# serv_open8_tsmc.net
KiCad netlist of a schematic drawn in EAGLE
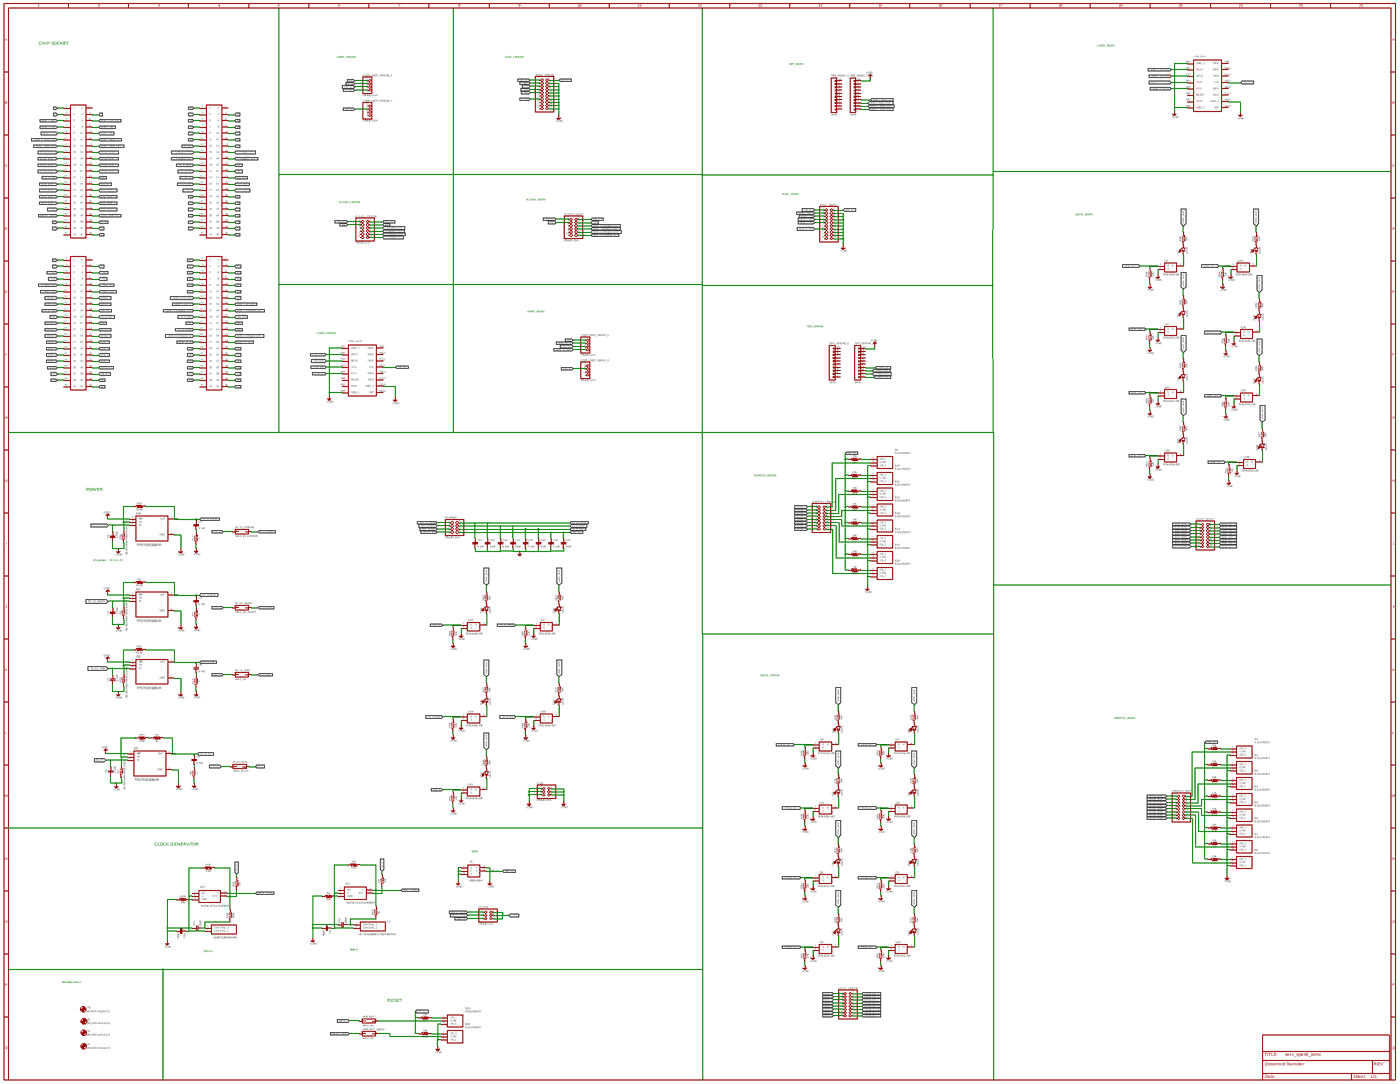
[diagram p0: schematic, sheet 1, overview]
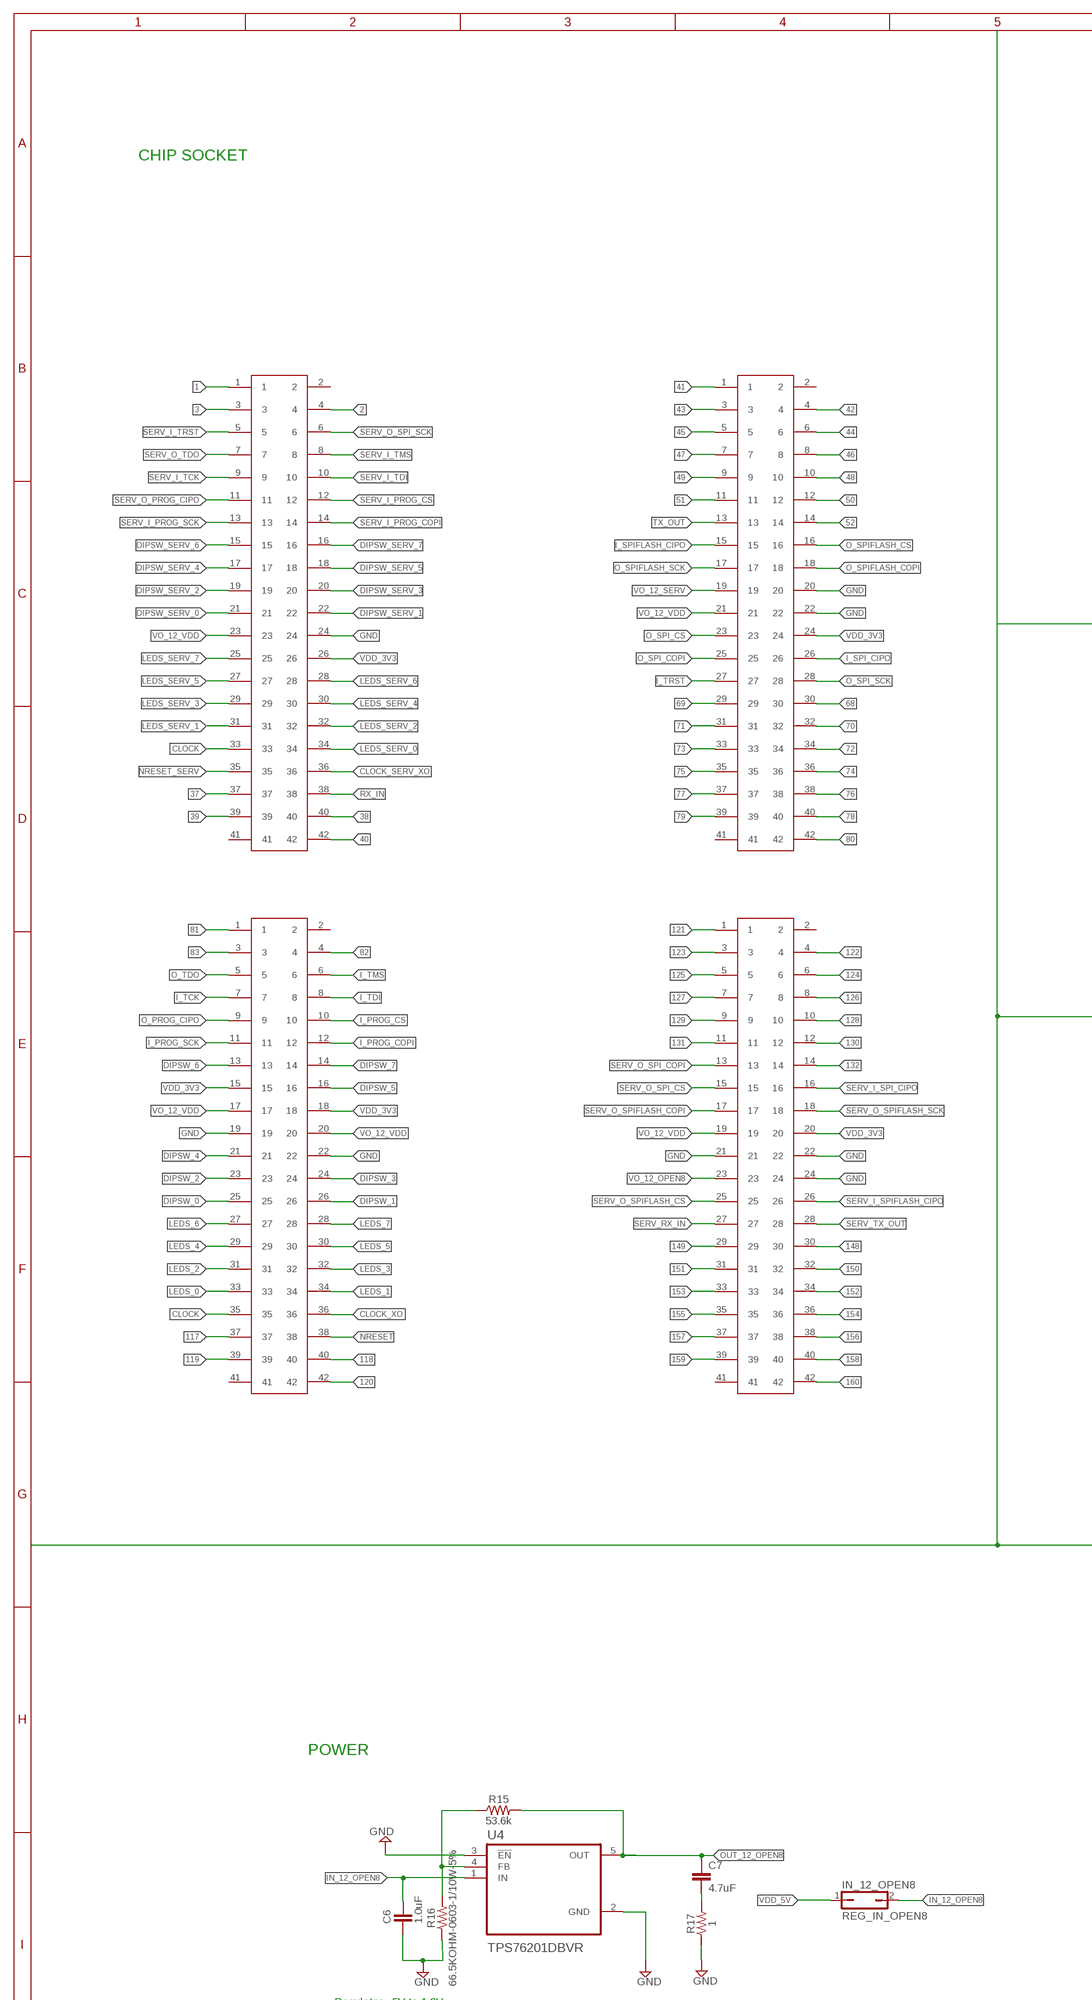
[diagram p1: schematic, sheet 1, part 1 of 8]
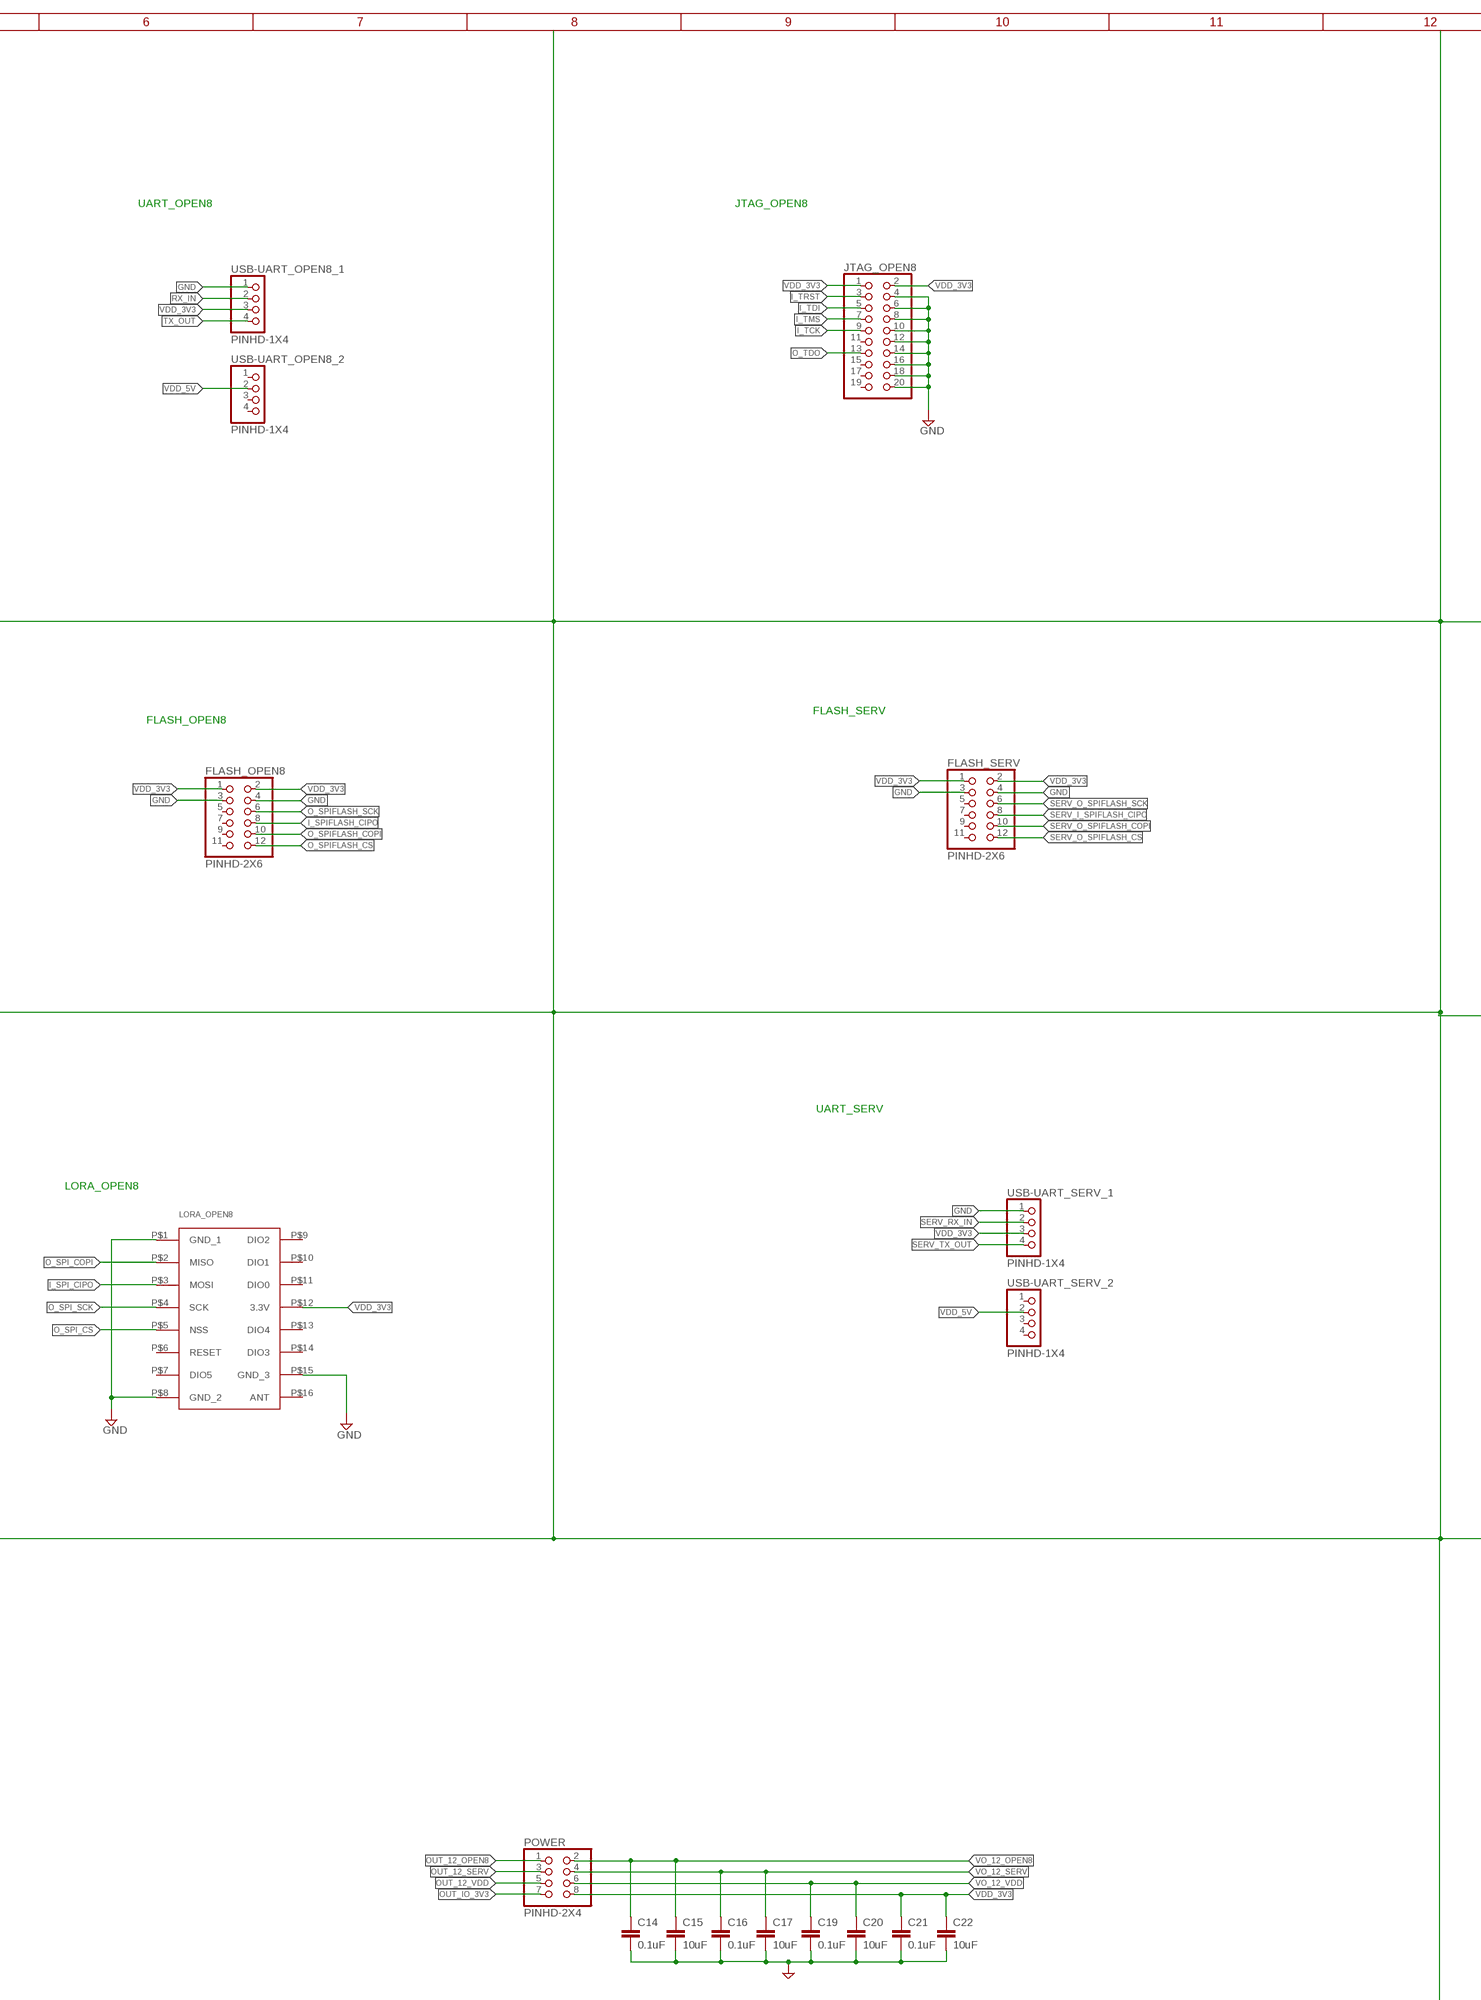
[diagram p2: schematic, sheet 1, part 2 of 8]
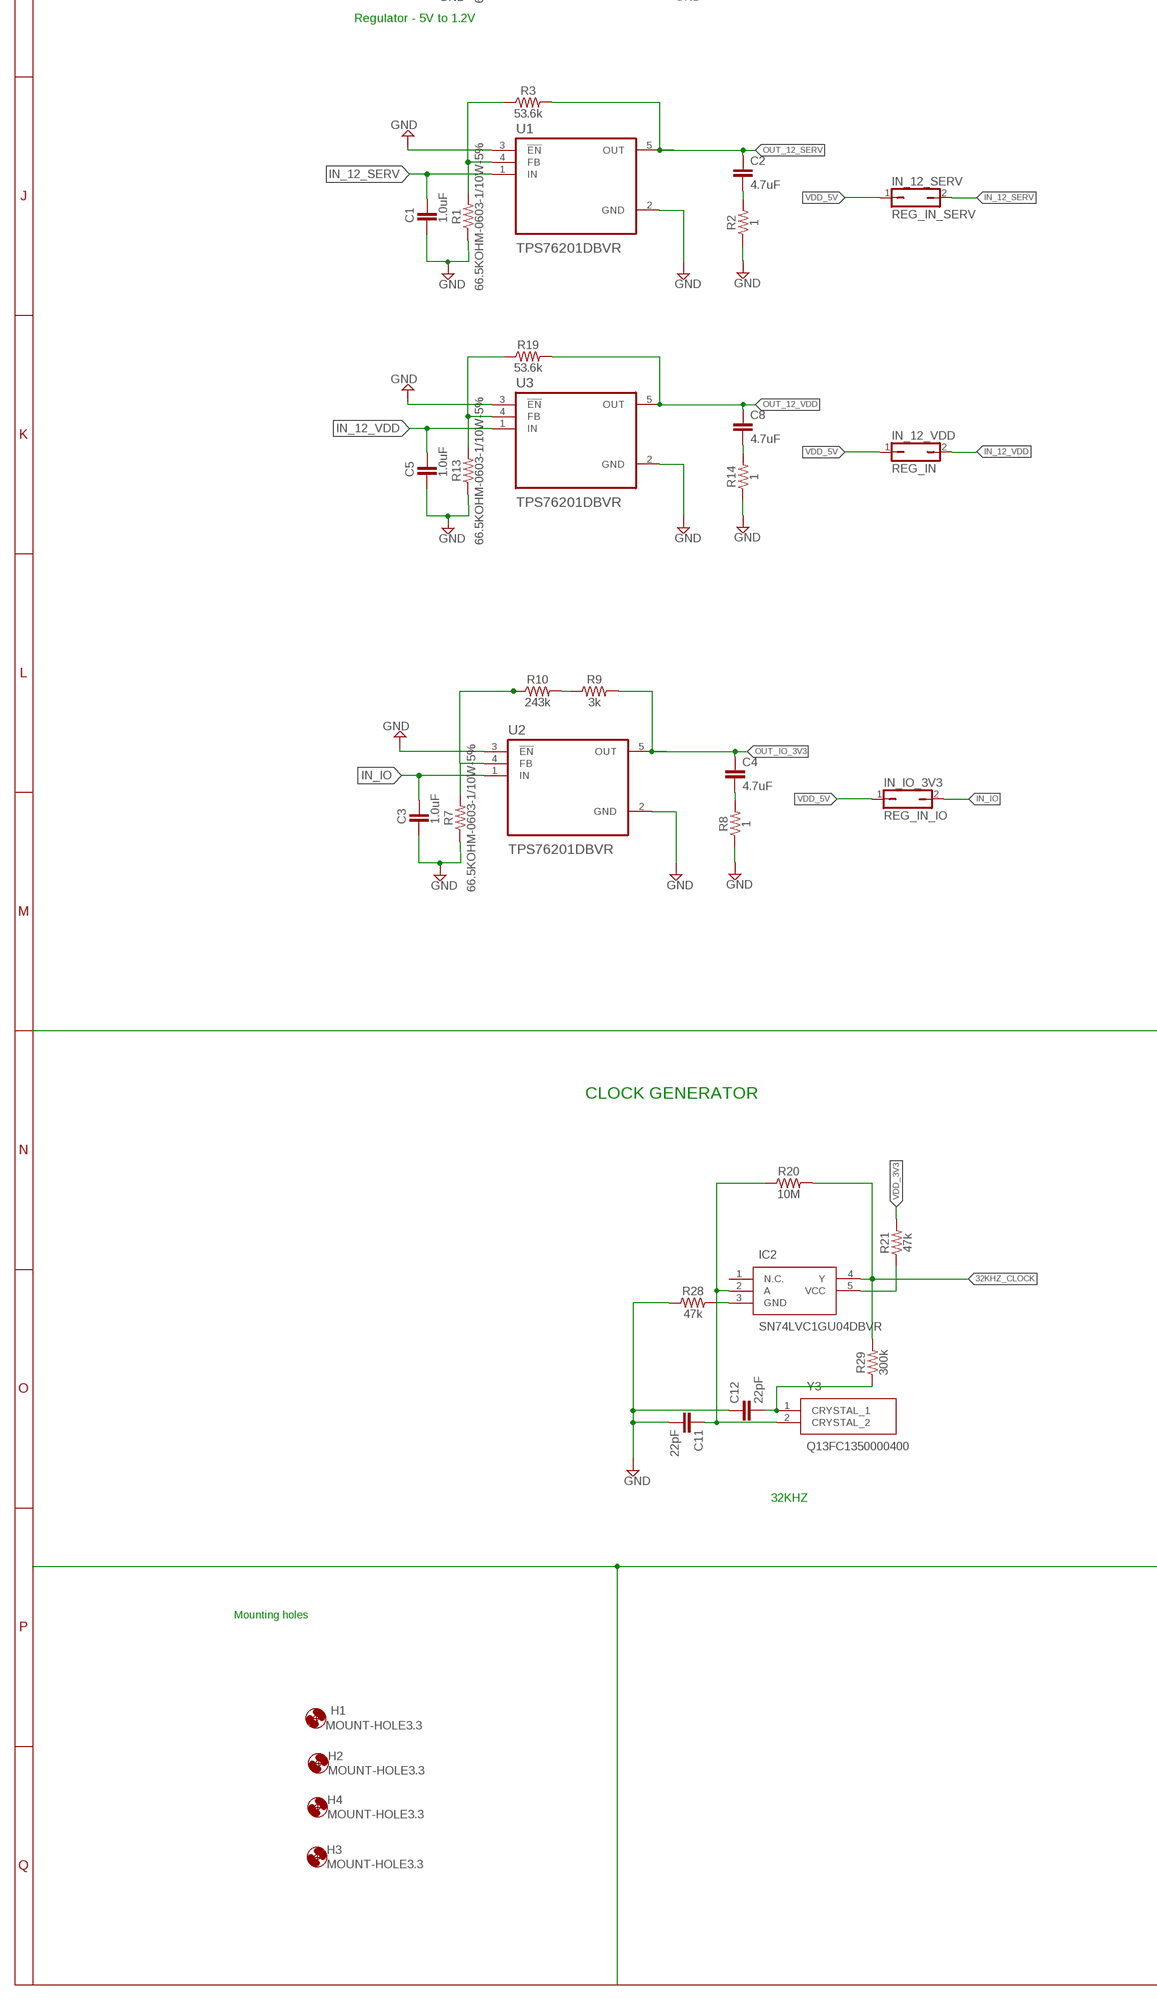
[diagram p3: schematic, sheet 1, part 3 of 8]
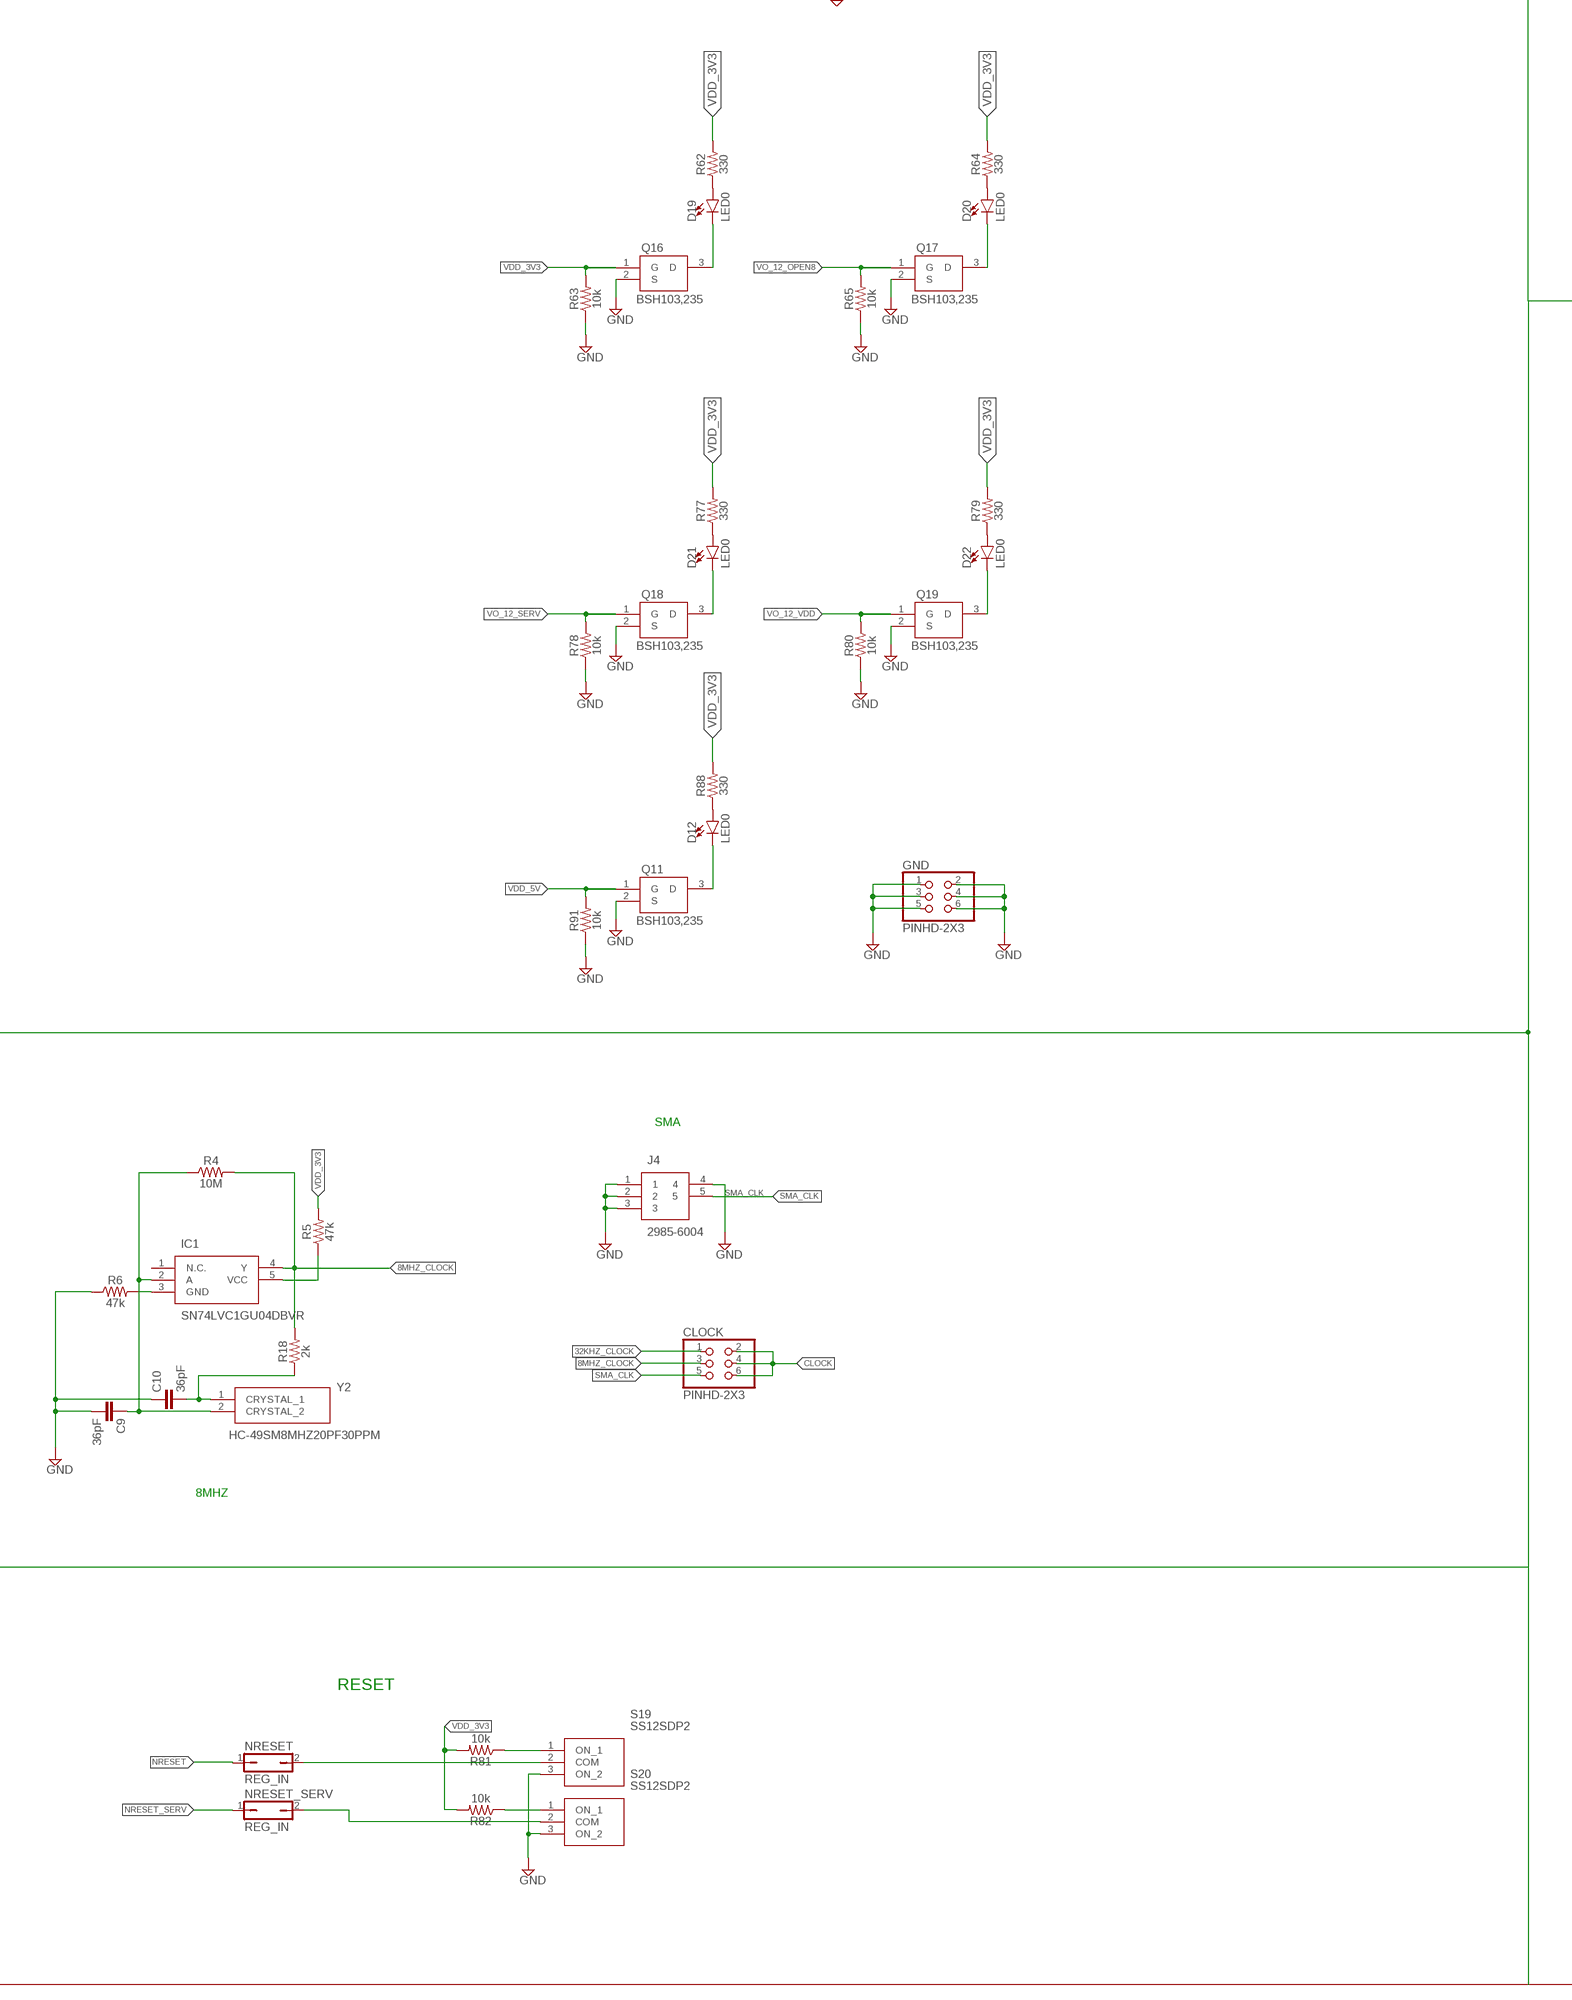
[diagram p4: schematic, sheet 1, part 4 of 8]
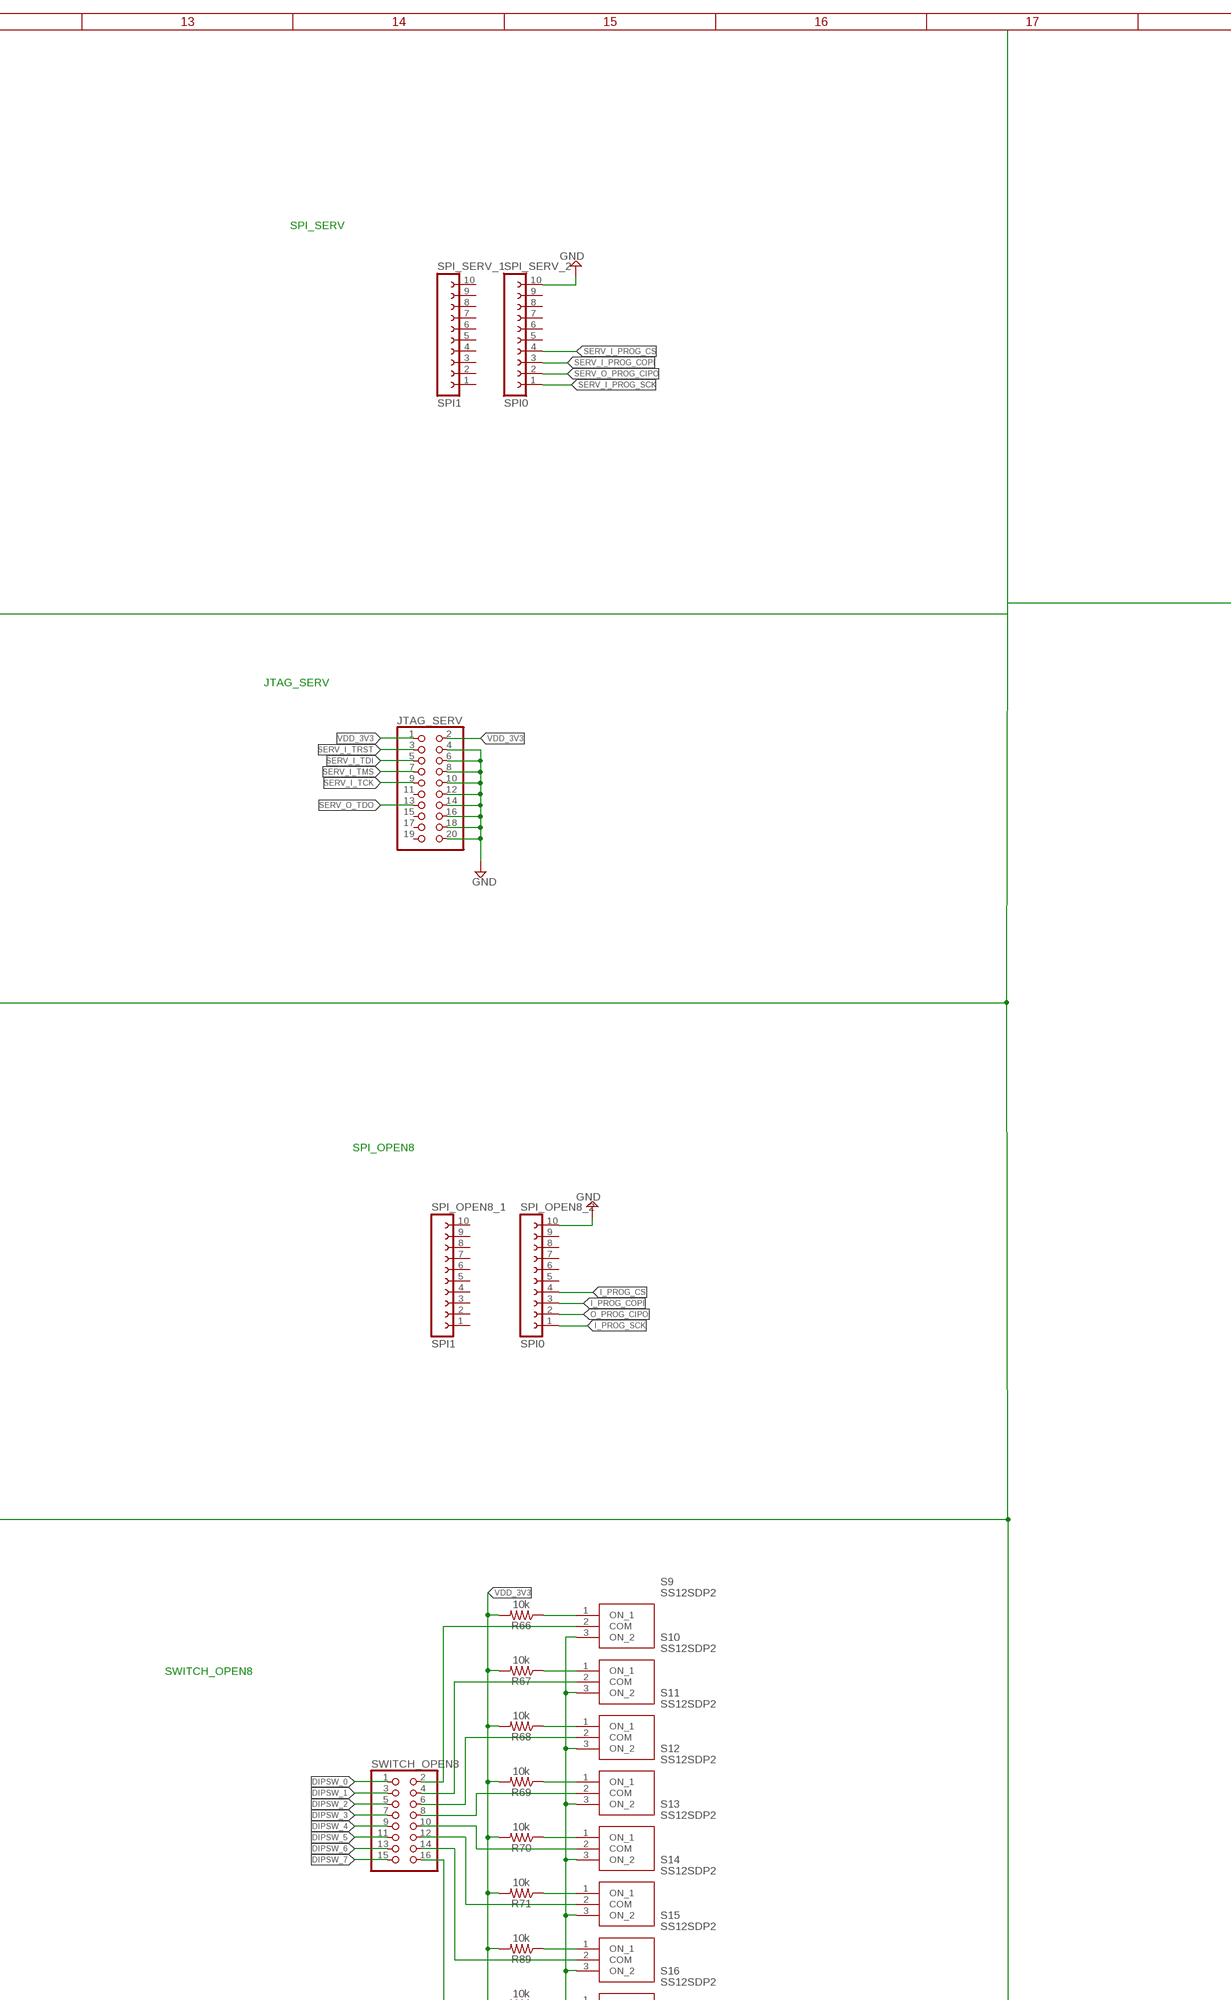
[diagram p5: schematic, sheet 1, part 5 of 8]
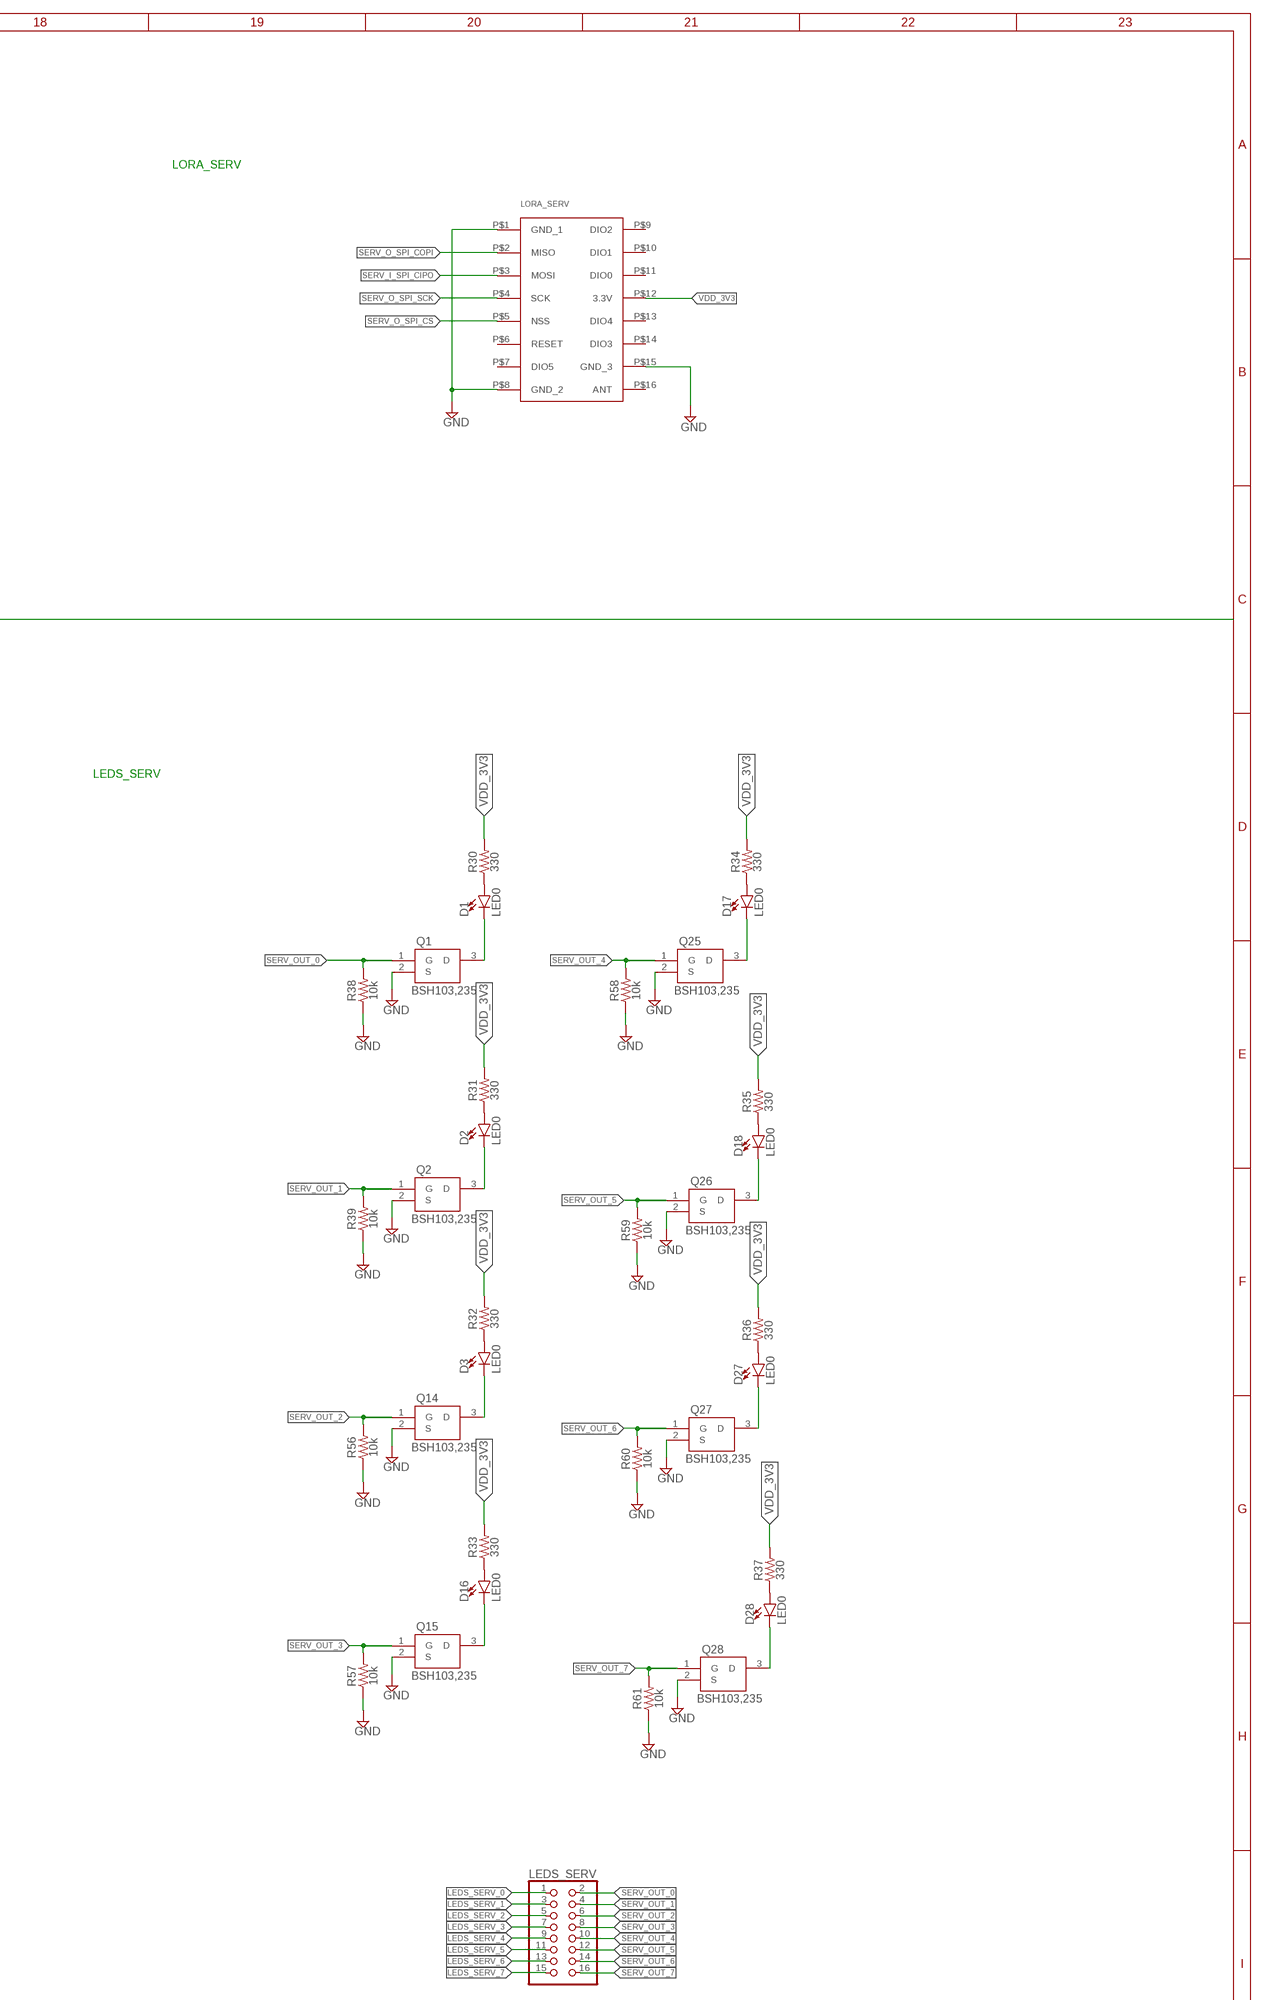
[diagram p6: schematic, sheet 1, part 6 of 8]
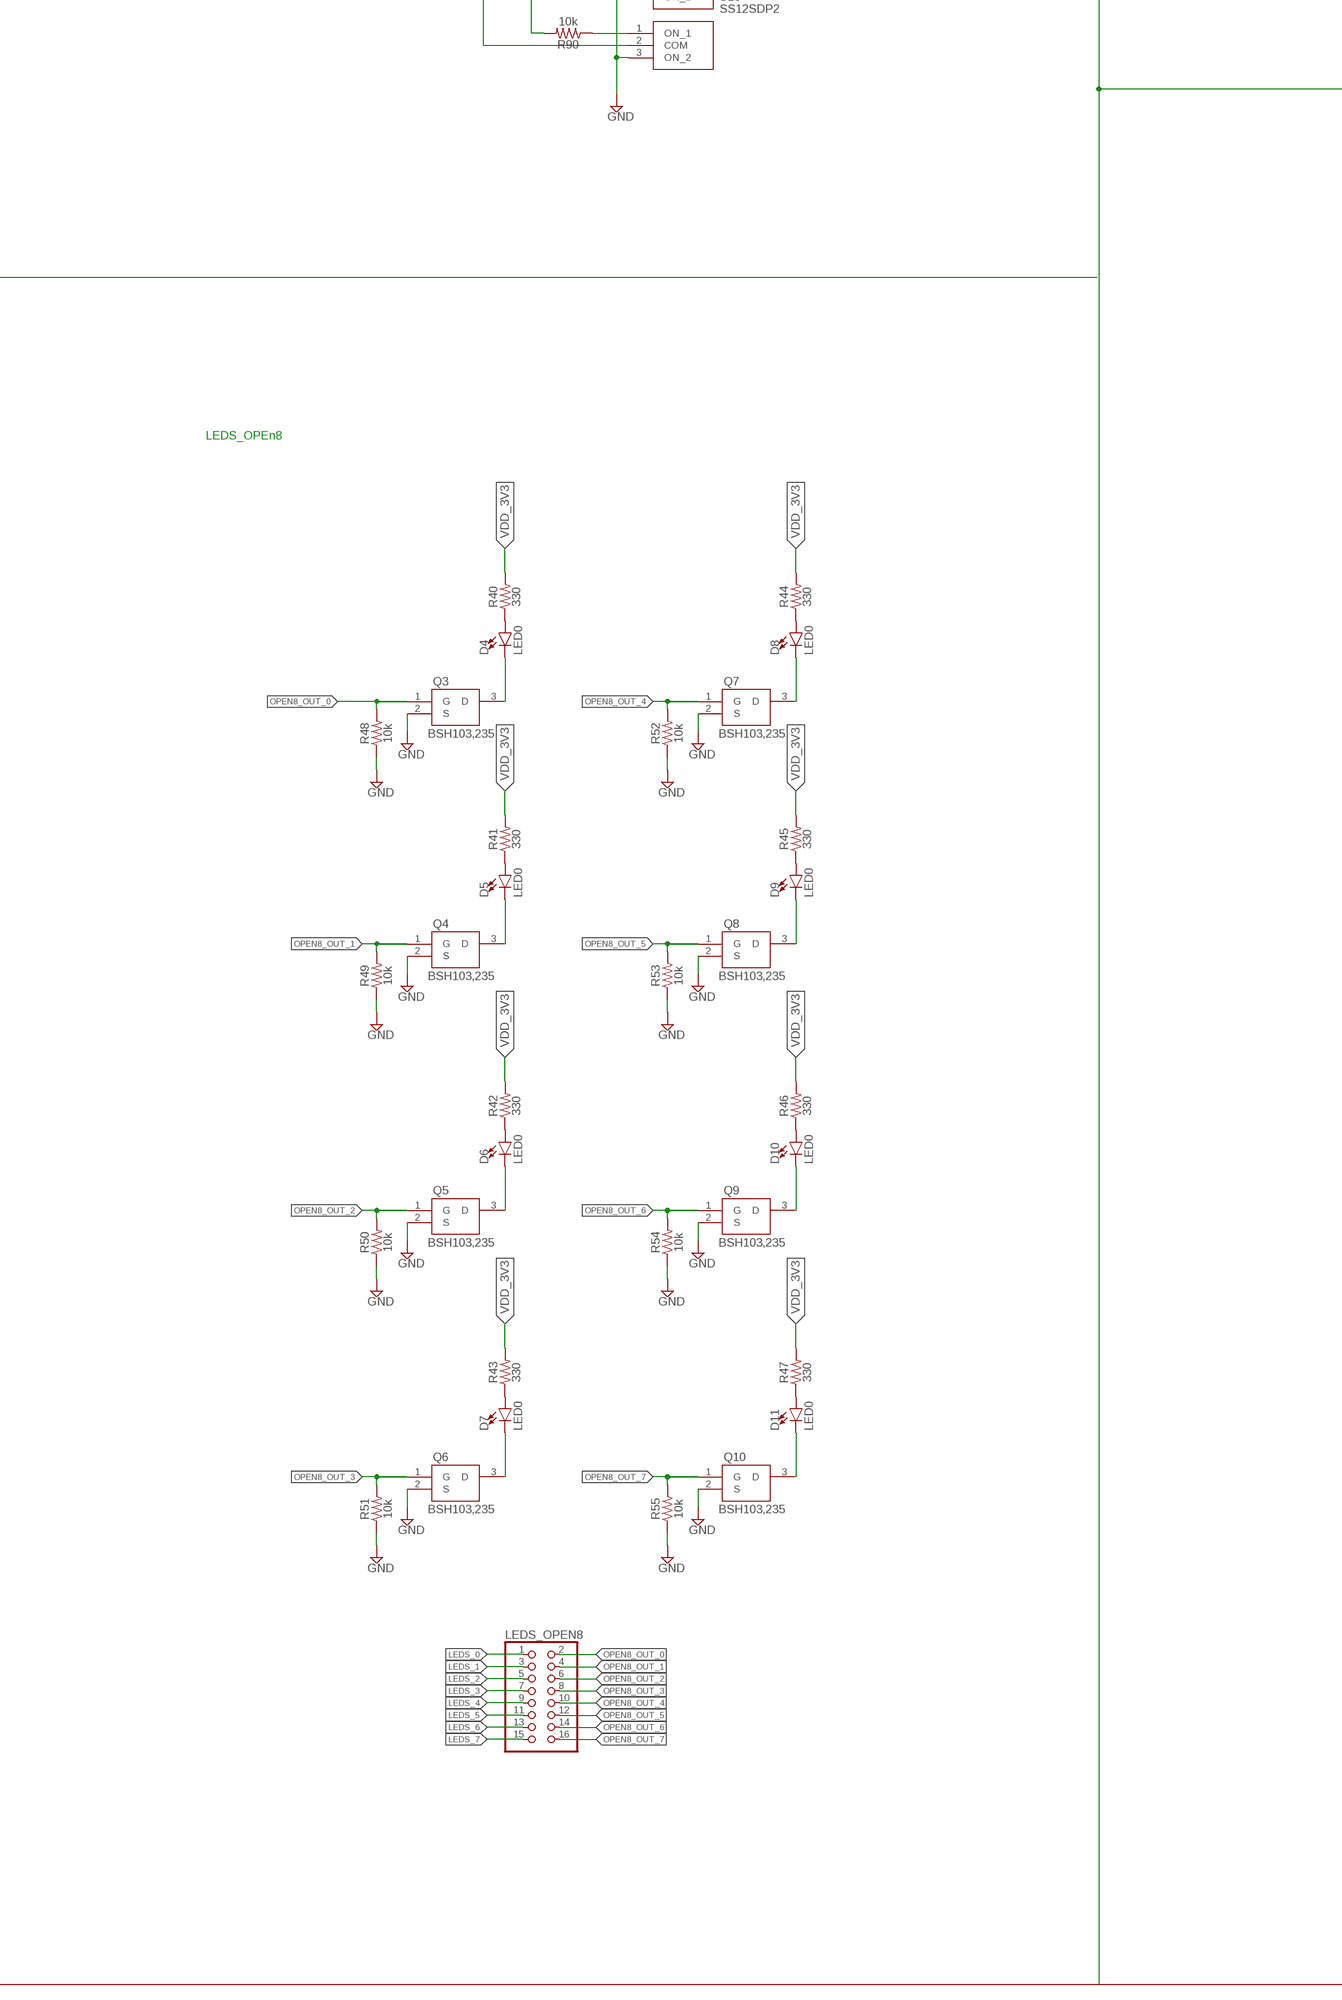
[diagram p7: schematic, sheet 1, part 7 of 8]
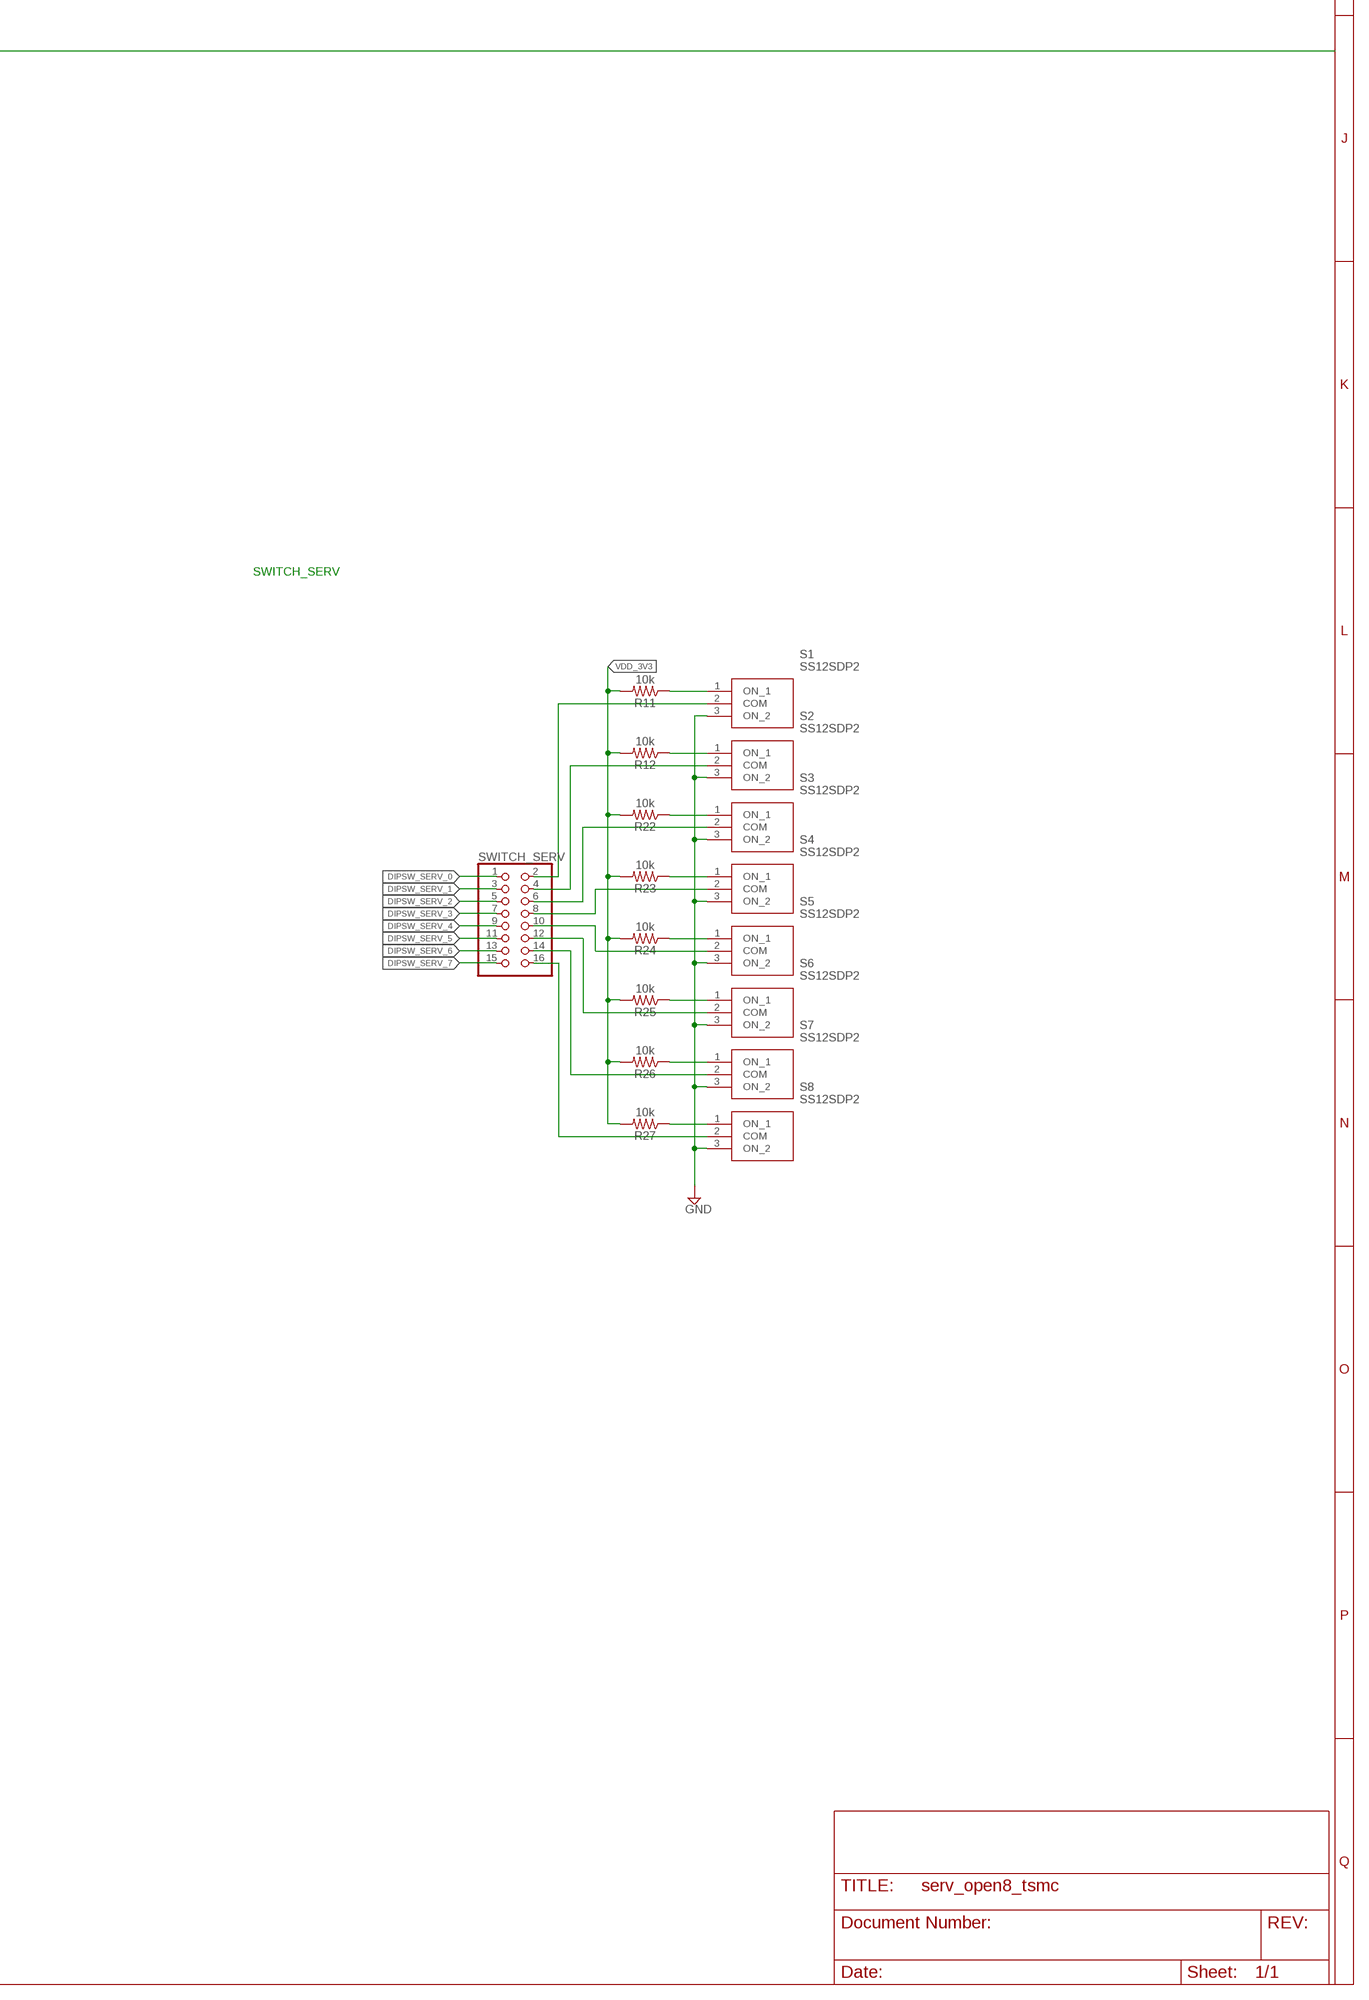
[diagram p8: schematic, sheet 1, part 8 of 8]

(export (version "E")
  (design (tool "Eeschema 10.0.6"))
  (components
    (comp (ref "C1")
      (value "1.0uF")
      (footprint "eagle-import:0603")
      (libsource (lib "eagle-import") (part "1.0UF-0603-16V-10%"))
    )
    (comp (ref "C2")
      (value "4.7uF")
      (footprint "eagle-import:0603")
      (libsource (lib "eagle-import") (part "4.7UF0603"))
    )
    (comp (ref "C3")
      (value "1.0uF")
      (footprint "eagle-import:0603")
      (libsource (lib "eagle-import") (part "1.0UF-0603-16V-10%"))
    )
    (comp (ref "C4")
      (value "4.7uF")
      (footprint "eagle-import:0603")
      (libsource (lib "eagle-import") (part "4.7UF0603"))
    )
    (comp (ref "C5")
      (value "1.0uF")
      (footprint "eagle-import:0603")
      (libsource (lib "eagle-import") (part "1.0UF-0603-16V-10%"))
    )
    (comp (ref "C6")
      (value "1.0uF")
      (footprint "eagle-import:0603")
      (libsource (lib "eagle-import") (part "1.0UF-0603-16V-10%"))
    )
    (comp (ref "C7")
      (value "4.7uF")
      (footprint "eagle-import:0603")
      (libsource (lib "eagle-import") (part "4.7UF0603"))
    )
    (comp (ref "C8")
      (value "4.7uF")
      (footprint "eagle-import:0603")
      (libsource (lib "eagle-import") (part "4.7UF0603"))
    )
    (comp (ref "C9")
      (value "36pF")
      (footprint "eagle-import:0603")
      (libsource (lib "eagle-import") (part "22PF-0603-50V-5%"))
    )
    (comp (ref "C10")
      (value "36pF")
      (footprint "eagle-import:0603")
      (libsource (lib "eagle-import") (part "22PF-0603-50V-5%"))
    )
    (comp (ref "C11")
      (value "22pF")
      (footprint "eagle-import:0603")
      (libsource (lib "eagle-import") (part "22PF-0603-50V-5%"))
    )
    (comp (ref "C12")
      (value "22pF")
      (footprint "eagle-import:0603")
      (libsource (lib "eagle-import") (part "22PF-0603-50V-5%"))
    )
    (comp (ref "C14")
      (value "0.1uF")
      (footprint "eagle-import:0603")
      (libsource (lib "eagle-import") (part "0.1UF-0603-25V-5%"))
    )
    (comp (ref "C15")
      (value "10uF")
      (footprint "eagle-import:0603")
      (libsource (lib "eagle-import") (part "10UF-0603-6.3V-20%"))
    )
    (comp (ref "C16")
      (value "0.1uF")
      (footprint "eagle-import:0603")
      (libsource (lib "eagle-import") (part "0.1UF-0603-25V-5%"))
    )
    (comp (ref "C17")
      (value "10uF")
      (footprint "eagle-import:0603")
      (libsource (lib "eagle-import") (part "10UF-0603-6.3V-20%"))
    )
    (comp (ref "C19")
      (value "0.1uF")
      (footprint "eagle-import:0603")
      (libsource (lib "eagle-import") (part "0.1UF-0603-25V-5%"))
    )
    (comp (ref "C20")
      (value "10uF")
      (footprint "eagle-import:0603")
      (libsource (lib "eagle-import") (part "10UF-0603-6.3V-20%"))
    )
    (comp (ref "C21")
      (value "0.1uF")
      (footprint "eagle-import:0603")
      (libsource (lib "eagle-import") (part "0.1UF-0603-25V-5%"))
    )
    (comp (ref "C22")
      (value "10uF")
      (footprint "eagle-import:0603")
      (libsource (lib "eagle-import") (part "10UF-0603-6.3V-20%"))
    )
    (comp (ref "CLOCK")
      (value "PINHD-2X3")
      (footprint "eagle-import:2X03")
      (libsource (lib "eagle-import") (part "PINHD-2X3"))
    )
    (comp (ref "D1")
      (value "LED0")
      (footprint "eagle-import:LED-0603")
      (libsource (lib "eagle-import") (part "LED0603"))
    )
    (comp (ref "D2")
      (value "LED0")
      (footprint "eagle-import:LED-0603")
      (libsource (lib "eagle-import") (part "LED0603"))
    )
    (comp (ref "D3")
      (value "LED0")
      (footprint "eagle-import:LED-0603")
      (libsource (lib "eagle-import") (part "LED0603"))
    )
    (comp (ref "D4")
      (value "LED0")
      (footprint "eagle-import:LED-0603")
      (libsource (lib "eagle-import") (part "LED0603"))
    )
    (comp (ref "D5")
      (value "LED0")
      (footprint "eagle-import:LED-0603")
      (libsource (lib "eagle-import") (part "LED0603"))
    )
    (comp (ref "D6")
      (value "LED0")
      (footprint "eagle-import:LED-0603")
      (libsource (lib "eagle-import") (part "LED0603"))
    )
    (comp (ref "D7")
      (value "LED0")
      (footprint "eagle-import:LED-0603")
      (libsource (lib "eagle-import") (part "LED0603"))
    )
    (comp (ref "D8")
      (value "LED0")
      (footprint "eagle-import:LED-0603")
      (libsource (lib "eagle-import") (part "LED0603"))
    )
    (comp (ref "D9")
      (value "LED0")
      (footprint "eagle-import:LED-0603")
      (libsource (lib "eagle-import") (part "LED0603"))
    )
    (comp (ref "D10")
      (value "LED0")
      (footprint "eagle-import:LED-0603")
      (libsource (lib "eagle-import") (part "LED0603"))
    )
    (comp (ref "D11")
      (value "LED0")
      (footprint "eagle-import:LED-0603")
      (libsource (lib "eagle-import") (part "LED0603"))
    )
    (comp (ref "D12")
      (value "LED0")
      (footprint "eagle-import:LED-0603")
      (libsource (lib "eagle-import") (part "LED0603"))
    )
    (comp (ref "D16")
      (value "LED0")
      (footprint "eagle-import:LED-0603")
      (libsource (lib "eagle-import") (part "LED0603"))
    )
    (comp (ref "D17")
      (value "LED0")
      (footprint "eagle-import:LED-0603")
      (libsource (lib "eagle-import") (part "LED0603"))
    )
    (comp (ref "D18")
      (value "LED0")
      (footprint "eagle-import:LED-0603")
      (libsource (lib "eagle-import") (part "LED0603"))
    )
    (comp (ref "D19")
      (value "LED0")
      (footprint "eagle-import:LED-0603")
      (libsource (lib "eagle-import") (part "LED0603"))
    )
    (comp (ref "D20")
      (value "LED0")
      (footprint "eagle-import:LED-0603")
      (libsource (lib "eagle-import") (part "LED0603"))
    )
    (comp (ref "D21")
      (value "LED0")
      (footprint "eagle-import:LED-0603")
      (libsource (lib "eagle-import") (part "LED0603"))
    )
    (comp (ref "D22")
      (value "LED0")
      (footprint "eagle-import:LED-0603")
      (libsource (lib "eagle-import") (part "LED0603"))
    )
    (comp (ref "D27")
      (value "LED0")
      (footprint "eagle-import:LED-0603")
      (libsource (lib "eagle-import") (part "LED0603"))
    )
    (comp (ref "D28")
      (value "LED0")
      (footprint "eagle-import:LED-0603")
      (libsource (lib "eagle-import") (part "LED0603"))
    )
    (comp (ref "FLASH_OPEN8")
      (value "PINHD-2X6")
      (footprint "eagle-import:2X06")
      (libsource (lib "eagle-import") (part "PINHD-2X6"))
    )
    (comp (ref "FLASH_SERV")
      (value "PINHD-2X6")
      (footprint "eagle-import:2X06")
      (libsource (lib "eagle-import") (part "PINHD-2X6"))
    )
    (comp (ref "GND")
      (value "PINHD-2X3")
      (footprint "eagle-import:2X03")
      (libsource (lib "eagle-import") (part "PINHD-2X3"))
    )
    (comp (ref "H1")
      (value "MOUNT-HOLE3.3")
      (footprint "eagle-import:3,3")
      (libsource (lib "eagle-import") (part "MOUNT-HOLE3.3"))
    )
    (comp (ref "H2")
      (value "MOUNT-HOLE3.3")
      (footprint "eagle-import:3,3")
      (libsource (lib "eagle-import") (part "MOUNT-HOLE3.3"))
    )
    (comp (ref "H3")
      (value "MOUNT-HOLE3.3")
      (footprint "eagle-import:3,3")
      (libsource (lib "eagle-import") (part "MOUNT-HOLE3.3"))
    )
    (comp (ref "H4")
      (value "MOUNT-HOLE3.3")
      (footprint "eagle-import:3,3")
      (libsource (lib "eagle-import") (part "MOUNT-HOLE3.3"))
    )
    (comp (ref "IC1")
      (value "SN74LVC1GU04DBVR")
      (footprint "eagle-import:SOT95P280X145-5N")
      (fields (field (name "MOUSER_PART_NUMBER") "595-SN74LVC1GU04DBVR"))
      (libsource (lib "eagle-import") (part "SN74LVC1GU04DBVR"))
    )
    (comp (ref "IC2")
      (value "SN74LVC1GU04DBVR")
      (footprint "eagle-import:SOT95P280X145-5N")
      (fields (field (name "MOUSER_PART_NUMBER") "595-SN74LVC1GU04DBVR"))
      (libsource (lib "eagle-import") (part "SN74LVC1GU04DBVR"))
    )
    (comp (ref "IN_12_OPEN8")
      (value "REG_IN_OPEN8")
      (footprint "eagle-import:JP1")
      (libsource (lib "eagle-import") (part "JP1Q"))
    )
    (comp (ref "IN_12_SERV")
      (value "REG_IN_SERV")
      (footprint "eagle-import:JP1")
      (libsource (lib "eagle-import") (part "JP1Q"))
    )
    (comp (ref "IN_12_VDD")
      (value "REG_IN")
      (footprint "eagle-import:JP1")
      (libsource (lib "eagle-import") (part "JP1Q"))
    )
    (comp (ref "IN_IO_3V3")
      (value "REG_IN_IO")
      (footprint "eagle-import:JP1")
      (libsource (lib "eagle-import") (part "JP1Q"))
    )
    (comp (ref "J4")
      (value "2985-6004")
      (footprint "eagle-import:29856004")
      (fields (field (name "MOUSER_PART_NUMBER") "523-2985-6004"))
      (libsource (lib "eagle-import") (part "2985-6004"))
    )
    (comp (ref "JTAG_OPEN8")
      (value "PINHD-2X10")
      (footprint "eagle-import:2X10")
      (libsource (lib "eagle-import") (part "PINHD-2X10"))
    )
    (comp (ref "JTAG_SERV")
      (value "PINHD-2X10")
      (footprint "eagle-import:2X10")
      (libsource (lib "eagle-import") (part "PINHD-2X10"))
    )
    (comp (ref "LEDS_OPEN8")
      (value "PINHD-2X8")
      (footprint "eagle-import:2X08")
      (libsource (lib "eagle-import") (part "PINHD-2X8"))
    )
    (comp (ref "LEDS_SERV")
      (value "PINHD-2X8")
      (footprint "eagle-import:2X08")
      (libsource (lib "eagle-import") (part "PINHD-2X8"))
    )
    (comp (ref "LORA_OPEN8")
      (value "RFM95W-915S2")
      (footprint "eagle-import:RFM95-915S2")
      (libsource (lib "eagle-import") (part "RFM95W-915S2"))
    )
    (comp (ref "LORA_SERV")
      (value "RFM95W-915S2")
      (footprint "eagle-import:RFM95-915S2")
      (libsource (lib "eagle-import") (part "RFM95W-915S2"))
    )
    (comp (ref "NRESET")
      (value "REG_IN")
      (footprint "eagle-import:JP1")
      (libsource (lib "eagle-import") (part "JP1Q"))
    )
    (comp (ref "NRESET_SERV")
      (value "REG_IN")
      (footprint "eagle-import:JP1")
      (libsource (lib "eagle-import") (part "JP1Q"))
    )
    (comp (ref "POWER")
      (value "PINHD-2X4")
      (footprint "eagle-import:2X04")
      (libsource (lib "eagle-import") (part "PINHD-2X4"))
    )
    (comp (ref "Q1")
      (value "BSH103,235")
      (footprint "eagle-import:SOT95P230X110-3N")
      (fields (field (name "MOUSER_PART_NUMBER") "771-BSH103235"))
      (libsource (lib "eagle-import") (part "BSH103,235"))
    )
    (comp (ref "Q2")
      (value "BSH103,235")
      (footprint "eagle-import:SOT95P230X110-3N")
      (fields (field (name "MOUSER_PART_NUMBER") "771-BSH103235"))
      (libsource (lib "eagle-import") (part "BSH103,235"))
    )
    (comp (ref "Q3")
      (value "BSH103,235")
      (footprint "eagle-import:SOT95P230X110-3N")
      (fields (field (name "MOUSER_PART_NUMBER") "771-BSH103235"))
      (libsource (lib "eagle-import") (part "BSH103,235"))
    )
    (comp (ref "Q4")
      (value "BSH103,235")
      (footprint "eagle-import:SOT95P230X110-3N")
      (fields (field (name "MOUSER_PART_NUMBER") "771-BSH103235"))
      (libsource (lib "eagle-import") (part "BSH103,235"))
    )
    (comp (ref "Q5")
      (value "BSH103,235")
      (footprint "eagle-import:SOT95P230X110-3N")
      (fields (field (name "MOUSER_PART_NUMBER") "771-BSH103235"))
      (libsource (lib "eagle-import") (part "BSH103,235"))
    )
    (comp (ref "Q6")
      (value "BSH103,235")
      (footprint "eagle-import:SOT95P230X110-3N")
      (fields (field (name "MOUSER_PART_NUMBER") "771-BSH103235"))
      (libsource (lib "eagle-import") (part "BSH103,235"))
    )
    (comp (ref "Q7")
      (value "BSH103,235")
      (footprint "eagle-import:SOT95P230X110-3N")
      (fields (field (name "MOUSER_PART_NUMBER") "771-BSH103235"))
      (libsource (lib "eagle-import") (part "BSH103,235"))
    )
    (comp (ref "Q8")
      (value "BSH103,235")
      (footprint "eagle-import:SOT95P230X110-3N")
      (fields (field (name "MOUSER_PART_NUMBER") "771-BSH103235"))
      (libsource (lib "eagle-import") (part "BSH103,235"))
    )
    (comp (ref "Q9")
      (value "BSH103,235")
      (footprint "eagle-import:SOT95P230X110-3N")
      (fields (field (name "MOUSER_PART_NUMBER") "771-BSH103235"))
      (libsource (lib "eagle-import") (part "BSH103,235"))
    )
    (comp (ref "Q10")
      (value "BSH103,235")
      (footprint "eagle-import:SOT95P230X110-3N")
      (fields (field (name "MOUSER_PART_NUMBER") "771-BSH103235"))
      (libsource (lib "eagle-import") (part "BSH103,235"))
    )
    (comp (ref "Q11")
      (value "BSH103,235")
      (footprint "eagle-import:SOT95P230X110-3N")
      (fields (field (name "MOUSER_PART_NUMBER") "771-BSH103235"))
      (libsource (lib "eagle-import") (part "BSH103,235"))
    )
    (comp (ref "Q14")
      (value "BSH103,235")
      (footprint "eagle-import:SOT95P230X110-3N")
      (fields (field (name "MOUSER_PART_NUMBER") "771-BSH103235"))
      (libsource (lib "eagle-import") (part "BSH103,235"))
    )
    (comp (ref "Q15")
      (value "BSH103,235")
      (footprint "eagle-import:SOT95P230X110-3N")
      (fields (field (name "MOUSER_PART_NUMBER") "771-BSH103235"))
      (libsource (lib "eagle-import") (part "BSH103,235"))
    )
    (comp (ref "Q16")
      (value "BSH103,235")
      (footprint "eagle-import:SOT95P230X110-3N")
      (fields (field (name "MOUSER_PART_NUMBER") "771-BSH103235"))
      (libsource (lib "eagle-import") (part "BSH103,235"))
    )
    (comp (ref "Q17")
      (value "BSH103,235")
      (footprint "eagle-import:SOT95P230X110-3N")
      (fields (field (name "MOUSER_PART_NUMBER") "771-BSH103235"))
      (libsource (lib "eagle-import") (part "BSH103,235"))
    )
    (comp (ref "Q18")
      (value "BSH103,235")
      (footprint "eagle-import:SOT95P230X110-3N")
      (fields (field (name "MOUSER_PART_NUMBER") "771-BSH103235"))
      (libsource (lib "eagle-import") (part "BSH103,235"))
    )
    (comp (ref "Q19")
      (value "BSH103,235")
      (footprint "eagle-import:SOT95P230X110-3N")
      (fields (field (name "MOUSER_PART_NUMBER") "771-BSH103235"))
      (libsource (lib "eagle-import") (part "BSH103,235"))
    )
    (comp (ref "Q25")
      (value "BSH103,235")
      (footprint "eagle-import:SOT95P230X110-3N")
      (fields (field (name "MOUSER_PART_NUMBER") "771-BSH103235"))
      (libsource (lib "eagle-import") (part "BSH103,235"))
    )
    (comp (ref "Q26")
      (value "BSH103,235")
      (footprint "eagle-import:SOT95P230X110-3N")
      (fields (field (name "MOUSER_PART_NUMBER") "771-BSH103235"))
      (libsource (lib "eagle-import") (part "BSH103,235"))
    )
    (comp (ref "Q27")
      (value "BSH103,235")
      (footprint "eagle-import:SOT95P230X110-3N")
      (fields (field (name "MOUSER_PART_NUMBER") "771-BSH103235"))
      (libsource (lib "eagle-import") (part "BSH103,235"))
    )
    (comp (ref "Q28")
      (value "BSH103,235")
      (footprint "eagle-import:SOT95P230X110-3N")
      (fields (field (name "MOUSER_PART_NUMBER") "771-BSH103235"))
      (libsource (lib "eagle-import") (part "BSH103,235"))
    )
    (comp (ref "R1")
      (value "66.5KOHM-0603-1/10W-5%")
      (footprint "eagle-import:0603")
      (libsource (lib "eagle-import") (part "62KOHM-0603-1/10W-5%"))
    )
    (comp (ref "R2")
      (value "1")
      (footprint "eagle-import:0603")
      (libsource (lib "eagle-import") (part "1OHM-0603-1/10W-1%"))
    )
    (comp (ref "R3")
      (value "53.6k")
      (footprint "eagle-import:0603")
      (libsource (lib "eagle-import") (part "43KOHM-0603-1/10W-1%"))
    )
    (comp (ref "R4")
      (value "10M")
      (footprint "eagle-import:0603")
      (libsource (lib "eagle-import") (part "22MOHM-0603-1/10W-10%"))
    )
    (comp (ref "R5")
      (value "47k")
      (footprint "eagle-import:0603")
      (libsource (lib "eagle-import") (part "22MOHM-0603-1/10W-10%"))
    )
    (comp (ref "R6")
      (value "47k")
      (footprint "eagle-import:0603")
      (libsource (lib "eagle-import") (part "22MOHM-0603-1/10W-10%"))
    )
    (comp (ref "R7")
      (value "66.5KOHM-0603-1/10W-5%")
      (footprint "eagle-import:0603")
      (libsource (lib "eagle-import") (part "62KOHM-0603-1/10W-5%"))
    )
    (comp (ref "R8")
      (value "1")
      (footprint "eagle-import:0603")
      (libsource (lib "eagle-import") (part "1OHM-0603-1/10W-1%"))
    )
    (comp (ref "R9")
      (value "3k")
      (footprint "eagle-import:0603")
      (libsource (lib "eagle-import") (part "26.7KOHM0603-1/10W-1%"))
    )
    (comp (ref "R10")
      (value "243k")
      (footprint "eagle-import:0603")
      (libsource (lib "eagle-import") (part "220KOHM-0603-1/10W-1%"))
    )
    (comp (ref "R11")
      (value "10k")
      (footprint "eagle-import:0603")
      (libsource (lib "eagle-import") (part "10KOHM-0603-1/10W-1%"))
    )
    (comp (ref "R12")
      (value "10k")
      (footprint "eagle-import:0603")
      (libsource (lib "eagle-import") (part "10KOHM-0603-1/10W-1%"))
    )
    (comp (ref "R13")
      (value "66.5KOHM-0603-1/10W-5%")
      (footprint "eagle-import:0603")
      (libsource (lib "eagle-import") (part "62KOHM-0603-1/10W-5%"))
    )
    (comp (ref "R14")
      (value "1")
      (footprint "eagle-import:0603")
      (libsource (lib "eagle-import") (part "1OHM-0603-1/10W-1%"))
    )
    (comp (ref "R15")
      (value "53.6k")
      (footprint "eagle-import:0603")
      (libsource (lib "eagle-import") (part "43KOHM-0603-1/10W-1%"))
    )
    (comp (ref "R16")
      (value "66.5KOHM-0603-1/10W-5%")
      (footprint "eagle-import:0603")
      (libsource (lib "eagle-import") (part "62KOHM-0603-1/10W-5%"))
    )
    (comp (ref "R17")
      (value "1")
      (footprint "eagle-import:0603")
      (libsource (lib "eagle-import") (part "1OHM-0603-1/10W-1%"))
    )
    (comp (ref "R18")
      (value "2k")
      (footprint "eagle-import:0603")
      (libsource (lib "eagle-import") (part "22MOHM-0603-1/10W-10%"))
    )
    (comp (ref "R19")
      (value "53.6k")
      (footprint "eagle-import:0603")
      (libsource (lib "eagle-import") (part "43KOHM-0603-1/10W-1%"))
    )
    (comp (ref "R20")
      (value "10M")
      (footprint "eagle-import:0603")
      (libsource (lib "eagle-import") (part "22MOHM-0603-1/10W-10%"))
    )
    (comp (ref "R21")
      (value "47k")
      (footprint "eagle-import:0603")
      (libsource (lib "eagle-import") (part "22MOHM-0603-1/10W-10%"))
    )
    (comp (ref "R22")
      (value "10k")
      (footprint "eagle-import:0603")
      (libsource (lib "eagle-import") (part "10KOHM-0603-1/10W-1%"))
    )
    (comp (ref "R23")
      (value "10k")
      (footprint "eagle-import:0603")
      (libsource (lib "eagle-import") (part "10KOHM-0603-1/10W-1%"))
    )
    (comp (ref "R24")
      (value "10k")
      (footprint "eagle-import:0603")
      (libsource (lib "eagle-import") (part "10KOHM-0603-1/10W-1%"))
    )
    (comp (ref "R25")
      (value "10k")
      (footprint "eagle-import:0603")
      (libsource (lib "eagle-import") (part "10KOHM-0603-1/10W-1%"))
    )
    (comp (ref "R26")
      (value "10k")
      (footprint "eagle-import:0603")
      (libsource (lib "eagle-import") (part "10KOHM-0603-1/10W-1%"))
    )
    (comp (ref "R27")
      (value "10k")
      (footprint "eagle-import:0603")
      (libsource (lib "eagle-import") (part "10KOHM-0603-1/10W-1%"))
    )
    (comp (ref "R28")
      (value "47k")
      (footprint "eagle-import:0603")
      (libsource (lib "eagle-import") (part "22MOHM-0603-1/10W-10%"))
    )
    (comp (ref "R29")
      (value "300k")
      (footprint "eagle-import:0603")
      (libsource (lib "eagle-import") (part "22MOHM-0603-1/10W-10%"))
    )
    (comp (ref "R30")
      (value "330")
      (footprint "eagle-import:0603")
      (libsource (lib "eagle-import") (part "330OHM-0603-1/10W-1%"))
    )
    (comp (ref "R31")
      (value "330")
      (footprint "eagle-import:0603")
      (libsource (lib "eagle-import") (part "330OHM-0603-1/10W-1%"))
    )
    (comp (ref "R32")
      (value "330")
      (footprint "eagle-import:0603")
      (libsource (lib "eagle-import") (part "330OHM-0603-1/10W-1%"))
    )
    (comp (ref "R33")
      (value "330")
      (footprint "eagle-import:0603")
      (libsource (lib "eagle-import") (part "330OHM-0603-1/10W-1%"))
    )
    (comp (ref "R34")
      (value "330")
      (footprint "eagle-import:0603")
      (libsource (lib "eagle-import") (part "330OHM-0603-1/10W-1%"))
    )
    (comp (ref "R35")
      (value "330")
      (footprint "eagle-import:0603")
      (libsource (lib "eagle-import") (part "330OHM-0603-1/10W-1%"))
    )
    (comp (ref "R36")
      (value "330")
      (footprint "eagle-import:0603")
      (libsource (lib "eagle-import") (part "330OHM-0603-1/10W-1%"))
    )
    (comp (ref "R37")
      (value "330")
      (footprint "eagle-import:0603")
      (libsource (lib "eagle-import") (part "330OHM-0603-1/10W-1%"))
    )
    (comp (ref "R38")
      (value "10k")
      (footprint "eagle-import:0603")
      (libsource (lib "eagle-import") (part "10KOHM-0603-1/10W-1%"))
    )
    (comp (ref "R39")
      (value "10k")
      (footprint "eagle-import:0603")
      (libsource (lib "eagle-import") (part "10KOHM-0603-1/10W-1%"))
    )
    (comp (ref "R40")
      (value "330")
      (footprint "eagle-import:0603")
      (libsource (lib "eagle-import") (part "330OHM-0603-1/10W-1%"))
    )
    (comp (ref "R41")
      (value "330")
      (footprint "eagle-import:0603")
      (libsource (lib "eagle-import") (part "330OHM-0603-1/10W-1%"))
    )
    (comp (ref "R42")
      (value "330")
      (footprint "eagle-import:0603")
      (libsource (lib "eagle-import") (part "330OHM-0603-1/10W-1%"))
    )
    (comp (ref "R43")
      (value "330")
      (footprint "eagle-import:0603")
      (libsource (lib "eagle-import") (part "330OHM-0603-1/10W-1%"))
    )
    (comp (ref "R44")
      (value "330")
      (footprint "eagle-import:0603")
      (libsource (lib "eagle-import") (part "330OHM-0603-1/10W-1%"))
    )
    (comp (ref "R45")
      (value "330")
      (footprint "eagle-import:0603")
      (libsource (lib "eagle-import") (part "330OHM-0603-1/10W-1%"))
    )
    (comp (ref "R46")
      (value "330")
      (footprint "eagle-import:0603")
      (libsource (lib "eagle-import") (part "330OHM-0603-1/10W-1%"))
    )
    (comp (ref "R47")
      (value "330")
      (footprint "eagle-import:0603")
      (libsource (lib "eagle-import") (part "330OHM-0603-1/10W-1%"))
    )
    (comp (ref "R48")
      (value "10k")
      (footprint "eagle-import:0603")
      (libsource (lib "eagle-import") (part "10KOHM-0603-1/10W-1%"))
    )
    (comp (ref "R49")
      (value "10k")
      (footprint "eagle-import:0603")
      (libsource (lib "eagle-import") (part "10KOHM-0603-1/10W-1%"))
    )
    (comp (ref "R50")
      (value "10k")
      (footprint "eagle-import:0603")
      (libsource (lib "eagle-import") (part "10KOHM-0603-1/10W-1%"))
    )
    (comp (ref "R51")
      (value "10k")
      (footprint "eagle-import:0603")
      (libsource (lib "eagle-import") (part "10KOHM-0603-1/10W-1%"))
    )
    (comp (ref "R52")
      (value "10k")
      (footprint "eagle-import:0603")
      (libsource (lib "eagle-import") (part "10KOHM-0603-1/10W-1%"))
    )
    (comp (ref "R53")
      (value "10k")
      (footprint "eagle-import:0603")
      (libsource (lib "eagle-import") (part "10KOHM-0603-1/10W-1%"))
    )
    (comp (ref "R54")
      (value "10k")
      (footprint "eagle-import:0603")
      (libsource (lib "eagle-import") (part "10KOHM-0603-1/10W-1%"))
    )
    (comp (ref "R55")
      (value "10k")
      (footprint "eagle-import:0603")
      (libsource (lib "eagle-import") (part "10KOHM-0603-1/10W-1%"))
    )
    (comp (ref "R56")
      (value "10k")
      (footprint "eagle-import:0603")
      (libsource (lib "eagle-import") (part "10KOHM-0603-1/10W-1%"))
    )
    (comp (ref "R57")
      (value "10k")
      (footprint "eagle-import:0603")
      (libsource (lib "eagle-import") (part "10KOHM-0603-1/10W-1%"))
    )
    (comp (ref "R58")
      (value "10k")
      (footprint "eagle-import:0603")
      (libsource (lib "eagle-import") (part "10KOHM-0603-1/10W-1%"))
    )
    (comp (ref "R59")
      (value "10k")
      (footprint "eagle-import:0603")
      (libsource (lib "eagle-import") (part "10KOHM-0603-1/10W-1%"))
    )
    (comp (ref "R60")
      (value "10k")
      (footprint "eagle-import:0603")
      (libsource (lib "eagle-import") (part "10KOHM-0603-1/10W-1%"))
    )
    (comp (ref "R61")
      (value "10k")
      (footprint "eagle-import:0603")
      (libsource (lib "eagle-import") (part "10KOHM-0603-1/10W-1%"))
    )
    (comp (ref "R62")
      (value "330")
      (footprint "eagle-import:0603")
      (libsource (lib "eagle-import") (part "330OHM-0603-1/10W-1%"))
    )
    (comp (ref "R63")
      (value "10k")
      (footprint "eagle-import:0603")
      (libsource (lib "eagle-import") (part "10KOHM-0603-1/10W-1%"))
    )
    (comp (ref "R64")
      (value "330")
      (footprint "eagle-import:0603")
      (libsource (lib "eagle-import") (part "330OHM-0603-1/10W-1%"))
    )
    (comp (ref "R65")
      (value "10k")
      (footprint "eagle-import:0603")
      (libsource (lib "eagle-import") (part "10KOHM-0603-1/10W-1%"))
    )
    (comp (ref "R66")
      (value "10k")
      (footprint "eagle-import:0603")
      (libsource (lib "eagle-import") (part "10KOHM-0603-1/10W-1%"))
    )
    (comp (ref "R67")
      (value "10k")
      (footprint "eagle-import:0603")
      (libsource (lib "eagle-import") (part "10KOHM-0603-1/10W-1%"))
    )
    (comp (ref "R68")
      (value "10k")
      (footprint "eagle-import:0603")
      (libsource (lib "eagle-import") (part "10KOHM-0603-1/10W-1%"))
    )
    (comp (ref "R69")
      (value "10k")
      (footprint "eagle-import:0603")
      (libsource (lib "eagle-import") (part "10KOHM-0603-1/10W-1%"))
    )
    (comp (ref "R70")
      (value "10k")
      (footprint "eagle-import:0603")
      (libsource (lib "eagle-import") (part "10KOHM-0603-1/10W-1%"))
    )
    (comp (ref "R71")
      (value "10k")
      (footprint "eagle-import:0603")
      (libsource (lib "eagle-import") (part "10KOHM-0603-1/10W-1%"))
    )
    (comp (ref "R77")
      (value "330")
      (footprint "eagle-import:0603")
      (libsource (lib "eagle-import") (part "330OHM-0603-1/10W-1%"))
    )
    (comp (ref "R78")
      (value "10k")
      (footprint "eagle-import:0603")
      (libsource (lib "eagle-import") (part "10KOHM-0603-1/10W-1%"))
    )
    (comp (ref "R79")
      (value "330")
      (footprint "eagle-import:0603")
      (libsource (lib "eagle-import") (part "330OHM-0603-1/10W-1%"))
    )
    (comp (ref "R80")
      (value "10k")
      (footprint "eagle-import:0603")
      (libsource (lib "eagle-import") (part "10KOHM-0603-1/10W-1%"))
    )
    (comp (ref "R81")
      (value "10k")
      (footprint "eagle-import:0603")
      (libsource (lib "eagle-import") (part "10KOHM-0603-1/10W-1%"))
    )
    (comp (ref "R82")
      (value "10k")
      (footprint "eagle-import:0603")
      (libsource (lib "eagle-import") (part "10KOHM-0603-1/10W-1%"))
    )
    (comp (ref "R88")
      (value "330")
      (footprint "eagle-import:0603")
      (libsource (lib "eagle-import") (part "330OHM-0603-1/10W-1%"))
    )
    (comp (ref "R89")
      (value "10k")
      (footprint "eagle-import:0603")
      (libsource (lib "eagle-import") (part "10KOHM-0603-1/10W-1%"))
    )
    (comp (ref "R90")
      (value "10k")
      (footprint "eagle-import:0603")
      (libsource (lib "eagle-import") (part "10KOHM-0603-1/10W-1%"))
    )
    (comp (ref "R91")
      (value "10k")
      (footprint "eagle-import:0603")
      (libsource (lib "eagle-import") (part "10KOHM-0603-1/10W-1%"))
    )
    (comp (ref "S1")
      (value "SS12SDP2")
      (footprint "eagle-import:SS12SDP2")
      (fields (field (name "MOUSER_PART_NUMBER") "633-SS12SDP2"))
      (libsource (lib "eagle-import") (part "SS12SDP2"))
    )
    (comp (ref "S2")
      (value "SS12SDP2")
      (footprint "eagle-import:SS12SDP2")
      (fields (field (name "MOUSER_PART_NUMBER") "633-SS12SDP2"))
      (libsource (lib "eagle-import") (part "SS12SDP2"))
    )
    (comp (ref "S3")
      (value "SS12SDP2")
      (footprint "eagle-import:SS12SDP2")
      (fields (field (name "MOUSER_PART_NUMBER") "633-SS12SDP2"))
      (libsource (lib "eagle-import") (part "SS12SDP2"))
    )
    (comp (ref "S4")
      (value "SS12SDP2")
      (footprint "eagle-import:SS12SDP2")
      (fields (field (name "MOUSER_PART_NUMBER") "633-SS12SDP2"))
      (libsource (lib "eagle-import") (part "SS12SDP2"))
    )
    (comp (ref "S5")
      (value "SS12SDP2")
      (footprint "eagle-import:SS12SDP2")
      (fields (field (name "MOUSER_PART_NUMBER") "633-SS12SDP2"))
      (libsource (lib "eagle-import") (part "SS12SDP2"))
    )
    (comp (ref "S6")
      (value "SS12SDP2")
      (footprint "eagle-import:SS12SDP2")
      (fields (field (name "MOUSER_PART_NUMBER") "633-SS12SDP2"))
      (libsource (lib "eagle-import") (part "SS12SDP2"))
    )
    (comp (ref "S7")
      (value "SS12SDP2")
      (footprint "eagle-import:SS12SDP2")
      (fields (field (name "MOUSER_PART_NUMBER") "633-SS12SDP2"))
      (libsource (lib "eagle-import") (part "SS12SDP2"))
    )
    (comp (ref "S8")
      (value "SS12SDP2")
      (footprint "eagle-import:SS12SDP2")
      (fields (field (name "MOUSER_PART_NUMBER") "633-SS12SDP2"))
      (libsource (lib "eagle-import") (part "SS12SDP2"))
    )
    (comp (ref "S9")
      (value "SS12SDP2")
      (footprint "eagle-import:SS12SDP2")
      (fields (field (name "MOUSER_PART_NUMBER") "633-SS12SDP2"))
      (libsource (lib "eagle-import") (part "SS12SDP2"))
    )
    (comp (ref "S10")
      (value "SS12SDP2")
      (footprint "eagle-import:SS12SDP2")
      (fields (field (name "MOUSER_PART_NUMBER") "633-SS12SDP2"))
      (libsource (lib "eagle-import") (part "SS12SDP2"))
    )
    (comp (ref "S11")
      (value "SS12SDP2")
      (footprint "eagle-import:SS12SDP2")
      (fields (field (name "MOUSER_PART_NUMBER") "633-SS12SDP2"))
      (libsource (lib "eagle-import") (part "SS12SDP2"))
    )
    (comp (ref "S12")
      (value "SS12SDP2")
      (footprint "eagle-import:SS12SDP2")
      (fields (field (name "MOUSER_PART_NUMBER") "633-SS12SDP2"))
      (libsource (lib "eagle-import") (part "SS12SDP2"))
    )
    (comp (ref "S13")
      (value "SS12SDP2")
      (footprint "eagle-import:SS12SDP2")
      (fields (field (name "MOUSER_PART_NUMBER") "633-SS12SDP2"))
      (libsource (lib "eagle-import") (part "SS12SDP2"))
    )
    (comp (ref "S14")
      (value "SS12SDP2")
      (footprint "eagle-import:SS12SDP2")
      (fields (field (name "MOUSER_PART_NUMBER") "633-SS12SDP2"))
      (libsource (lib "eagle-import") (part "SS12SDP2"))
    )
    (comp (ref "S15")
      (value "SS12SDP2")
      (footprint "eagle-import:SS12SDP2")
      (fields (field (name "MOUSER_PART_NUMBER") "633-SS12SDP2"))
      (libsource (lib "eagle-import") (part "SS12SDP2"))
    )
    (comp (ref "S16")
      (value "SS12SDP2")
      (footprint "eagle-import:SS12SDP2")
      (fields (field (name "MOUSER_PART_NUMBER") "633-SS12SDP2"))
      (libsource (lib "eagle-import") (part "SS12SDP2"))
    )
    (comp (ref "S19")
      (value "SS12SDP2")
      (footprint "eagle-import:SS12SDP2")
      (fields (field (name "MOUSER_PART_NUMBER") "633-SS12SDP2"))
      (libsource (lib "eagle-import") (part "SS12SDP2"))
    )
    (comp (ref "S20")
      (value "SS12SDP2")
      (footprint "eagle-import:SS12SDP2")
      (fields (field (name "MOUSER_PART_NUMBER") "633-SS12SDP2"))
      (libsource (lib "eagle-import") (part "SS12SDP2"))
    )
    (comp (ref "SPI_OPEN8_1")
      (value "SPI1")
      (footprint "eagle-import:FE10")
      (libsource (lib "eagle-import") (part "FE10-1"))
    )
    (comp (ref "SPI_OPEN8_2")
      (value "SPI0")
      (footprint "eagle-import:FE10")
      (libsource (lib "eagle-import") (part "FE10-1"))
    )
    (comp (ref "SPI_SERV_1")
      (value "SPI1")
      (footprint "eagle-import:FE10")
      (libsource (lib "eagle-import") (part "FE10-1"))
    )
    (comp (ref "SPI_SERV_2")
      (value "SPI0")
      (footprint "eagle-import:FE10")
      (libsource (lib "eagle-import") (part "FE10-1"))
    )
    (comp (ref "SWITCH_OPEN8")
      (value "PINHD-2X8")
      (footprint "eagle-import:2X08")
      (libsource (lib "eagle-import") (part "PINHD-2X8"))
    )
    (comp (ref "SWITCH_SERV")
      (value "PINHD-2X8")
      (footprint "eagle-import:2X08")
      (libsource (lib "eagle-import") (part "PINHD-2X8"))
    )
    (comp (ref "U$1")
      (value "2X41_HEADER")
      (footprint "eagle-import:2X41_HEADER")
      (libsource (lib "eagle-import") (part "2X41_HEADER"))
    )
    (comp (ref "U$2")
      (value "2X41_HEADER")
      (footprint "eagle-import:2X41_HEADER")
      (libsource (lib "eagle-import") (part "2X41_HEADER"))
    )
    (comp (ref "U$3")
      (value "2X41_HEADER")
      (footprint "eagle-import:2X41_HEADER")
      (libsource (lib "eagle-import") (part "2X41_HEADER"))
    )
    (comp (ref "U$4")
      (value "2X41_HEADER")
      (footprint "eagle-import:2X41_HEADER")
      (libsource (lib "eagle-import") (part "2X41_HEADER"))
    )
    (comp (ref "U1")
      (value "TPS76201DBVR")
      (footprint "eagle-import:SOT95P280X145-5N")
      (fields (field (name "MF") "Texas Instruments"))
      (libsource (lib "eagle-import") (part "TPS76201DBVR"))
    )
    (comp (ref "U2")
      (value "TPS76201DBVR")
      (footprint "eagle-import:SOT95P280X145-5N")
      (fields (field (name "MF") "Texas Instruments"))
      (libsource (lib "eagle-import") (part "TPS76201DBVR"))
    )
    (comp (ref "U3")
      (value "TPS76201DBVR")
      (footprint "eagle-import:SOT95P280X145-5N")
      (fields (field (name "MF") "Texas Instruments"))
      (libsource (lib "eagle-import") (part "TPS76201DBVR"))
    )
    (comp (ref "U4")
      (value "TPS76201DBVR")
      (footprint "eagle-import:SOT95P280X145-5N")
      (fields (field (name "MF") "Texas Instruments"))
      (libsource (lib "eagle-import") (part "TPS76201DBVR"))
    )
    (comp (ref "USB-UART_OPEN8_1")
      (value "PINHD-1X4")
      (footprint "eagle-import:1X04")
      (libsource (lib "eagle-import") (part "PINHD-1X4"))
    )
    (comp (ref "USB-UART_OPEN8_2")
      (value "PINHD-1X4")
      (footprint "eagle-import:1X04")
      (libsource (lib "eagle-import") (part "PINHD-1X4"))
    )
    (comp (ref "USB-UART_SERV_1")
      (value "PINHD-1X4")
      (footprint "eagle-import:1X04")
      (libsource (lib "eagle-import") (part "PINHD-1X4"))
    )
    (comp (ref "USB-UART_SERV_2")
      (value "PINHD-1X4")
      (footprint "eagle-import:1X04")
      (libsource (lib "eagle-import") (part "PINHD-1X4"))
    )
    (comp (ref "Y2")
      (value "HC-49SM8MHZ20PF30PPM")
      (footprint "eagle-import:HC49SM8MHZ20PF30PPM")
      (fields (field (name "MANUFACTURER_PART_NUMBER") "HC-49SM8MHz20pF30ppm"))
      (libsource (lib "eagle-import") (part "HC-49SM8MHZ20PF30PPM"))
    )
    (comp (ref "Y3")
      (value "Q13FC1350000400")
      (footprint "eagle-import:Q13FC1350000400")
      (libsource (lib "eagle-import") (part "Q13FC1350000400"))
    )
  )
  (nets
    (net (code "1") (name "1") (class "Default")
      (node (ref "U$1") (pin "1") (pinfunction "1_1") (pintype "bidirectional"))
    )
    (net (code "2") (name "2") (class "Default")
      (node (ref "U$1") (pin "4") (pinfunction "4_4") (pintype "bidirectional"))
    )
    (net (code "3") (name "3") (class "Default")
      (node (ref "U$1") (pin "3") (pinfunction "3_3") (pintype "bidirectional"))
    )
    (net (code "4") (name "8MHZ_CLOCK") (class "Default")
      (node (ref "CLOCK") (pin "3") (pinfunction "3_3") (pintype "passive"))
      (node (ref "IC1") (pin "4") (pinfunction "Y_4") (pintype "bidirectional"))
      (node (ref "R18") (pin "2") (pinfunction "2_2") (pintype "passive"))
      (node (ref "R4") (pin "2") (pinfunction "2_2") (pintype "passive"))
    )
    (net (code "5") (name "32KHZ_CLOCK") (class "Default")
      (node (ref "CLOCK") (pin "1") (pinfunction "1_1") (pintype "passive"))
      (node (ref "IC2") (pin "4") (pinfunction "Y_4") (pintype "bidirectional"))
      (node (ref "R20") (pin "2") (pinfunction "2_2") (pintype "passive"))
      (node (ref "R29") (pin "2") (pinfunction "2_2") (pintype "passive"))
    )
    (net (code "6") (name "37") (class "Default")
      (node (ref "U$1") (pin "37") (pinfunction "37_37") (pintype "bidirectional"))
    )
    (net (code "7") (name "38") (class "Default")
      (node (ref "U$1") (pin "40") (pinfunction "40_40") (pintype "bidirectional"))
    )
    (net (code "8") (name "39") (class "Default")
      (node (ref "U$1") (pin "39") (pinfunction "39_39") (pintype "bidirectional"))
    )
    (net (code "9") (name "40") (class "Default")
      (node (ref "U$1") (pin "42") (pinfunction "42_42") (pintype "bidirectional"))
    )
    (net (code "10") (name "41") (class "Default")
      (node (ref "U$2") (pin "1") (pinfunction "1_1") (pintype "bidirectional"))
    )
    (net (code "11") (name "42") (class "Default")
      (node (ref "U$2") (pin "4") (pinfunction "4_4") (pintype "bidirectional"))
    )
    (net (code "12") (name "43") (class "Default")
      (node (ref "U$2") (pin "3") (pinfunction "3_3") (pintype "bidirectional"))
    )
    (net (code "13") (name "44") (class "Default")
      (node (ref "U$2") (pin "6") (pinfunction "6_6") (pintype "bidirectional"))
    )
    (net (code "14") (name "45") (class "Default")
      (node (ref "U$2") (pin "5") (pinfunction "5_5") (pintype "bidirectional"))
    )
    (net (code "15") (name "46") (class "Default")
      (node (ref "U$2") (pin "8") (pinfunction "8_8") (pintype "bidirectional"))
    )
    (net (code "16") (name "47") (class "Default")
      (node (ref "U$2") (pin "7") (pinfunction "7_7") (pintype "bidirectional"))
    )
    (net (code "17") (name "48") (class "Default")
      (node (ref "U$2") (pin "10") (pinfunction "10_10") (pintype "bidirectional"))
    )
    (net (code "18") (name "49") (class "Default")
      (node (ref "U$2") (pin "9") (pinfunction "9_9") (pintype "bidirectional"))
    )
    (net (code "19") (name "50") (class "Default")
      (node (ref "U$2") (pin "12") (pinfunction "12_12") (pintype "bidirectional"))
    )
    (net (code "20") (name "51") (class "Default")
      (node (ref "U$2") (pin "11") (pinfunction "11_11") (pintype "bidirectional"))
    )
    (net (code "21") (name "52") (class "Default")
      (node (ref "U$2") (pin "14") (pinfunction "14_14") (pintype "bidirectional"))
    )
    (net (code "22") (name "68") (class "Default")
      (node (ref "U$2") (pin "30") (pinfunction "30_30") (pintype "bidirectional"))
    )
    (net (code "23") (name "69") (class "Default")
      (node (ref "U$2") (pin "29") (pinfunction "29_29") (pintype "bidirectional"))
    )
    (net (code "24") (name "70") (class "Default")
      (node (ref "U$2") (pin "32") (pinfunction "32_32") (pintype "bidirectional"))
    )
    (net (code "25") (name "71") (class "Default")
      (node (ref "U$2") (pin "31") (pinfunction "31_31") (pintype "bidirectional"))
    )
    (net (code "26") (name "72") (class "Default")
      (node (ref "U$2") (pin "34") (pinfunction "34_34") (pintype "bidirectional"))
    )
    (net (code "27") (name "73") (class "Default")
      (node (ref "U$2") (pin "33") (pinfunction "33_33") (pintype "bidirectional"))
    )
    (net (code "28") (name "74") (class "Default")
      (node (ref "U$2") (pin "36") (pinfunction "36_36") (pintype "bidirectional"))
    )
    (net (code "29") (name "75") (class "Default")
      (node (ref "U$2") (pin "35") (pinfunction "35_35") (pintype "bidirectional"))
    )
    (net (code "30") (name "76") (class "Default")
      (node (ref "U$2") (pin "38") (pinfunction "38_38") (pintype "bidirectional"))
    )
    (net (code "31") (name "77") (class "Default")
      (node (ref "U$2") (pin "37") (pinfunction "37_37") (pintype "bidirectional"))
    )
    (net (code "32") (name "78") (class "Default")
      (node (ref "U$2") (pin "40") (pinfunction "40_40") (pintype "bidirectional"))
    )
    (net (code "33") (name "79") (class "Default")
      (node (ref "U$2") (pin "39") (pinfunction "39_39") (pintype "bidirectional"))
    )
    (net (code "34") (name "80") (class "Default")
      (node (ref "U$2") (pin "42") (pinfunction "42_42") (pintype "bidirectional"))
    )
    (net (code "35") (name "81") (class "Default")
      (node (ref "U$3") (pin "1") (pinfunction "1_1") (pintype "bidirectional"))
    )
    (net (code "36") (name "82") (class "Default")
      (node (ref "U$3") (pin "4") (pinfunction "4_4") (pintype "bidirectional"))
    )
    (net (code "37") (name "83") (class "Default")
      (node (ref "U$3") (pin "3") (pinfunction "3_3") (pintype "bidirectional"))
    )
    (net (code "38") (name "117") (class "Default")
      (node (ref "U$3") (pin "37") (pinfunction "37_37") (pintype "bidirectional"))
    )
    (net (code "39") (name "118") (class "Default")
      (node (ref "U$3") (pin "40") (pinfunction "40_40") (pintype "bidirectional"))
    )
    (net (code "40") (name "119") (class "Default")
      (node (ref "U$3") (pin "39") (pinfunction "39_39") (pintype "bidirectional"))
    )
    (net (code "41") (name "120") (class "Default")
      (node (ref "U$3") (pin "42") (pinfunction "42_42") (pintype "bidirectional"))
    )
    (net (code "42") (name "121") (class "Default")
      (node (ref "U$4") (pin "1") (pinfunction "1_1") (pintype "bidirectional"))
    )
    (net (code "43") (name "122") (class "Default")
      (node (ref "U$4") (pin "4") (pinfunction "4_4") (pintype "bidirectional"))
    )
    (net (code "44") (name "123") (class "Default")
      (node (ref "U$4") (pin "3") (pinfunction "3_3") (pintype "bidirectional"))
    )
    (net (code "45") (name "124") (class "Default")
      (node (ref "U$4") (pin "6") (pinfunction "6_6") (pintype "bidirectional"))
    )
    (net (code "46") (name "125") (class "Default")
      (node (ref "U$4") (pin "5") (pinfunction "5_5") (pintype "bidirectional"))
    )
    (net (code "47") (name "126") (class "Default")
      (node (ref "U$4") (pin "8") (pinfunction "8_8") (pintype "bidirectional"))
    )
    (net (code "48") (name "127") (class "Default")
      (node (ref "U$4") (pin "7") (pinfunction "7_7") (pintype "bidirectional"))
    )
    (net (code "49") (name "128") (class "Default")
      (node (ref "U$4") (pin "10") (pinfunction "10_10") (pintype "bidirectional"))
    )
    (net (code "50") (name "129") (class "Default")
      (node (ref "U$4") (pin "9") (pinfunction "9_9") (pintype "bidirectional"))
    )
    (net (code "51") (name "130") (class "Default")
      (node (ref "U$4") (pin "12") (pinfunction "12_12") (pintype "bidirectional"))
    )
    (net (code "52") (name "131") (class "Default")
      (node (ref "U$4") (pin "11") (pinfunction "11_11") (pintype "bidirectional"))
    )
    (net (code "53") (name "132") (class "Default")
      (node (ref "U$4") (pin "14") (pinfunction "14_14") (pintype "bidirectional"))
    )
    (net (code "54") (name "148") (class "Default")
      (node (ref "U$4") (pin "30") (pinfunction "30_30") (pintype "bidirectional"))
    )
    (net (code "55") (name "149") (class "Default")
      (node (ref "U$4") (pin "29") (pinfunction "29_29") (pintype "bidirectional"))
    )
    (net (code "56") (name "150") (class "Default")
      (node (ref "U$4") (pin "32") (pinfunction "32_32") (pintype "bidirectional"))
    )
    (net (code "57") (name "151") (class "Default")
      (node (ref "U$4") (pin "31") (pinfunction "31_31") (pintype "bidirectional"))
    )
    (net (code "58") (name "152") (class "Default")
      (node (ref "U$4") (pin "34") (pinfunction "34_34") (pintype "bidirectional"))
    )
    (net (code "59") (name "153") (class "Default")
      (node (ref "U$4") (pin "33") (pinfunction "33_33") (pintype "bidirectional"))
    )
    (net (code "60") (name "154") (class "Default")
      (node (ref "U$4") (pin "36") (pinfunction "36_36") (pintype "bidirectional"))
    )
    (net (code "61") (name "155") (class "Default")
      (node (ref "U$4") (pin "35") (pinfunction "35_35") (pintype "bidirectional"))
    )
    (net (code "62") (name "156") (class "Default")
      (node (ref "U$4") (pin "38") (pinfunction "38_38") (pintype "bidirectional"))
    )
    (net (code "63") (name "157") (class "Default")
      (node (ref "U$4") (pin "37") (pinfunction "37_37") (pintype "bidirectional"))
    )
    (net (code "64") (name "158") (class "Default")
      (node (ref "U$4") (pin "40") (pinfunction "40_40") (pintype "bidirectional"))
    )
    (net (code "65") (name "159") (class "Default")
      (node (ref "U$4") (pin "39") (pinfunction "39_39") (pintype "bidirectional"))
    )
    (net (code "66") (name "160") (class "Default")
      (node (ref "U$4") (pin "42") (pinfunction "42_42") (pintype "bidirectional"))
    )
    (net (code "67") (name "CLOCK") (class "Default")
      (node (ref "CLOCK") (pin "2") (pinfunction "2_2") (pintype "passive"))
      (node (ref "CLOCK") (pin "4") (pinfunction "4_4") (pintype "passive"))
      (node (ref "CLOCK") (pin "6") (pinfunction "6_6") (pintype "passive"))
      (node (ref "U$1") (pin "33") (pinfunction "33_33") (pintype "bidirectional"))
      (node (ref "U$3") (pin "35") (pinfunction "35_35") (pintype "bidirectional"))
    )
    (net (code "68") (name "CLOCK_SERV_XO") (class "Default")
      (node (ref "U$1") (pin "36") (pinfunction "36_36") (pintype "bidirectional"))
    )
    (net (code "69") (name "CLOCK_XO") (class "Default")
      (node (ref "U$3") (pin "36") (pinfunction "36_36") (pintype "bidirectional"))
    )
    (net (code "70") (name "DIPSW_0") (class "Default")
      (node (ref "SWITCH_OPEN8") (pin "1") (pinfunction "1_1") (pintype "passive"))
      (node (ref "U$3") (pin "25") (pinfunction "25_25") (pintype "bidirectional"))
    )
    (net (code "71") (name "DIPSW_1") (class "Default")
      (node (ref "SWITCH_OPEN8") (pin "3") (pinfunction "3_3") (pintype "passive"))
      (node (ref "U$3") (pin "26") (pinfunction "26_26") (pintype "bidirectional"))
    )
    (net (code "72") (name "DIPSW_2") (class "Default")
      (node (ref "SWITCH_OPEN8") (pin "5") (pinfunction "5_5") (pintype "passive"))
      (node (ref "U$3") (pin "23") (pinfunction "23_23") (pintype "bidirectional"))
    )
    (net (code "73") (name "DIPSW_3") (class "Default")
      (node (ref "SWITCH_OPEN8") (pin "7") (pinfunction "7_7") (pintype "passive"))
      (node (ref "U$3") (pin "24") (pinfunction "24_24") (pintype "bidirectional"))
    )
    (net (code "74") (name "DIPSW_4") (class "Default")
      (node (ref "SWITCH_OPEN8") (pin "9") (pinfunction "9_9") (pintype "passive"))
      (node (ref "U$3") (pin "21") (pinfunction "21_21") (pintype "bidirectional"))
    )
    (net (code "75") (name "DIPSW_5") (class "Default")
      (node (ref "SWITCH_OPEN8") (pin "11") (pinfunction "11_11") (pintype "passive"))
      (node (ref "U$3") (pin "16") (pinfunction "16_16") (pintype "bidirectional"))
    )
    (net (code "76") (name "DIPSW_6") (class "Default")
      (node (ref "SWITCH_OPEN8") (pin "13") (pinfunction "13_13") (pintype "passive"))
      (node (ref "U$3") (pin "13") (pinfunction "13_13") (pintype "bidirectional"))
    )
    (net (code "77") (name "DIPSW_7") (class "Default")
      (node (ref "SWITCH_OPEN8") (pin "15") (pinfunction "15_15") (pintype "passive"))
      (node (ref "U$3") (pin "14") (pinfunction "14_14") (pintype "bidirectional"))
    )
    (net (code "78") (name "DIPSW_SERV_0") (class "Default")
      (node (ref "SWITCH_SERV") (pin "1") (pinfunction "1_1") (pintype "passive"))
      (node (ref "U$1") (pin "21") (pinfunction "21_21") (pintype "bidirectional"))
    )
    (net (code "79") (name "DIPSW_SERV_1") (class "Default")
      (node (ref "SWITCH_SERV") (pin "3") (pinfunction "3_3") (pintype "passive"))
      (node (ref "U$1") (pin "22") (pinfunction "22_22") (pintype "bidirectional"))
    )
    (net (code "80") (name "DIPSW_SERV_2") (class "Default")
      (node (ref "SWITCH_SERV") (pin "5") (pinfunction "5_5") (pintype "passive"))
      (node (ref "U$1") (pin "19") (pinfunction "19_19") (pintype "bidirectional"))
    )
    (net (code "81") (name "DIPSW_SERV_3") (class "Default")
      (node (ref "SWITCH_SERV") (pin "7") (pinfunction "7_7") (pintype "passive"))
      (node (ref "U$1") (pin "20") (pinfunction "20_20") (pintype "bidirectional"))
    )
    (net (code "82") (name "DIPSW_SERV_4") (class "Default")
      (node (ref "SWITCH_SERV") (pin "9") (pinfunction "9_9") (pintype "passive"))
      (node (ref "U$1") (pin "17") (pinfunction "17_17") (pintype "bidirectional"))
    )
    (net (code "83") (name "DIPSW_SERV_5") (class "Default")
      (node (ref "SWITCH_SERV") (pin "11") (pinfunction "11_11") (pintype "passive"))
      (node (ref "U$1") (pin "18") (pinfunction "18_18") (pintype "bidirectional"))
    )
    (net (code "84") (name "DIPSW_SERV_6") (class "Default")
      (node (ref "SWITCH_SERV") (pin "13") (pinfunction "13_13") (pintype "passive"))
      (node (ref "U$1") (pin "15") (pinfunction "15_15") (pintype "bidirectional"))
    )
    (net (code "85") (name "DIPSW_SERV_7") (class "Default")
      (node (ref "SWITCH_SERV") (pin "15") (pinfunction "15_15") (pintype "passive"))
      (node (ref "U$1") (pin "16") (pinfunction "16_16") (pintype "bidirectional"))
    )
    (net (code "86") (name "GND") (class "Default")
      (node (ref "C1") (pin "2") (pinfunction "2_2") (pintype "passive"))
      (node (ref "C10") (pin "1") (pinfunction "1_1") (pintype "passive"))
      (node (ref "C11") (pin "2") (pinfunction "2_2") (pintype "passive"))
      (node (ref "C12") (pin "1") (pinfunction "1_1") (pintype "passive"))
      (node (ref "C14") (pin "2") (pinfunction "2_2") (pintype "passive"))
      (node (ref "C15") (pin "2") (pinfunction "2_2") (pintype "passive"))
      (node (ref "C16") (pin "2") (pinfunction "2_2") (pintype "passive"))
      (node (ref "C17") (pin "2") (pinfunction "2_2") (pintype "passive"))
      (node (ref "C19") (pin "2") (pinfunction "2_2") (pintype "passive"))
      (node (ref "C20") (pin "2") (pinfunction "2_2") (pintype "passive"))
      (node (ref "C21") (pin "2") (pinfunction "2_2") (pintype "passive"))
      (node (ref "C22") (pin "2") (pinfunction "2_2") (pintype "passive"))
      (node (ref "C3") (pin "2") (pinfunction "2_2") (pintype "passive"))
      (node (ref "C5") (pin "2") (pinfunction "2_2") (pintype "passive"))
      (node (ref "C6") (pin "2") (pinfunction "2_2") (pintype "passive"))
      (node (ref "C9") (pin "2") (pinfunction "2_2") (pintype "passive"))
      (node (ref "FLASH_OPEN8") (pin "3") (pinfunction "3_3") (pintype "passive"))
      (node (ref "FLASH_OPEN8") (pin "4") (pinfunction "4_4") (pintype "passive"))
      (node (ref "FLASH_SERV") (pin "3") (pinfunction "3_3") (pintype "passive"))
      (node (ref "FLASH_SERV") (pin "4") (pinfunction "4_4") (pintype "passive"))
      (node (ref "GND") (pin "1") (pinfunction "1_1") (pintype "passive"))
      (node (ref "GND") (pin "2") (pinfunction "2_2") (pintype "passive"))
      (node (ref "GND") (pin "3") (pinfunction "3_3") (pintype "passive"))
      (node (ref "GND") (pin "4") (pinfunction "4_4") (pintype "passive"))
      (node (ref "GND") (pin "5") (pinfunction "5_5") (pintype "passive"))
      (node (ref "GND") (pin "6") (pinfunction "6_6") (pintype "passive"))
      (node (ref "J4") (pin "1") (pinfunction "1_1") (pintype "bidirectional"))
      (node (ref "J4") (pin "2") (pinfunction "2_2") (pintype "bidirectional"))
      (node (ref "J4") (pin "3") (pinfunction "3_3") (pintype "bidirectional"))
      (node (ref "J4") (pin "4") (pinfunction "4_4") (pintype "bidirectional"))
      (node (ref "JTAG_OPEN8") (pin "10") (pinfunction "10_10") (pintype "passive"))
      (node (ref "JTAG_OPEN8") (pin "12") (pinfunction "12_12") (pintype "passive"))
      (node (ref "JTAG_OPEN8") (pin "14") (pinfunction "14_14") (pintype "passive"))
      (node (ref "JTAG_OPEN8") (pin "16") (pinfunction "16_16") (pintype "passive"))
      (node (ref "JTAG_OPEN8") (pin "18") (pinfunction "18_18") (pintype "passive"))
      (node (ref "JTAG_OPEN8") (pin "20") (pinfunction "20_20") (pintype "passive"))
      (node (ref "JTAG_OPEN8") (pin "4") (pinfunction "4_4") (pintype "passive"))
      (node (ref "JTAG_OPEN8") (pin "6") (pinfunction "6_6") (pintype "passive"))
      (node (ref "JTAG_OPEN8") (pin "8") (pinfunction "8_8") (pintype "passive"))
      (node (ref "JTAG_SERV") (pin "10") (pinfunction "10_10") (pintype "passive"))
      (node (ref "JTAG_SERV") (pin "12") (pinfunction "12_12") (pintype "passive"))
      (node (ref "JTAG_SERV") (pin "14") (pinfunction "14_14") (pintype "passive"))
      (node (ref "JTAG_SERV") (pin "16") (pinfunction "16_16") (pintype "passive"))
      (node (ref "JTAG_SERV") (pin "18") (pinfunction "18_18") (pintype "passive"))
      (node (ref "JTAG_SERV") (pin "20") (pinfunction "20_20") (pintype "passive"))
      (node (ref "JTAG_SERV") (pin "4") (pinfunction "4_4") (pintype "passive"))
      (node (ref "JTAG_SERV") (pin "6") (pinfunction "6_6") (pintype "passive"))
      (node (ref "JTAG_SERV") (pin "8") (pinfunction "8_8") (pintype "passive"))
      (node (ref "LORA_OPEN8") (pin "P$1") (pinfunction "GND_1_P$1") (pintype "bidirectional"))
      (node (ref "LORA_OPEN8") (pin "P$15") (pinfunction "GND_3_P$15") (pintype "bidirectional"))
      (node (ref "LORA_OPEN8") (pin "P$8") (pinfunction "GND_2_P$8") (pintype "bidirectional"))
      (node (ref "LORA_SERV") (pin "P$1") (pinfunction "GND_1_P$1") (pintype "bidirectional"))
      (node (ref "LORA_SERV") (pin "P$15") (pinfunction "GND_3_P$15") (pintype "bidirectional"))
      (node (ref "LORA_SERV") (pin "P$8") (pinfunction "GND_2_P$8") (pintype "bidirectional"))
      (node (ref "Q1") (pin "2") (pinfunction "S_2") (pintype "bidirectional"))
      (node (ref "Q10") (pin "2") (pinfunction "S_2") (pintype "bidirectional"))
      (node (ref "Q11") (pin "2") (pinfunction "S_2") (pintype "bidirectional"))
      (node (ref "Q14") (pin "2") (pinfunction "S_2") (pintype "bidirectional"))
      (node (ref "Q15") (pin "2") (pinfunction "S_2") (pintype "bidirectional"))
      (node (ref "Q16") (pin "2") (pinfunction "S_2") (pintype "bidirectional"))
      (node (ref "Q17") (pin "2") (pinfunction "S_2") (pintype "bidirectional"))
      (node (ref "Q18") (pin "2") (pinfunction "S_2") (pintype "bidirectional"))
      (node (ref "Q19") (pin "2") (pinfunction "S_2") (pintype "bidirectional"))
      (node (ref "Q2") (pin "2") (pinfunction "S_2") (pintype "bidirectional"))
      (node (ref "Q25") (pin "2") (pinfunction "S_2") (pintype "bidirectional"))
      (node (ref "Q26") (pin "2") (pinfunction "S_2") (pintype "bidirectional"))
      (node (ref "Q27") (pin "2") (pinfunction "S_2") (pintype "bidirectional"))
      (node (ref "Q28") (pin "2") (pinfunction "S_2") (pintype "bidirectional"))
      (node (ref "Q3") (pin "2") (pinfunction "S_2") (pintype "bidirectional"))
      (node (ref "Q4") (pin "2") (pinfunction "S_2") (pintype "bidirectional"))
      (node (ref "Q5") (pin "2") (pinfunction "S_2") (pintype "bidirectional"))
      (node (ref "Q6") (pin "2") (pinfunction "S_2") (pintype "bidirectional"))
      (node (ref "Q7") (pin "2") (pinfunction "S_2") (pintype "bidirectional"))
      (node (ref "Q8") (pin "2") (pinfunction "S_2") (pintype "bidirectional"))
      (node (ref "Q9") (pin "2") (pinfunction "S_2") (pintype "bidirectional"))
      (node (ref "R1") (pin "1") (pinfunction "1_1") (pintype "passive"))
      (node (ref "R13") (pin "1") (pinfunction "1_1") (pintype "passive"))
      (node (ref "R14") (pin "1") (pinfunction "1_1") (pintype "passive"))
      (node (ref "R16") (pin "1") (pinfunction "1_1") (pintype "passive"))
      (node (ref "R17") (pin "1") (pinfunction "1_1") (pintype "passive"))
      (node (ref "R2") (pin "1") (pinfunction "1_1") (pintype "passive"))
      (node (ref "R28") (pin "1") (pinfunction "1_1") (pintype "passive"))
      (node (ref "R38") (pin "1") (pinfunction "1_1") (pintype "passive"))
      (node (ref "R39") (pin "1") (pinfunction "1_1") (pintype "passive"))
      (node (ref "R48") (pin "1") (pinfunction "1_1") (pintype "passive"))
      (node (ref "R49") (pin "1") (pinfunction "1_1") (pintype "passive"))
      (node (ref "R50") (pin "1") (pinfunction "1_1") (pintype "passive"))
      (node (ref "R51") (pin "1") (pinfunction "1_1") (pintype "passive"))
      (node (ref "R52") (pin "1") (pinfunction "1_1") (pintype "passive"))
      (node (ref "R53") (pin "1") (pinfunction "1_1") (pintype "passive"))
      (node (ref "R54") (pin "1") (pinfunction "1_1") (pintype "passive"))
      (node (ref "R55") (pin "1") (pinfunction "1_1") (pintype "passive"))
      (node (ref "R56") (pin "1") (pinfunction "1_1") (pintype "passive"))
      (node (ref "R57") (pin "1") (pinfunction "1_1") (pintype "passive"))
      (node (ref "R58") (pin "1") (pinfunction "1_1") (pintype "passive"))
      (node (ref "R59") (pin "1") (pinfunction "1_1") (pintype "passive"))
      (node (ref "R6") (pin "1") (pinfunction "1_1") (pintype "passive"))
      (node (ref "R60") (pin "1") (pinfunction "1_1") (pintype "passive"))
      (node (ref "R61") (pin "1") (pinfunction "1_1") (pintype "passive"))
      (node (ref "R63") (pin "1") (pinfunction "1_1") (pintype "passive"))
      (node (ref "R65") (pin "1") (pinfunction "1_1") (pintype "passive"))
      (node (ref "R7") (pin "1") (pinfunction "1_1") (pintype "passive"))
      (node (ref "R78") (pin "1") (pinfunction "1_1") (pintype "passive"))
      (node (ref "R8") (pin "1") (pinfunction "1_1") (pintype "passive"))
      (node (ref "R80") (pin "1") (pinfunction "1_1") (pintype "passive"))
      (node (ref "R91") (pin "1") (pinfunction "1_1") (pintype "passive"))
      (node (ref "S1") (pin "3") (pinfunction "ON_2_3") (pintype "bidirectional"))
      (node (ref "S10") (pin "3") (pinfunction "ON_2_3") (pintype "bidirectional"))
      (node (ref "S11") (pin "3") (pinfunction "ON_2_3") (pintype "bidirectional"))
      (node (ref "S12") (pin "3") (pinfunction "ON_2_3") (pintype "bidirectional"))
      (node (ref "S13") (pin "3") (pinfunction "ON_2_3") (pintype "bidirectional"))
      (node (ref "S14") (pin "3") (pinfunction "ON_2_3") (pintype "bidirectional"))
      (node (ref "S15") (pin "3") (pinfunction "ON_2_3") (pintype "bidirectional"))
      (node (ref "S16") (pin "3") (pinfunction "ON_2_3") (pintype "bidirectional"))
      (node (ref "S19") (pin "3") (pinfunction "ON_2_3") (pintype "bidirectional"))
      (node (ref "S2") (pin "3") (pinfunction "ON_2_3") (pintype "bidirectional"))
      (node (ref "S20") (pin "3") (pinfunction "ON_2_3") (pintype "bidirectional"))
      (node (ref "S3") (pin "3") (pinfunction "ON_2_3") (pintype "bidirectional"))
      (node (ref "S4") (pin "3") (pinfunction "ON_2_3") (pintype "bidirectional"))
      (node (ref "S5") (pin "3") (pinfunction "ON_2_3") (pintype "bidirectional"))
      (node (ref "S6") (pin "3") (pinfunction "ON_2_3") (pintype "bidirectional"))
      (node (ref "S7") (pin "3") (pinfunction "ON_2_3") (pintype "bidirectional"))
      (node (ref "S8") (pin "3") (pinfunction "ON_2_3") (pintype "bidirectional"))
      (node (ref "S9") (pin "3") (pinfunction "ON_2_3") (pintype "bidirectional"))
      (node (ref "SPI_OPEN8_2") (pin "10") (pinfunction "10_10") (pintype "passive"))
      (node (ref "SPI_SERV_2") (pin "10") (pinfunction "10_10") (pintype "passive"))
      (node (ref "U$1") (pin "24") (pinfunction "24_24") (pintype "bidirectional"))
      (node (ref "U$2") (pin "20") (pinfunction "20_20") (pintype "bidirectional"))
      (node (ref "U$2") (pin "22") (pinfunction "22_22") (pintype "bidirectional"))
      (node (ref "U$3") (pin "19") (pinfunction "19_19") (pintype "bidirectional"))
      (node (ref "U$3") (pin "22") (pinfunction "22_22") (pintype "bidirectional"))
      (node (ref "U$4") (pin "21") (pinfunction "21_21") (pintype "bidirectional"))
      (node (ref "U$4") (pin "22") (pinfunction "22_22") (pintype "bidirectional"))
      (node (ref "U$4") (pin "24") (pinfunction "24_24") (pintype "bidirectional"))
      (node (ref "U1") (pin "2") (pinfunction "GND_2") (pintype "power_in"))
      (node (ref "U1") (pin "3") (pinfunction "~{EN}_3") (pintype "input"))
      (node (ref "U2") (pin "2") (pinfunction "GND_2") (pintype "power_in"))
      (node (ref "U2") (pin "3") (pinfunction "~{EN}_3") (pintype "input"))
      (node (ref "U3") (pin "2") (pinfunction "GND_2") (pintype "power_in"))
      (node (ref "U3") (pin "3") (pinfunction "~{EN}_3") (pintype "input"))
      (node (ref "U4") (pin "2") (pinfunction "GND_2") (pintype "power_in"))
      (node (ref "U4") (pin "3") (pinfunction "~{EN}_3") (pintype "input"))
      (node (ref "USB-UART_OPEN8_1") (pin "1") (pinfunction "1_1") (pintype "passive"))
      (node (ref "USB-UART_SERV_1") (pin "1") (pinfunction "1_1") (pintype "passive"))
    )
    (net (code "87") (name "IN_12_OPEN8") (class "Default")
      (node (ref "C6") (pin "1") (pinfunction "1_1") (pintype "passive"))
      (node (ref "IN_12_OPEN8") (pin "2") (pinfunction "2_2") (pintype "passive"))
      (node (ref "U4") (pin "1") (pinfunction "IN_1") (pintype "input"))
    )
    (net (code "88") (name "IN_12_SERV") (class "Default")
      (node (ref "C1") (pin "1") (pinfunction "1_1") (pintype "passive"))
      (node (ref "IN_12_SERV") (pin "2") (pinfunction "2_2") (pintype "passive"))
      (node (ref "U1") (pin "1") (pinfunction "IN_1") (pintype "input"))
    )
    (net (code "89") (name "IN_12_VDD") (class "Default")
      (node (ref "C5") (pin "1") (pinfunction "1_1") (pintype "passive"))
      (node (ref "IN_12_VDD") (pin "2") (pinfunction "2_2") (pintype "passive"))
      (node (ref "U3") (pin "1") (pinfunction "IN_1") (pintype "input"))
    )
    (net (code "90") (name "IN_IO") (class "Default")
      (node (ref "C3") (pin "1") (pinfunction "1_1") (pintype "passive"))
      (node (ref "IN_IO_3V3") (pin "2") (pinfunction "2_2") (pintype "passive"))
      (node (ref "U2") (pin "1") (pinfunction "IN_1") (pintype "input"))
    )
    (net (code "91") (name "I_PROG_COPI") (class "Default")
      (node (ref "SPI_OPEN8_2") (pin "3") (pinfunction "3_3") (pintype "passive"))
      (node (ref "U$3") (pin "12") (pinfunction "12_12") (pintype "bidirectional"))
    )
    (net (code "92") (name "I_PROG_CS") (class "Default")
      (node (ref "SPI_OPEN8_2") (pin "4") (pinfunction "4_4") (pintype "passive"))
      (node (ref "U$3") (pin "10") (pinfunction "10_10") (pintype "bidirectional"))
    )
    (net (code "93") (name "I_PROG_SCK") (class "Default")
      (node (ref "SPI_OPEN8_2") (pin "1") (pinfunction "1_1") (pintype "passive"))
      (node (ref "U$3") (pin "11") (pinfunction "11_11") (pintype "bidirectional"))
    )
    (net (code "94") (name "I_SPIFLASH_CIPO") (class "Default")
      (node (ref "FLASH_OPEN8") (pin "8") (pinfunction "8_8") (pintype "passive"))
      (node (ref "U$2") (pin "15") (pinfunction "15_15") (pintype "bidirectional"))
    )
    (net (code "95") (name "I_SPI_CIPO") (class "Default")
      (node (ref "LORA_OPEN8") (pin "P$3") (pinfunction "MOSI_P$3") (pintype "bidirectional"))
      (node (ref "U$2") (pin "26") (pinfunction "26_26") (pintype "bidirectional"))
    )
    (net (code "96") (name "I_TCK") (class "Default")
      (node (ref "JTAG_OPEN8") (pin "9") (pinfunction "9_9") (pintype "passive"))
      (node (ref "U$3") (pin "7") (pinfunction "7_7") (pintype "bidirectional"))
    )
    (net (code "97") (name "I_TDI") (class "Default")
      (node (ref "JTAG_OPEN8") (pin "5") (pinfunction "5_5") (pintype "passive"))
      (node (ref "U$3") (pin "8") (pinfunction "8_8") (pintype "bidirectional"))
    )
    (net (code "98") (name "I_TMS") (class "Default")
      (node (ref "JTAG_OPEN8") (pin "7") (pinfunction "7_7") (pintype "passive"))
      (node (ref "U$3") (pin "6") (pinfunction "6_6") (pintype "bidirectional"))
    )
    (net (code "99") (name "I_TRST") (class "Default")
      (node (ref "JTAG_OPEN8") (pin "3") (pinfunction "3_3") (pintype "passive"))
      (node (ref "U$2") (pin "27") (pinfunction "27_27") (pintype "bidirectional"))
    )
    (net (code "100") (name "LEDS_0") (class "Default")
      (node (ref "LEDS_OPEN8") (pin "1") (pinfunction "1_1") (pintype "passive"))
      (node (ref "U$3") (pin "33") (pinfunction "33_33") (pintype "bidirectional"))
    )
    (net (code "101") (name "LEDS_1") (class "Default")
      (node (ref "LEDS_OPEN8") (pin "3") (pinfunction "3_3") (pintype "passive"))
      (node (ref "U$3") (pin "34") (pinfunction "34_34") (pintype "bidirectional"))
    )
    (net (code "102") (name "LEDS_2") (class "Default")
      (node (ref "LEDS_OPEN8") (pin "5") (pinfunction "5_5") (pintype "passive"))
      (node (ref "U$3") (pin "31") (pinfunction "31_31") (pintype "bidirectional"))
    )
    (net (code "103") (name "LEDS_3") (class "Default")
      (node (ref "LEDS_OPEN8") (pin "7") (pinfunction "7_7") (pintype "passive"))
      (node (ref "U$3") (pin "32") (pinfunction "32_32") (pintype "bidirectional"))
    )
    (net (code "104") (name "LEDS_4") (class "Default")
      (node (ref "LEDS_OPEN8") (pin "9") (pinfunction "9_9") (pintype "passive"))
      (node (ref "U$3") (pin "29") (pinfunction "29_29") (pintype "bidirectional"))
    )
    (net (code "105") (name "LEDS_5") (class "Default")
      (node (ref "LEDS_OPEN8") (pin "11") (pinfunction "11_11") (pintype "passive"))
      (node (ref "U$3") (pin "30") (pinfunction "30_30") (pintype "bidirectional"))
    )
    (net (code "106") (name "LEDS_6") (class "Default")
      (node (ref "LEDS_OPEN8") (pin "13") (pinfunction "13_13") (pintype "passive"))
      (node (ref "U$3") (pin "27") (pinfunction "27_27") (pintype "bidirectional"))
    )
    (net (code "107") (name "LEDS_7") (class "Default")
      (node (ref "LEDS_OPEN8") (pin "15") (pinfunction "15_15") (pintype "passive"))
      (node (ref "U$3") (pin "28") (pinfunction "28_28") (pintype "bidirectional"))
    )
    (net (code "108") (name "LEDS_SERV_0") (class "Default")
      (node (ref "LEDS_SERV") (pin "1") (pinfunction "1_1") (pintype "passive"))
      (node (ref "U$1") (pin "34") (pinfunction "34_34") (pintype "bidirectional"))
    )
    (net (code "109") (name "LEDS_SERV_1") (class "Default")
      (node (ref "LEDS_SERV") (pin "3") (pinfunction "3_3") (pintype "passive"))
      (node (ref "U$1") (pin "31") (pinfunction "31_31") (pintype "bidirectional"))
    )
    (net (code "110") (name "LEDS_SERV_2") (class "Default")
      (node (ref "LEDS_SERV") (pin "5") (pinfunction "5_5") (pintype "passive"))
      (node (ref "U$1") (pin "32") (pinfunction "32_32") (pintype "bidirectional"))
    )
    (net (code "111") (name "LEDS_SERV_3") (class "Default")
      (node (ref "LEDS_SERV") (pin "7") (pinfunction "7_7") (pintype "passive"))
      (node (ref "U$1") (pin "29") (pinfunction "29_29") (pintype "bidirectional"))
    )
    (net (code "112") (name "LEDS_SERV_4") (class "Default")
      (node (ref "LEDS_SERV") (pin "9") (pinfunction "9_9") (pintype "passive"))
      (node (ref "U$1") (pin "30") (pinfunction "30_30") (pintype "bidirectional"))
    )
    (net (code "113") (name "LEDS_SERV_5") (class "Default")
      (node (ref "LEDS_SERV") (pin "11") (pinfunction "11_11") (pintype "passive"))
      (node (ref "U$1") (pin "27") (pinfunction "27_27") (pintype "bidirectional"))
    )
    (net (code "114") (name "LEDS_SERV_6") (class "Default")
      (node (ref "LEDS_SERV") (pin "13") (pinfunction "13_13") (pintype "passive"))
      (node (ref "U$1") (pin "28") (pinfunction "28_28") (pintype "bidirectional"))
    )
    (net (code "115") (name "LEDS_SERV_7") (class "Default")
      (node (ref "LEDS_SERV") (pin "15") (pinfunction "15_15") (pintype "passive"))
      (node (ref "U$1") (pin "25") (pinfunction "25_25") (pintype "bidirectional"))
    )
    (net (code "116") (name "NRESET") (class "Default")
      (node (ref "NRESET") (pin "1") (pinfunction "1_1") (pintype "passive"))
      (node (ref "U$3") (pin "38") (pinfunction "38_38") (pintype "bidirectional"))
    )
    (net (code "117") (name "NRESET_SERV") (class "Default")
      (node (ref "NRESET_SERV") (pin "1") (pinfunction "1_1") (pintype "passive"))
      (node (ref "U$1") (pin "35") (pinfunction "35_35") (pintype "bidirectional"))
    )
    (net (code "118") (name "Net-(C2-Pad2)") (class "Default")
      (node (ref "C2") (pin "2") (pinfunction "2_2") (pintype "passive"))
      (node (ref "R2") (pin "2") (pinfunction "2_2") (pintype "passive"))
    )
    (net (code "119") (name "Net-(C4-Pad2)") (class "Default")
      (node (ref "C4") (pin "2") (pinfunction "2_2") (pintype "passive"))
      (node (ref "R8") (pin "2") (pinfunction "2_2") (pintype "passive"))
    )
    (net (code "120") (name "Net-(C7-Pad2)") (class "Default")
      (node (ref "C7") (pin "2") (pinfunction "2_2") (pintype "passive"))
      (node (ref "R17") (pin "2") (pinfunction "2_2") (pintype "passive"))
    )
    (net (code "121") (name "Net-(C8-Pad2)") (class "Default")
      (node (ref "C8") (pin "2") (pinfunction "2_2") (pintype "passive"))
      (node (ref "R14") (pin "2") (pinfunction "2_2") (pintype "passive"))
    )
    (net (code "122") (name "Net-(D1-PadA)") (class "Default")
      (node (ref "D1") (pin "A") (pinfunction "A_A") (pintype "passive"))
      (node (ref "R30") (pin "1") (pinfunction "1_1") (pintype "passive"))
    )
    (net (code "123") (name "Net-(D2-PadA)") (class "Default")
      (node (ref "D2") (pin "A") (pinfunction "A_A") (pintype "passive"))
      (node (ref "R31") (pin "1") (pinfunction "1_1") (pintype "passive"))
    )
    (net (code "124") (name "Net-(D3-PadA)") (class "Default")
      (node (ref "D3") (pin "A") (pinfunction "A_A") (pintype "passive"))
      (node (ref "R32") (pin "1") (pinfunction "1_1") (pintype "passive"))
    )
    (net (code "125") (name "Net-(D4-PadA)") (class "Default")
      (node (ref "D4") (pin "A") (pinfunction "A_A") (pintype "passive"))
      (node (ref "R40") (pin "1") (pinfunction "1_1") (pintype "passive"))
    )
    (net (code "126") (name "Net-(D5-PadA)") (class "Default")
      (node (ref "D5") (pin "A") (pinfunction "A_A") (pintype "passive"))
      (node (ref "R41") (pin "1") (pinfunction "1_1") (pintype "passive"))
    )
    (net (code "127") (name "Net-(D6-PadA)") (class "Default")
      (node (ref "D6") (pin "A") (pinfunction "A_A") (pintype "passive"))
      (node (ref "R42") (pin "1") (pinfunction "1_1") (pintype "passive"))
    )
    (net (code "128") (name "Net-(D7-PadA)") (class "Default")
      (node (ref "D7") (pin "A") (pinfunction "A_A") (pintype "passive"))
      (node (ref "R43") (pin "1") (pinfunction "1_1") (pintype "passive"))
    )
    (net (code "129") (name "Net-(D8-PadA)") (class "Default")
      (node (ref "D8") (pin "A") (pinfunction "A_A") (pintype "passive"))
      (node (ref "R44") (pin "1") (pinfunction "1_1") (pintype "passive"))
    )
    (net (code "130") (name "Net-(D9-PadA)") (class "Default")
      (node (ref "D9") (pin "A") (pinfunction "A_A") (pintype "passive"))
      (node (ref "R45") (pin "1") (pinfunction "1_1") (pintype "passive"))
    )
    (net (code "131") (name "Net-(D10-PadA)") (class "Default")
      (node (ref "D10") (pin "A") (pinfunction "A_A") (pintype "passive"))
      (node (ref "R46") (pin "1") (pinfunction "1_1") (pintype "passive"))
    )
    (net (code "132") (name "Net-(D11-PadA)") (class "Default")
      (node (ref "D11") (pin "A") (pinfunction "A_A") (pintype "passive"))
      (node (ref "R47") (pin "1") (pinfunction "1_1") (pintype "passive"))
    )
    (net (code "133") (name "Net-(D12-PadA)") (class "Default")
      (node (ref "D12") (pin "A") (pinfunction "A_A") (pintype "passive"))
      (node (ref "R88") (pin "1") (pinfunction "1_1") (pintype "passive"))
    )
    (net (code "134") (name "Net-(D16-PadA)") (class "Default")
      (node (ref "D16") (pin "A") (pinfunction "A_A") (pintype "passive"))
      (node (ref "R33") (pin "1") (pinfunction "1_1") (pintype "passive"))
    )
    (net (code "135") (name "Net-(D17-PadA)") (class "Default")
      (node (ref "D17") (pin "A") (pinfunction "A_A") (pintype "passive"))
      (node (ref "R34") (pin "1") (pinfunction "1_1") (pintype "passive"))
    )
    (net (code "136") (name "Net-(D18-PadA)") (class "Default")
      (node (ref "D18") (pin "A") (pinfunction "A_A") (pintype "passive"))
      (node (ref "R35") (pin "1") (pinfunction "1_1") (pintype "passive"))
    )
    (net (code "137") (name "Net-(D19-PadA)") (class "Default")
      (node (ref "D19") (pin "A") (pinfunction "A_A") (pintype "passive"))
      (node (ref "R62") (pin "1") (pinfunction "1_1") (pintype "passive"))
    )
    (net (code "138") (name "Net-(D20-PadA)") (class "Default")
      (node (ref "D20") (pin "A") (pinfunction "A_A") (pintype "passive"))
      (node (ref "R64") (pin "1") (pinfunction "1_1") (pintype "passive"))
    )
    (net (code "139") (name "Net-(D21-PadA)") (class "Default")
      (node (ref "D21") (pin "A") (pinfunction "A_A") (pintype "passive"))
      (node (ref "R77") (pin "1") (pinfunction "1_1") (pintype "passive"))
    )
    (net (code "140") (name "Net-(D22-PadA)") (class "Default")
      (node (ref "D22") (pin "A") (pinfunction "A_A") (pintype "passive"))
      (node (ref "R79") (pin "1") (pinfunction "1_1") (pintype "passive"))
    )
    (net (code "141") (name "Net-(D27-PadA)") (class "Default")
      (node (ref "D27") (pin "A") (pinfunction "A_A") (pintype "passive"))
      (node (ref "R36") (pin "1") (pinfunction "1_1") (pintype "passive"))
    )
    (net (code "142") (name "Net-(D28-PadA)") (class "Default")
      (node (ref "D28") (pin "A") (pinfunction "A_A") (pintype "passive"))
      (node (ref "R37") (pin "1") (pinfunction "1_1") (pintype "passive"))
    )
    (net (code "143") (name "Net-(IC1-A)") (class "Default")
      (node (ref "C9") (pin "1") (pinfunction "1_1") (pintype "passive"))
      (node (ref "IC1") (pin "2") (pinfunction "A_2") (pintype "bidirectional"))
      (node (ref "R4") (pin "1") (pinfunction "1_1") (pintype "passive"))
      (node (ref "Y2") (pin "2") (pinfunction "CRYSTAL_2_2") (pintype "bidirectional"))
    )
    (net (code "144") (name "Net-(IC1-GND)") (class "Default")
      (node (ref "IC1") (pin "3") (pinfunction "GND_3") (pintype "power_in"))
      (node (ref "R6") (pin "2") (pinfunction "2_2") (pintype "passive"))
    )
    (net (code "145") (name "Net-(IC1-VCC)") (class "Default")
      (node (ref "IC1") (pin "5") (pinfunction "VCC_5") (pintype "power_in"))
      (node (ref "R5") (pin "1") (pinfunction "1_1") (pintype "passive"))
    )
    (net (code "146") (name "Net-(IC2-A)") (class "Default")
      (node (ref "C11") (pin "1") (pinfunction "1_1") (pintype "passive"))
      (node (ref "IC2") (pin "2") (pinfunction "A_2") (pintype "bidirectional"))
      (node (ref "R20") (pin "1") (pinfunction "1_1") (pintype "passive"))
      (node (ref "Y3") (pin "2") (pinfunction "CRYSTAL_2_2") (pintype "bidirectional"))
    )
    (net (code "147") (name "Net-(IC2-GND)") (class "Default")
      (node (ref "IC2") (pin "3") (pinfunction "GND_3") (pintype "power_in"))
      (node (ref "R28") (pin "2") (pinfunction "2_2") (pintype "passive"))
    )
    (net (code "148") (name "Net-(IC2-VCC)") (class "Default")
      (node (ref "IC2") (pin "5") (pinfunction "VCC_5") (pintype "power_in"))
      (node (ref "R21") (pin "1") (pinfunction "1_1") (pintype "passive"))
    )
    (net (code "149") (name "Net-(Q1-D)") (class "Default")
      (node (ref "D1") (pin "C") (pinfunction "C_C") (pintype "passive"))
      (node (ref "Q1") (pin "3") (pinfunction "D_3") (pintype "bidirectional"))
    )
    (net (code "150") (name "Net-(Q2-D)") (class "Default")
      (node (ref "D2") (pin "C") (pinfunction "C_C") (pintype "passive"))
      (node (ref "Q2") (pin "3") (pinfunction "D_3") (pintype "bidirectional"))
    )
    (net (code "151") (name "Net-(Q3-D)") (class "Default")
      (node (ref "D4") (pin "C") (pinfunction "C_C") (pintype "passive"))
      (node (ref "Q3") (pin "3") (pinfunction "D_3") (pintype "bidirectional"))
    )
    (net (code "152") (name "Net-(Q4-D)") (class "Default")
      (node (ref "D5") (pin "C") (pinfunction "C_C") (pintype "passive"))
      (node (ref "Q4") (pin "3") (pinfunction "D_3") (pintype "bidirectional"))
    )
    (net (code "153") (name "Net-(Q5-D)") (class "Default")
      (node (ref "D6") (pin "C") (pinfunction "C_C") (pintype "passive"))
      (node (ref "Q5") (pin "3") (pinfunction "D_3") (pintype "bidirectional"))
    )
    (net (code "154") (name "Net-(Q6-D)") (class "Default")
      (node (ref "D7") (pin "C") (pinfunction "C_C") (pintype "passive"))
      (node (ref "Q6") (pin "3") (pinfunction "D_3") (pintype "bidirectional"))
    )
    (net (code "155") (name "Net-(Q7-D)") (class "Default")
      (node (ref "D8") (pin "C") (pinfunction "C_C") (pintype "passive"))
      (node (ref "Q7") (pin "3") (pinfunction "D_3") (pintype "bidirectional"))
    )
    (net (code "156") (name "Net-(Q8-D)") (class "Default")
      (node (ref "D9") (pin "C") (pinfunction "C_C") (pintype "passive"))
      (node (ref "Q8") (pin "3") (pinfunction "D_3") (pintype "bidirectional"))
    )
    (net (code "157") (name "Net-(Q9-D)") (class "Default")
      (node (ref "D10") (pin "C") (pinfunction "C_C") (pintype "passive"))
      (node (ref "Q9") (pin "3") (pinfunction "D_3") (pintype "bidirectional"))
    )
    (net (code "158") (name "Net-(Q10-D)") (class "Default")
      (node (ref "D11") (pin "C") (pinfunction "C_C") (pintype "passive"))
      (node (ref "Q10") (pin "3") (pinfunction "D_3") (pintype "bidirectional"))
    )
    (net (code "159") (name "Net-(Q11-D)") (class "Default")
      (node (ref "D12") (pin "C") (pinfunction "C_C") (pintype "passive"))
      (node (ref "Q11") (pin "3") (pinfunction "D_3") (pintype "bidirectional"))
    )
    (net (code "160") (name "Net-(Q14-D)") (class "Default")
      (node (ref "D3") (pin "C") (pinfunction "C_C") (pintype "passive"))
      (node (ref "Q14") (pin "3") (pinfunction "D_3") (pintype "bidirectional"))
    )
    (net (code "161") (name "Net-(Q15-D)") (class "Default")
      (node (ref "D16") (pin "C") (pinfunction "C_C") (pintype "passive"))
      (node (ref "Q15") (pin "3") (pinfunction "D_3") (pintype "bidirectional"))
    )
    (net (code "162") (name "Net-(Q16-D)") (class "Default")
      (node (ref "D19") (pin "C") (pinfunction "C_C") (pintype "passive"))
      (node (ref "Q16") (pin "3") (pinfunction "D_3") (pintype "bidirectional"))
    )
    (net (code "163") (name "Net-(Q17-D)") (class "Default")
      (node (ref "D20") (pin "C") (pinfunction "C_C") (pintype "passive"))
      (node (ref "Q17") (pin "3") (pinfunction "D_3") (pintype "bidirectional"))
    )
    (net (code "164") (name "Net-(Q18-D)") (class "Default")
      (node (ref "D21") (pin "C") (pinfunction "C_C") (pintype "passive"))
      (node (ref "Q18") (pin "3") (pinfunction "D_3") (pintype "bidirectional"))
    )
    (net (code "165") (name "Net-(Q19-D)") (class "Default")
      (node (ref "D22") (pin "C") (pinfunction "C_C") (pintype "passive"))
      (node (ref "Q19") (pin "3") (pinfunction "D_3") (pintype "bidirectional"))
    )
    (net (code "166") (name "Net-(Q25-D)") (class "Default")
      (node (ref "D17") (pin "C") (pinfunction "C_C") (pintype "passive"))
      (node (ref "Q25") (pin "3") (pinfunction "D_3") (pintype "bidirectional"))
    )
    (net (code "167") (name "Net-(Q26-D)") (class "Default")
      (node (ref "D18") (pin "C") (pinfunction "C_C") (pintype "passive"))
      (node (ref "Q26") (pin "3") (pinfunction "D_3") (pintype "bidirectional"))
    )
    (net (code "168") (name "Net-(Q27-D)") (class "Default")
      (node (ref "D27") (pin "C") (pinfunction "C_C") (pintype "passive"))
      (node (ref "Q27") (pin "3") (pinfunction "D_3") (pintype "bidirectional"))
    )
    (net (code "169") (name "Net-(Q28-D)") (class "Default")
      (node (ref "D28") (pin "C") (pinfunction "C_C") (pintype "passive"))
      (node (ref "Q28") (pin "3") (pinfunction "D_3") (pintype "bidirectional"))
    )
    (net (code "170") (name "Net-(R10-Pad2)") (class "Default")
      (node (ref "R10") (pin "2") (pinfunction "2_2") (pintype "passive"))
      (node (ref "R9") (pin "1") (pinfunction "1_1") (pintype "passive"))
    )
    (net (code "171") (name "Net-(S1-COM)") (class "Default")
      (node (ref "S1") (pin "2") (pinfunction "COM_2") (pintype "bidirectional"))
      (node (ref "SWITCH_SERV") (pin "2") (pinfunction "2_2") (pintype "passive"))
    )
    (net (code "172") (name "Net-(S1-ON_1)") (class "Default")
      (node (ref "R11") (pin "1") (pinfunction "1_1") (pintype "passive"))
      (node (ref "S1") (pin "1") (pinfunction "ON_1_1") (pintype "bidirectional"))
    )
    (net (code "173") (name "Net-(S2-COM)") (class "Default")
      (node (ref "S2") (pin "2") (pinfunction "COM_2") (pintype "bidirectional"))
      (node (ref "SWITCH_SERV") (pin "4") (pinfunction "4_4") (pintype "passive"))
    )
    (net (code "174") (name "Net-(S2-ON_1)") (class "Default")
      (node (ref "R12") (pin "1") (pinfunction "1_1") (pintype "passive"))
      (node (ref "S2") (pin "1") (pinfunction "ON_1_1") (pintype "bidirectional"))
    )
    (net (code "175") (name "Net-(S3-COM)") (class "Default")
      (node (ref "S3") (pin "2") (pinfunction "COM_2") (pintype "bidirectional"))
      (node (ref "SWITCH_SERV") (pin "6") (pinfunction "6_6") (pintype "passive"))
    )
    (net (code "176") (name "Net-(S3-ON_1)") (class "Default")
      (node (ref "R22") (pin "1") (pinfunction "1_1") (pintype "passive"))
      (node (ref "S3") (pin "1") (pinfunction "ON_1_1") (pintype "bidirectional"))
    )
    (net (code "177") (name "Net-(S4-COM)") (class "Default")
      (node (ref "S4") (pin "2") (pinfunction "COM_2") (pintype "bidirectional"))
      (node (ref "SWITCH_SERV") (pin "8") (pinfunction "8_8") (pintype "passive"))
    )
    (net (code "178") (name "Net-(S4-ON_1)") (class "Default")
      (node (ref "R23") (pin "1") (pinfunction "1_1") (pintype "passive"))
      (node (ref "S4") (pin "1") (pinfunction "ON_1_1") (pintype "bidirectional"))
    )
    (net (code "179") (name "Net-(S5-COM)") (class "Default")
      (node (ref "S5") (pin "2") (pinfunction "COM_2") (pintype "bidirectional"))
      (node (ref "SWITCH_SERV") (pin "10") (pinfunction "10_10") (pintype "passive"))
    )
    (net (code "180") (name "Net-(S5-ON_1)") (class "Default")
      (node (ref "R24") (pin "1") (pinfunction "1_1") (pintype "passive"))
      (node (ref "S5") (pin "1") (pinfunction "ON_1_1") (pintype "bidirectional"))
    )
    (net (code "181") (name "Net-(S6-COM)") (class "Default")
      (node (ref "S6") (pin "2") (pinfunction "COM_2") (pintype "bidirectional"))
      (node (ref "SWITCH_SERV") (pin "12") (pinfunction "12_12") (pintype "passive"))
    )
    (net (code "182") (name "Net-(S6-ON_1)") (class "Default")
      (node (ref "R25") (pin "1") (pinfunction "1_1") (pintype "passive"))
      (node (ref "S6") (pin "1") (pinfunction "ON_1_1") (pintype "bidirectional"))
    )
    (net (code "183") (name "Net-(S7-COM)") (class "Default")
      (node (ref "S7") (pin "2") (pinfunction "COM_2") (pintype "bidirectional"))
      (node (ref "SWITCH_SERV") (pin "14") (pinfunction "14_14") (pintype "passive"))
    )
    (net (code "184") (name "Net-(S7-ON_1)") (class "Default")
      (node (ref "R26") (pin "1") (pinfunction "1_1") (pintype "passive"))
      (node (ref "S7") (pin "1") (pinfunction "ON_1_1") (pintype "bidirectional"))
    )
    (net (code "185") (name "Net-(S8-COM)") (class "Default")
      (node (ref "S8") (pin "2") (pinfunction "COM_2") (pintype "bidirectional"))
      (node (ref "SWITCH_SERV") (pin "16") (pinfunction "16_16") (pintype "passive"))
    )
    (net (code "186") (name "Net-(S8-ON_1)") (class "Default")
      (node (ref "R27") (pin "1") (pinfunction "1_1") (pintype "passive"))
      (node (ref "S8") (pin "1") (pinfunction "ON_1_1") (pintype "bidirectional"))
    )
    (net (code "187") (name "Net-(S9-COM)") (class "Default")
      (node (ref "S9") (pin "2") (pinfunction "COM_2") (pintype "bidirectional"))
      (node (ref "SWITCH_OPEN8") (pin "2") (pinfunction "2_2") (pintype "passive"))
    )
    (net (code "188") (name "Net-(S9-ON_1)") (class "Default")
      (node (ref "R66") (pin "1") (pinfunction "1_1") (pintype "passive"))
      (node (ref "S9") (pin "1") (pinfunction "ON_1_1") (pintype "bidirectional"))
    )
    (net (code "189") (name "Net-(S10-COM)") (class "Default")
      (node (ref "S10") (pin "2") (pinfunction "COM_2") (pintype "bidirectional"))
      (node (ref "SWITCH_OPEN8") (pin "4") (pinfunction "4_4") (pintype "passive"))
    )
    (net (code "190") (name "Net-(S10-ON_1)") (class "Default")
      (node (ref "R67") (pin "1") (pinfunction "1_1") (pintype "passive"))
      (node (ref "S10") (pin "1") (pinfunction "ON_1_1") (pintype "bidirectional"))
    )
    (net (code "191") (name "Net-(S11-COM)") (class "Default")
      (node (ref "S11") (pin "2") (pinfunction "COM_2") (pintype "bidirectional"))
      (node (ref "SWITCH_OPEN8") (pin "6") (pinfunction "6_6") (pintype "passive"))
    )
    (net (code "192") (name "Net-(S11-ON_1)") (class "Default")
      (node (ref "R68") (pin "1") (pinfunction "1_1") (pintype "passive"))
      (node (ref "S11") (pin "1") (pinfunction "ON_1_1") (pintype "bidirectional"))
    )
    (net (code "193") (name "Net-(S12-COM)") (class "Default")
      (node (ref "S12") (pin "2") (pinfunction "COM_2") (pintype "bidirectional"))
      (node (ref "SWITCH_OPEN8") (pin "8") (pinfunction "8_8") (pintype "passive"))
    )
    (net (code "194") (name "Net-(S12-ON_1)") (class "Default")
      (node (ref "R69") (pin "1") (pinfunction "1_1") (pintype "passive"))
      (node (ref "S12") (pin "1") (pinfunction "ON_1_1") (pintype "bidirectional"))
    )
    (net (code "195") (name "Net-(S13-COM)") (class "Default")
      (node (ref "S13") (pin "2") (pinfunction "COM_2") (pintype "bidirectional"))
      (node (ref "SWITCH_OPEN8") (pin "10") (pinfunction "10_10") (pintype "passive"))
    )
    (net (code "196") (name "Net-(S13-ON_1)") (class "Default")
      (node (ref "R70") (pin "1") (pinfunction "1_1") (pintype "passive"))
      (node (ref "S13") (pin "1") (pinfunction "ON_1_1") (pintype "bidirectional"))
    )
    (net (code "197") (name "Net-(S14-COM)") (class "Default")
      (node (ref "S14") (pin "2") (pinfunction "COM_2") (pintype "bidirectional"))
      (node (ref "SWITCH_OPEN8") (pin "12") (pinfunction "12_12") (pintype "passive"))
    )
    (net (code "198") (name "Net-(S14-ON_1)") (class "Default")
      (node (ref "R71") (pin "1") (pinfunction "1_1") (pintype "passive"))
      (node (ref "S14") (pin "1") (pinfunction "ON_1_1") (pintype "bidirectional"))
    )
    (net (code "199") (name "Net-(S15-COM)") (class "Default")
      (node (ref "S15") (pin "2") (pinfunction "COM_2") (pintype "bidirectional"))
      (node (ref "SWITCH_OPEN8") (pin "14") (pinfunction "14_14") (pintype "passive"))
    )
    (net (code "200") (name "Net-(S15-ON_1)") (class "Default")
      (node (ref "R89") (pin "1") (pinfunction "1_1") (pintype "passive"))
      (node (ref "S15") (pin "1") (pinfunction "ON_1_1") (pintype "bidirectional"))
    )
    (net (code "201") (name "Net-(S16-COM)") (class "Default")
      (node (ref "S16") (pin "2") (pinfunction "COM_2") (pintype "bidirectional"))
      (node (ref "SWITCH_OPEN8") (pin "16") (pinfunction "16_16") (pintype "passive"))
    )
    (net (code "202") (name "Net-(S16-ON_1)") (class "Default")
      (node (ref "R90") (pin "1") (pinfunction "1_1") (pintype "passive"))
      (node (ref "S16") (pin "1") (pinfunction "ON_1_1") (pintype "bidirectional"))
    )
    (net (code "203") (name "Net-(S19-COM)") (class "Default")
      (node (ref "NRESET") (pin "2") (pinfunction "2_2") (pintype "passive"))
      (node (ref "S19") (pin "2") (pinfunction "COM_2") (pintype "bidirectional"))
    )
    (net (code "204") (name "Net-(S19-ON_1)") (class "Default")
      (node (ref "R81") (pin "1") (pinfunction "1_1") (pintype "passive"))
      (node (ref "S19") (pin "1") (pinfunction "ON_1_1") (pintype "bidirectional"))
    )
    (net (code "205") (name "Net-(S20-COM)") (class "Default")
      (node (ref "NRESET_SERV") (pin "2") (pinfunction "2_2") (pintype "passive"))
      (node (ref "S20") (pin "2") (pinfunction "COM_2") (pintype "bidirectional"))
    )
    (net (code "206") (name "Net-(S20-ON_1)") (class "Default")
      (node (ref "R82") (pin "1") (pinfunction "1_1") (pintype "passive"))
      (node (ref "S20") (pin "1") (pinfunction "ON_1_1") (pintype "bidirectional"))
    )
    (net (code "207") (name "Net-(U1-FB)") (class "Default")
      (node (ref "R1") (pin "2") (pinfunction "2_2") (pintype "passive"))
      (node (ref "R3") (pin "1") (pinfunction "1_1") (pintype "passive"))
      (node (ref "U1") (pin "4") (pinfunction "FB_4") (pintype "input"))
    )
    (net (code "208") (name "Net-(U2-FB)") (class "Default")
      (node (ref "R10") (pin "1") (pinfunction "1_1") (pintype "passive"))
      (node (ref "R7") (pin "2") (pinfunction "2_2") (pintype "passive"))
      (node (ref "U2") (pin "4") (pinfunction "FB_4") (pintype "input"))
    )
    (net (code "209") (name "Net-(U3-FB)") (class "Default")
      (node (ref "R13") (pin "2") (pinfunction "2_2") (pintype "passive"))
      (node (ref "R19") (pin "1") (pinfunction "1_1") (pintype "passive"))
      (node (ref "U3") (pin "4") (pinfunction "FB_4") (pintype "input"))
    )
    (net (code "210") (name "Net-(U4-FB)") (class "Default")
      (node (ref "R15") (pin "1") (pinfunction "1_1") (pintype "passive"))
      (node (ref "R16") (pin "2") (pinfunction "2_2") (pintype "passive"))
      (node (ref "U4") (pin "4") (pinfunction "FB_4") (pintype "input"))
    )
    (net (code "211") (name "Net-(Y2-CRYSTAL_1)") (class "Default")
      (node (ref "C10") (pin "2") (pinfunction "2_2") (pintype "passive"))
      (node (ref "R18") (pin "1") (pinfunction "1_1") (pintype "passive"))
      (node (ref "Y2") (pin "1") (pinfunction "CRYSTAL_1_1") (pintype "bidirectional"))
    )
    (net (code "212") (name "Net-(Y3-CRYSTAL_1)") (class "Default")
      (node (ref "C12") (pin "2") (pinfunction "2_2") (pintype "passive"))
      (node (ref "R29") (pin "1") (pinfunction "1_1") (pintype "passive"))
      (node (ref "Y3") (pin "1") (pinfunction "CRYSTAL_1_1") (pintype "bidirectional"))
    )
    (net (code "213") (name "OPEN8_OUT_0") (class "Default")
      (node (ref "LEDS_OPEN8") (pin "2") (pinfunction "2_2") (pintype "passive"))
      (node (ref "Q3") (pin "1") (pinfunction "G_1") (pintype "bidirectional"))
      (node (ref "R48") (pin "2") (pinfunction "2_2") (pintype "passive"))
    )
    (net (code "214") (name "OPEN8_OUT_1") (class "Default")
      (node (ref "LEDS_OPEN8") (pin "4") (pinfunction "4_4") (pintype "passive"))
      (node (ref "Q4") (pin "1") (pinfunction "G_1") (pintype "bidirectional"))
      (node (ref "R49") (pin "2") (pinfunction "2_2") (pintype "passive"))
    )
    (net (code "215") (name "OPEN8_OUT_2") (class "Default")
      (node (ref "LEDS_OPEN8") (pin "6") (pinfunction "6_6") (pintype "passive"))
      (node (ref "Q5") (pin "1") (pinfunction "G_1") (pintype "bidirectional"))
      (node (ref "R50") (pin "2") (pinfunction "2_2") (pintype "passive"))
    )
    (net (code "216") (name "OPEN8_OUT_3") (class "Default")
      (node (ref "LEDS_OPEN8") (pin "8") (pinfunction "8_8") (pintype "passive"))
      (node (ref "Q6") (pin "1") (pinfunction "G_1") (pintype "bidirectional"))
      (node (ref "R51") (pin "2") (pinfunction "2_2") (pintype "passive"))
    )
    (net (code "217") (name "OPEN8_OUT_4") (class "Default")
      (node (ref "LEDS_OPEN8") (pin "10") (pinfunction "10_10") (pintype "passive"))
      (node (ref "Q7") (pin "1") (pinfunction "G_1") (pintype "bidirectional"))
      (node (ref "R52") (pin "2") (pinfunction "2_2") (pintype "passive"))
    )
    (net (code "218") (name "OPEN8_OUT_5") (class "Default")
      (node (ref "LEDS_OPEN8") (pin "12") (pinfunction "12_12") (pintype "passive"))
      (node (ref "Q8") (pin "1") (pinfunction "G_1") (pintype "bidirectional"))
      (node (ref "R53") (pin "2") (pinfunction "2_2") (pintype "passive"))
    )
    (net (code "219") (name "OPEN8_OUT_6") (class "Default")
      (node (ref "LEDS_OPEN8") (pin "14") (pinfunction "14_14") (pintype "passive"))
      (node (ref "Q9") (pin "1") (pinfunction "G_1") (pintype "bidirectional"))
      (node (ref "R54") (pin "2") (pinfunction "2_2") (pintype "passive"))
    )
    (net (code "220") (name "OPEN8_OUT_7") (class "Default")
      (node (ref "LEDS_OPEN8") (pin "16") (pinfunction "16_16") (pintype "passive"))
      (node (ref "Q10") (pin "1") (pinfunction "G_1") (pintype "bidirectional"))
      (node (ref "R55") (pin "2") (pinfunction "2_2") (pintype "passive"))
    )
    (net (code "221") (name "OUT_12_OPEN8") (class "Default")
      (node (ref "C7") (pin "1") (pinfunction "1_1") (pintype "passive"))
      (node (ref "POWER") (pin "1") (pinfunction "1_1") (pintype "passive"))
      (node (ref "R15") (pin "2") (pinfunction "2_2") (pintype "passive"))
      (node (ref "U4") (pin "5") (pinfunction "OUT_5") (pintype "output"))
    )
    (net (code "222") (name "OUT_12_SERV") (class "Default")
      (node (ref "C2") (pin "1") (pinfunction "1_1") (pintype "passive"))
      (node (ref "POWER") (pin "3") (pinfunction "3_3") (pintype "passive"))
      (node (ref "R3") (pin "2") (pinfunction "2_2") (pintype "passive"))
      (node (ref "U1") (pin "5") (pinfunction "OUT_5") (pintype "output"))
    )
    (net (code "223") (name "OUT_12_VDD") (class "Default")
      (node (ref "C8") (pin "1") (pinfunction "1_1") (pintype "passive"))
      (node (ref "POWER") (pin "5") (pinfunction "5_5") (pintype "passive"))
      (node (ref "R19") (pin "2") (pinfunction "2_2") (pintype "passive"))
      (node (ref "U3") (pin "5") (pinfunction "OUT_5") (pintype "output"))
    )
    (net (code "224") (name "OUT_IO_3V3") (class "Default")
      (node (ref "C4") (pin "1") (pinfunction "1_1") (pintype "passive"))
      (node (ref "POWER") (pin "7") (pinfunction "7_7") (pintype "passive"))
      (node (ref "R9") (pin "2") (pinfunction "2_2") (pintype "passive"))
      (node (ref "U2") (pin "5") (pinfunction "OUT_5") (pintype "output"))
    )
    (net (code "225") (name "O_PROG_CIPO") (class "Default")
      (node (ref "SPI_OPEN8_2") (pin "2") (pinfunction "2_2") (pintype "passive"))
      (node (ref "U$3") (pin "9") (pinfunction "9_9") (pintype "bidirectional"))
    )
    (net (code "226") (name "O_SPIFLASH_COPI") (class "Default")
      (node (ref "FLASH_OPEN8") (pin "10") (pinfunction "10_10") (pintype "passive"))
      (node (ref "U$2") (pin "18") (pinfunction "18_18") (pintype "bidirectional"))
    )
    (net (code "227") (name "O_SPIFLASH_CS") (class "Default")
      (node (ref "FLASH_OPEN8") (pin "12") (pinfunction "12_12") (pintype "passive"))
      (node (ref "U$2") (pin "16") (pinfunction "16_16") (pintype "bidirectional"))
    )
    (net (code "228") (name "O_SPIFLASH_SCK") (class "Default")
      (node (ref "FLASH_OPEN8") (pin "6") (pinfunction "6_6") (pintype "passive"))
      (node (ref "U$2") (pin "17") (pinfunction "17_17") (pintype "bidirectional"))
    )
    (net (code "229") (name "O_SPI_COPI") (class "Default")
      (node (ref "LORA_OPEN8") (pin "P$2") (pinfunction "MISO_P$2") (pintype "bidirectional"))
      (node (ref "U$2") (pin "25") (pinfunction "25_25") (pintype "bidirectional"))
    )
    (net (code "230") (name "O_SPI_CS") (class "Default")
      (node (ref "LORA_OPEN8") (pin "P$5") (pinfunction "NSS_P$5") (pintype "bidirectional"))
      (node (ref "U$2") (pin "23") (pinfunction "23_23") (pintype "bidirectional"))
    )
    (net (code "231") (name "O_SPI_SCK") (class "Default")
      (node (ref "LORA_OPEN8") (pin "P$4") (pinfunction "SCK_P$4") (pintype "bidirectional"))
      (node (ref "U$2") (pin "28") (pinfunction "28_28") (pintype "bidirectional"))
    )
    (net (code "232") (name "O_TDO") (class "Default")
      (node (ref "JTAG_OPEN8") (pin "13") (pinfunction "13_13") (pintype "passive"))
      (node (ref "U$3") (pin "5") (pinfunction "5_5") (pintype "bidirectional"))
    )
    (net (code "233") (name "RX_IN") (class "Default")
      (node (ref "U$1") (pin "38") (pinfunction "38_38") (pintype "bidirectional"))
      (node (ref "USB-UART_OPEN8_1") (pin "2") (pinfunction "2_2") (pintype "passive"))
    )
    (net (code "234") (name "SERV_I_PROG_COPI") (class "Default")
      (node (ref "SPI_SERV_2") (pin "3") (pinfunction "3_3") (pintype "passive"))
      (node (ref "U$1") (pin "14") (pinfunction "14_14") (pintype "bidirectional"))
    )
    (net (code "235") (name "SERV_I_PROG_CS") (class "Default")
      (node (ref "SPI_SERV_2") (pin "4") (pinfunction "4_4") (pintype "passive"))
      (node (ref "U$1") (pin "12") (pinfunction "12_12") (pintype "bidirectional"))
    )
    (net (code "236") (name "SERV_I_PROG_SCK") (class "Default")
      (node (ref "SPI_SERV_2") (pin "1") (pinfunction "1_1") (pintype "passive"))
      (node (ref "U$1") (pin "13") (pinfunction "13_13") (pintype "bidirectional"))
    )
    (net (code "237") (name "SERV_I_SPIFLASH_CIPO") (class "Default")
      (node (ref "FLASH_SERV") (pin "8") (pinfunction "8_8") (pintype "passive"))
      (node (ref "U$4") (pin "26") (pinfunction "26_26") (pintype "bidirectional"))
    )
    (net (code "238") (name "SERV_I_SPI_CIPO") (class "Default")
      (node (ref "LORA_SERV") (pin "P$3") (pinfunction "MOSI_P$3") (pintype "bidirectional"))
      (node (ref "U$4") (pin "16") (pinfunction "16_16") (pintype "bidirectional"))
    )
    (net (code "239") (name "SERV_I_TCK") (class "Default")
      (node (ref "JTAG_SERV") (pin "9") (pinfunction "9_9") (pintype "passive"))
      (node (ref "U$1") (pin "9") (pinfunction "9_9") (pintype "bidirectional"))
    )
    (net (code "240") (name "SERV_I_TDI") (class "Default")
      (node (ref "JTAG_SERV") (pin "5") (pinfunction "5_5") (pintype "passive"))
      (node (ref "U$1") (pin "10") (pinfunction "10_10") (pintype "bidirectional"))
    )
    (net (code "241") (name "SERV_I_TMS") (class "Default")
      (node (ref "JTAG_SERV") (pin "7") (pinfunction "7_7") (pintype "passive"))
      (node (ref "U$1") (pin "8") (pinfunction "8_8") (pintype "bidirectional"))
    )
    (net (code "242") (name "SERV_I_TRST") (class "Default")
      (node (ref "JTAG_SERV") (pin "3") (pinfunction "3_3") (pintype "passive"))
      (node (ref "U$1") (pin "5") (pinfunction "5_5") (pintype "bidirectional"))
    )
    (net (code "243") (name "SERV_OUT_0") (class "Default")
      (node (ref "LEDS_SERV") (pin "2") (pinfunction "2_2") (pintype "passive"))
      (node (ref "Q1") (pin "1") (pinfunction "G_1") (pintype "bidirectional"))
      (node (ref "R38") (pin "2") (pinfunction "2_2") (pintype "passive"))
    )
    (net (code "244") (name "SERV_OUT_1") (class "Default")
      (node (ref "LEDS_SERV") (pin "4") (pinfunction "4_4") (pintype "passive"))
      (node (ref "Q2") (pin "1") (pinfunction "G_1") (pintype "bidirectional"))
      (node (ref "R39") (pin "2") (pinfunction "2_2") (pintype "passive"))
    )
    (net (code "245") (name "SERV_OUT_2") (class "Default")
      (node (ref "LEDS_SERV") (pin "6") (pinfunction "6_6") (pintype "passive"))
      (node (ref "Q14") (pin "1") (pinfunction "G_1") (pintype "bidirectional"))
      (node (ref "R56") (pin "2") (pinfunction "2_2") (pintype "passive"))
    )
    (net (code "246") (name "SERV_OUT_3") (class "Default")
      (node (ref "LEDS_SERV") (pin "8") (pinfunction "8_8") (pintype "passive"))
      (node (ref "Q15") (pin "1") (pinfunction "G_1") (pintype "bidirectional"))
      (node (ref "R57") (pin "2") (pinfunction "2_2") (pintype "passive"))
    )
    (net (code "247") (name "SERV_OUT_4") (class "Default")
      (node (ref "LEDS_SERV") (pin "10") (pinfunction "10_10") (pintype "passive"))
      (node (ref "Q25") (pin "1") (pinfunction "G_1") (pintype "bidirectional"))
      (node (ref "R58") (pin "2") (pinfunction "2_2") (pintype "passive"))
    )
    (net (code "248") (name "SERV_OUT_5") (class "Default")
      (node (ref "LEDS_SERV") (pin "12") (pinfunction "12_12") (pintype "passive"))
      (node (ref "Q26") (pin "1") (pinfunction "G_1") (pintype "bidirectional"))
      (node (ref "R59") (pin "2") (pinfunction "2_2") (pintype "passive"))
    )
    (net (code "249") (name "SERV_OUT_6") (class "Default")
      (node (ref "LEDS_SERV") (pin "14") (pinfunction "14_14") (pintype "passive"))
      (node (ref "Q27") (pin "1") (pinfunction "G_1") (pintype "bidirectional"))
      (node (ref "R60") (pin "2") (pinfunction "2_2") (pintype "passive"))
    )
    (net (code "250") (name "SERV_OUT_7") (class "Default")
      (node (ref "LEDS_SERV") (pin "16") (pinfunction "16_16") (pintype "passive"))
      (node (ref "Q28") (pin "1") (pinfunction "G_1") (pintype "bidirectional"))
      (node (ref "R61") (pin "2") (pinfunction "2_2") (pintype "passive"))
    )
    (net (code "251") (name "SERV_O_PROG_CIPO") (class "Default")
      (node (ref "SPI_SERV_2") (pin "2") (pinfunction "2_2") (pintype "passive"))
      (node (ref "U$1") (pin "11") (pinfunction "11_11") (pintype "bidirectional"))
    )
    (net (code "252") (name "SERV_O_SPIFLASH_COPI") (class "Default")
      (node (ref "FLASH_SERV") (pin "10") (pinfunction "10_10") (pintype "passive"))
      (node (ref "U$4") (pin "17") (pinfunction "17_17") (pintype "bidirectional"))
    )
    (net (code "253") (name "SERV_O_SPIFLASH_CS") (class "Default")
      (node (ref "FLASH_SERV") (pin "12") (pinfunction "12_12") (pintype "passive"))
      (node (ref "U$4") (pin "25") (pinfunction "25_25") (pintype "bidirectional"))
    )
    (net (code "254") (name "SERV_O_SPIFLASH_SCK") (class "Default")
      (node (ref "FLASH_SERV") (pin "6") (pinfunction "6_6") (pintype "passive"))
      (node (ref "U$4") (pin "18") (pinfunction "18_18") (pintype "bidirectional"))
    )
    (net (code "255") (name "SERV_O_SPI_COPI") (class "Default")
      (node (ref "LORA_SERV") (pin "P$2") (pinfunction "MISO_P$2") (pintype "bidirectional"))
      (node (ref "U$4") (pin "13") (pinfunction "13_13") (pintype "bidirectional"))
    )
    (net (code "256") (name "SERV_O_SPI_CS") (class "Default")
      (node (ref "LORA_SERV") (pin "P$5") (pinfunction "NSS_P$5") (pintype "bidirectional"))
      (node (ref "U$4") (pin "15") (pinfunction "15_15") (pintype "bidirectional"))
    )
    (net (code "257") (name "SERV_O_SPI_SCK") (class "Default")
      (node (ref "LORA_SERV") (pin "P$4") (pinfunction "SCK_P$4") (pintype "bidirectional"))
      (node (ref "U$1") (pin "6") (pinfunction "6_6") (pintype "bidirectional"))
    )
    (net (code "258") (name "SERV_O_TDO") (class "Default")
      (node (ref "JTAG_SERV") (pin "13") (pinfunction "13_13") (pintype "passive"))
      (node (ref "U$1") (pin "7") (pinfunction "7_7") (pintype "bidirectional"))
    )
    (net (code "259") (name "SERV_RX_IN") (class "Default")
      (node (ref "U$4") (pin "27") (pinfunction "27_27") (pintype "bidirectional"))
      (node (ref "USB-UART_SERV_1") (pin "2") (pinfunction "2_2") (pintype "passive"))
    )
    (net (code "260") (name "SERV_TX_OUT") (class "Default")
      (node (ref "U$4") (pin "28") (pinfunction "28_28") (pintype "bidirectional"))
      (node (ref "USB-UART_SERV_1") (pin "4") (pinfunction "4_4") (pintype "passive"))
    )
    (net (code "261") (name "SMA_CLK") (class "Default")
      (node (ref "CLOCK") (pin "5") (pinfunction "5_5") (pintype "passive"))
      (node (ref "J4") (pin "5") (pinfunction "5_5") (pintype "bidirectional"))
    )
    (net (code "262") (name "TX_OUT") (class "Default")
      (node (ref "U$2") (pin "13") (pinfunction "13_13") (pintype "bidirectional"))
      (node (ref "USB-UART_OPEN8_1") (pin "4") (pinfunction "4_4") (pintype "passive"))
    )
    (net (code "263") (name "VDD_3V3") (class "Default")
      (node (ref "C21") (pin "1") (pinfunction "1_1") (pintype "passive"))
      (node (ref "C22") (pin "1") (pinfunction "1_1") (pintype "passive"))
      (node (ref "FLASH_OPEN8") (pin "1") (pinfunction "1_1") (pintype "passive"))
      (node (ref "FLASH_OPEN8") (pin "2") (pinfunction "2_2") (pintype "passive"))
      (node (ref "FLASH_SERV") (pin "1") (pinfunction "1_1") (pintype "passive"))
      (node (ref "FLASH_SERV") (pin "2") (pinfunction "2_2") (pintype "passive"))
      (node (ref "JTAG_OPEN8") (pin "1") (pinfunction "1_1") (pintype "passive"))
      (node (ref "JTAG_OPEN8") (pin "2") (pinfunction "2_2") (pintype "passive"))
      (node (ref "JTAG_SERV") (pin "1") (pinfunction "1_1") (pintype "passive"))
      (node (ref "JTAG_SERV") (pin "2") (pinfunction "2_2") (pintype "passive"))
      (node (ref "LORA_OPEN8") (pin "P$12") (pinfunction "3.3V_P$12") (pintype "bidirectional"))
      (node (ref "LORA_SERV") (pin "P$12") (pinfunction "3.3V_P$12") (pintype "bidirectional"))
      (node (ref "POWER") (pin "8") (pinfunction "8_8") (pintype "passive"))
      (node (ref "Q16") (pin "1") (pinfunction "G_1") (pintype "bidirectional"))
      (node (ref "R11") (pin "2") (pinfunction "2_2") (pintype "passive"))
      (node (ref "R12") (pin "2") (pinfunction "2_2") (pintype "passive"))
      (node (ref "R21") (pin "2") (pinfunction "2_2") (pintype "passive"))
      (node (ref "R22") (pin "2") (pinfunction "2_2") (pintype "passive"))
      (node (ref "R23") (pin "2") (pinfunction "2_2") (pintype "passive"))
      (node (ref "R24") (pin "2") (pinfunction "2_2") (pintype "passive"))
      (node (ref "R25") (pin "2") (pinfunction "2_2") (pintype "passive"))
      (node (ref "R26") (pin "2") (pinfunction "2_2") (pintype "passive"))
      (node (ref "R27") (pin "2") (pinfunction "2_2") (pintype "passive"))
      (node (ref "R30") (pin "2") (pinfunction "2_2") (pintype "passive"))
      (node (ref "R31") (pin "2") (pinfunction "2_2") (pintype "passive"))
      (node (ref "R32") (pin "2") (pinfunction "2_2") (pintype "passive"))
      (node (ref "R33") (pin "2") (pinfunction "2_2") (pintype "passive"))
      (node (ref "R34") (pin "2") (pinfunction "2_2") (pintype "passive"))
      (node (ref "R35") (pin "2") (pinfunction "2_2") (pintype "passive"))
      (node (ref "R36") (pin "2") (pinfunction "2_2") (pintype "passive"))
      (node (ref "R37") (pin "2") (pinfunction "2_2") (pintype "passive"))
      (node (ref "R40") (pin "2") (pinfunction "2_2") (pintype "passive"))
      (node (ref "R41") (pin "2") (pinfunction "2_2") (pintype "passive"))
      (node (ref "R42") (pin "2") (pinfunction "2_2") (pintype "passive"))
      (node (ref "R43") (pin "2") (pinfunction "2_2") (pintype "passive"))
      (node (ref "R44") (pin "2") (pinfunction "2_2") (pintype "passive"))
      (node (ref "R45") (pin "2") (pinfunction "2_2") (pintype "passive"))
      (node (ref "R46") (pin "2") (pinfunction "2_2") (pintype "passive"))
      (node (ref "R47") (pin "2") (pinfunction "2_2") (pintype "passive"))
      (node (ref "R5") (pin "2") (pinfunction "2_2") (pintype "passive"))
      (node (ref "R62") (pin "2") (pinfunction "2_2") (pintype "passive"))
      (node (ref "R63") (pin "2") (pinfunction "2_2") (pintype "passive"))
      (node (ref "R64") (pin "2") (pinfunction "2_2") (pintype "passive"))
      (node (ref "R66") (pin "2") (pinfunction "2_2") (pintype "passive"))
      (node (ref "R67") (pin "2") (pinfunction "2_2") (pintype "passive"))
      (node (ref "R68") (pin "2") (pinfunction "2_2") (pintype "passive"))
      (node (ref "R69") (pin "2") (pinfunction "2_2") (pintype "passive"))
      (node (ref "R70") (pin "2") (pinfunction "2_2") (pintype "passive"))
      (node (ref "R71") (pin "2") (pinfunction "2_2") (pintype "passive"))
      (node (ref "R77") (pin "2") (pinfunction "2_2") (pintype "passive"))
      (node (ref "R79") (pin "2") (pinfunction "2_2") (pintype "passive"))
      (node (ref "R81") (pin "2") (pinfunction "2_2") (pintype "passive"))
      (node (ref "R82") (pin "2") (pinfunction "2_2") (pintype "passive"))
      (node (ref "R88") (pin "2") (pinfunction "2_2") (pintype "passive"))
      (node (ref "R89") (pin "2") (pinfunction "2_2") (pintype "passive"))
      (node (ref "R90") (pin "2") (pinfunction "2_2") (pintype "passive"))
      (node (ref "U$1") (pin "26") (pinfunction "26_26") (pintype "bidirectional"))
      (node (ref "U$2") (pin "24") (pinfunction "24_24") (pintype "bidirectional"))
      (node (ref "U$3") (pin "15") (pinfunction "15_15") (pintype "bidirectional"))
      (node (ref "U$3") (pin "18") (pinfunction "18_18") (pintype "bidirectional"))
      (node (ref "U$4") (pin "20") (pinfunction "20_20") (pintype "bidirectional"))
      (node (ref "USB-UART_OPEN8_1") (pin "3") (pinfunction "3_3") (pintype "passive"))
      (node (ref "USB-UART_SERV_1") (pin "3") (pinfunction "3_3") (pintype "passive"))
    )
    (net (code "264") (name "VDD_5V") (class "Default")
      (node (ref "IN_12_OPEN8") (pin "1") (pinfunction "1_1") (pintype "passive"))
      (node (ref "IN_12_SERV") (pin "1") (pinfunction "1_1") (pintype "passive"))
      (node (ref "IN_12_VDD") (pin "1") (pinfunction "1_1") (pintype "passive"))
      (node (ref "IN_IO_3V3") (pin "1") (pinfunction "1_1") (pintype "passive"))
      (node (ref "Q11") (pin "1") (pinfunction "G_1") (pintype "bidirectional"))
      (node (ref "R91") (pin "2") (pinfunction "2_2") (pintype "passive"))
      (node (ref "USB-UART_OPEN8_2") (pin "2") (pinfunction "2_2") (pintype "passive"))
      (node (ref "USB-UART_SERV_2") (pin "2") (pinfunction "2_2") (pintype "passive"))
    )
    (net (code "265") (name "VO_12_OPEN8") (class "Default")
      (node (ref "C14") (pin "1") (pinfunction "1_1") (pintype "passive"))
      (node (ref "C15") (pin "1") (pinfunction "1_1") (pintype "passive"))
      (node (ref "POWER") (pin "2") (pinfunction "2_2") (pintype "passive"))
      (node (ref "Q17") (pin "1") (pinfunction "G_1") (pintype "bidirectional"))
      (node (ref "R65") (pin "2") (pinfunction "2_2") (pintype "passive"))
      (node (ref "U$4") (pin "23") (pinfunction "23_23") (pintype "bidirectional"))
    )
    (net (code "266") (name "VO_12_SERV") (class "Default")
      (node (ref "C16") (pin "1") (pinfunction "1_1") (pintype "passive"))
      (node (ref "C17") (pin "1") (pinfunction "1_1") (pintype "passive"))
      (node (ref "POWER") (pin "4") (pinfunction "4_4") (pintype "passive"))
      (node (ref "Q18") (pin "1") (pinfunction "G_1") (pintype "bidirectional"))
      (node (ref "R78") (pin "2") (pinfunction "2_2") (pintype "passive"))
      (node (ref "U$2") (pin "19") (pinfunction "19_19") (pintype "bidirectional"))
    )
    (net (code "267") (name "VO_12_VDD") (class "Default")
      (node (ref "C19") (pin "1") (pinfunction "1_1") (pintype "passive"))
      (node (ref "C20") (pin "1") (pinfunction "1_1") (pintype "passive"))
      (node (ref "POWER") (pin "6") (pinfunction "6_6") (pintype "passive"))
      (node (ref "Q19") (pin "1") (pinfunction "G_1") (pintype "bidirectional"))
      (node (ref "R80") (pin "2") (pinfunction "2_2") (pintype "passive"))
      (node (ref "U$1") (pin "23") (pinfunction "23_23") (pintype "bidirectional"))
      (node (ref "U$2") (pin "21") (pinfunction "21_21") (pintype "bidirectional"))
      (node (ref "U$3") (pin "17") (pinfunction "17_17") (pintype "bidirectional"))
      (node (ref "U$3") (pin "20") (pinfunction "20_20") (pintype "bidirectional"))
      (node (ref "U$4") (pin "19") (pinfunction "19_19") (pintype "bidirectional"))
    )
    (net (code "268") (name "unconnected-(FLASH_OPEN8-Pad5)") (class "Default")
      (node (ref "FLASH_OPEN8") (pin "5") (pinfunction "5_5") (pintype "passive"))
    )
    (net (code "269") (name "unconnected-(FLASH_OPEN8-Pad7)") (class "Default")
      (node (ref "FLASH_OPEN8") (pin "7") (pinfunction "7_7") (pintype "passive"))
    )
    (net (code "270") (name "unconnected-(FLASH_OPEN8-Pad9)") (class "Default")
      (node (ref "FLASH_OPEN8") (pin "9") (pinfunction "9_9") (pintype "passive"))
    )
    (net (code "271") (name "unconnected-(FLASH_OPEN8-Pad11)") (class "Default")
      (node (ref "FLASH_OPEN8") (pin "11") (pinfunction "11_11") (pintype "passive"))
    )
    (net (code "272") (name "unconnected-(FLASH_SERV-Pad5)") (class "Default")
      (node (ref "FLASH_SERV") (pin "5") (pinfunction "5_5") (pintype "passive"))
    )
    (net (code "273") (name "unconnected-(FLASH_SERV-Pad7)") (class "Default")
      (node (ref "FLASH_SERV") (pin "7") (pinfunction "7_7") (pintype "passive"))
    )
    (net (code "274") (name "unconnected-(FLASH_SERV-Pad9)") (class "Default")
      (node (ref "FLASH_SERV") (pin "9") (pinfunction "9_9") (pintype "passive"))
    )
    (net (code "275") (name "unconnected-(FLASH_SERV-Pad11)") (class "Default")
      (node (ref "FLASH_SERV") (pin "11") (pinfunction "11_11") (pintype "passive"))
    )
    (net (code "276") (name "unconnected-(IC1-N.C.-Pad1)") (class "Default")
      (node (ref "IC1") (pin "1") (pinfunction "N.C._1") (pintype "no_connect"))
    )
    (net (code "277") (name "unconnected-(IC2-N.C.-Pad1)") (class "Default")
      (node (ref "IC2") (pin "1") (pinfunction "N.C._1") (pintype "no_connect"))
    )
    (net (code "278") (name "unconnected-(JTAG_OPEN8-Pad11)") (class "Default")
      (node (ref "JTAG_OPEN8") (pin "11") (pinfunction "11_11") (pintype "passive"))
    )
    (net (code "279") (name "unconnected-(JTAG_OPEN8-Pad15)") (class "Default")
      (node (ref "JTAG_OPEN8") (pin "15") (pinfunction "15_15") (pintype "passive"))
    )
    (net (code "280") (name "unconnected-(JTAG_OPEN8-Pad17)") (class "Default")
      (node (ref "JTAG_OPEN8") (pin "17") (pinfunction "17_17") (pintype "passive"))
    )
    (net (code "281") (name "unconnected-(JTAG_OPEN8-Pad19)") (class "Default")
      (node (ref "JTAG_OPEN8") (pin "19") (pinfunction "19_19") (pintype "passive"))
    )
    (net (code "282") (name "unconnected-(JTAG_SERV-Pad11)") (class "Default")
      (node (ref "JTAG_SERV") (pin "11") (pinfunction "11_11") (pintype "passive"))
    )
    (net (code "283") (name "unconnected-(JTAG_SERV-Pad15)") (class "Default")
      (node (ref "JTAG_SERV") (pin "15") (pinfunction "15_15") (pintype "passive"))
    )
    (net (code "284") (name "unconnected-(JTAG_SERV-Pad17)") (class "Default")
      (node (ref "JTAG_SERV") (pin "17") (pinfunction "17_17") (pintype "passive"))
    )
    (net (code "285") (name "unconnected-(JTAG_SERV-Pad19)") (class "Default")
      (node (ref "JTAG_SERV") (pin "19") (pinfunction "19_19") (pintype "passive"))
    )
    (net (code "286") (name "unconnected-(LORA_OPEN8-ANT-PadP$16)") (class "Default")
      (node (ref "LORA_OPEN8") (pin "P$16") (pinfunction "ANT_P$16") (pintype "bidirectional"))
    )
    (net (code "287") (name "unconnected-(LORA_OPEN8-DIO0-PadP$11)") (class "Default")
      (node (ref "LORA_OPEN8") (pin "P$11") (pinfunction "DIO0_P$11") (pintype "bidirectional"))
    )
    (net (code "288") (name "unconnected-(LORA_OPEN8-DIO1-PadP$10)") (class "Default")
      (node (ref "LORA_OPEN8") (pin "P$10") (pinfunction "DIO1_P$10") (pintype "bidirectional"))
    )
    (net (code "289") (name "unconnected-(LORA_OPEN8-DIO2-PadP$9)") (class "Default")
      (node (ref "LORA_OPEN8") (pin "P$9") (pinfunction "DIO2_P$9") (pintype "bidirectional"))
    )
    (net (code "290") (name "unconnected-(LORA_OPEN8-DIO3-PadP$14)") (class "Default")
      (node (ref "LORA_OPEN8") (pin "P$14") (pinfunction "DIO3_P$14") (pintype "bidirectional"))
    )
    (net (code "291") (name "unconnected-(LORA_OPEN8-DIO4-PadP$13)") (class "Default")
      (node (ref "LORA_OPEN8") (pin "P$13") (pinfunction "DIO4_P$13") (pintype "bidirectional"))
    )
    (net (code "292") (name "unconnected-(LORA_OPEN8-DIO5-PadP$7)") (class "Default")
      (node (ref "LORA_OPEN8") (pin "P$7") (pinfunction "DIO5_P$7") (pintype "bidirectional"))
    )
    (net (code "293") (name "unconnected-(LORA_OPEN8-RESET-PadP$6)") (class "Default")
      (node (ref "LORA_OPEN8") (pin "P$6") (pinfunction "RESET_P$6") (pintype "bidirectional"))
    )
    (net (code "294") (name "unconnected-(LORA_SERV-ANT-PadP$16)") (class "Default")
      (node (ref "LORA_SERV") (pin "P$16") (pinfunction "ANT_P$16") (pintype "bidirectional"))
    )
    (net (code "295") (name "unconnected-(LORA_SERV-DIO0-PadP$11)") (class "Default")
      (node (ref "LORA_SERV") (pin "P$11") (pinfunction "DIO0_P$11") (pintype "bidirectional"))
    )
    (net (code "296") (name "unconnected-(LORA_SERV-DIO1-PadP$10)") (class "Default")
      (node (ref "LORA_SERV") (pin "P$10") (pinfunction "DIO1_P$10") (pintype "bidirectional"))
    )
    (net (code "297") (name "unconnected-(LORA_SERV-DIO2-PadP$9)") (class "Default")
      (node (ref "LORA_SERV") (pin "P$9") (pinfunction "DIO2_P$9") (pintype "bidirectional"))
    )
    (net (code "298") (name "unconnected-(LORA_SERV-DIO3-PadP$14)") (class "Default")
      (node (ref "LORA_SERV") (pin "P$14") (pinfunction "DIO3_P$14") (pintype "bidirectional"))
    )
    (net (code "299") (name "unconnected-(LORA_SERV-DIO4-PadP$13)") (class "Default")
      (node (ref "LORA_SERV") (pin "P$13") (pinfunction "DIO4_P$13") (pintype "bidirectional"))
    )
    (net (code "300") (name "unconnected-(LORA_SERV-DIO5-PadP$7)") (class "Default")
      (node (ref "LORA_SERV") (pin "P$7") (pinfunction "DIO5_P$7") (pintype "bidirectional"))
    )
    (net (code "301") (name "unconnected-(LORA_SERV-RESET-PadP$6)") (class "Default")
      (node (ref "LORA_SERV") (pin "P$6") (pinfunction "RESET_P$6") (pintype "bidirectional"))
    )
    (net (code "302") (name "unconnected-(SPI_OPEN8_1-Pad1)") (class "Default")
      (node (ref "SPI_OPEN8_1") (pin "1") (pinfunction "1_1") (pintype "passive"))
    )
    (net (code "303") (name "unconnected-(SPI_OPEN8_1-Pad2)") (class "Default")
      (node (ref "SPI_OPEN8_1") (pin "2") (pinfunction "2_2") (pintype "passive"))
    )
    (net (code "304") (name "unconnected-(SPI_OPEN8_1-Pad3)") (class "Default")
      (node (ref "SPI_OPEN8_1") (pin "3") (pinfunction "3_3") (pintype "passive"))
    )
    (net (code "305") (name "unconnected-(SPI_OPEN8_1-Pad4)") (class "Default")
      (node (ref "SPI_OPEN8_1") (pin "4") (pinfunction "4_4") (pintype "passive"))
    )
    (net (code "306") (name "unconnected-(SPI_OPEN8_1-Pad5)") (class "Default")
      (node (ref "SPI_OPEN8_1") (pin "5") (pinfunction "5_5") (pintype "passive"))
    )
    (net (code "307") (name "unconnected-(SPI_OPEN8_1-Pad6)") (class "Default")
      (node (ref "SPI_OPEN8_1") (pin "6") (pinfunction "6_6") (pintype "passive"))
    )
    (net (code "308") (name "unconnected-(SPI_OPEN8_1-Pad7)") (class "Default")
      (node (ref "SPI_OPEN8_1") (pin "7") (pinfunction "7_7") (pintype "passive"))
    )
    (net (code "309") (name "unconnected-(SPI_OPEN8_1-Pad8)") (class "Default")
      (node (ref "SPI_OPEN8_1") (pin "8") (pinfunction "8_8") (pintype "passive"))
    )
    (net (code "310") (name "unconnected-(SPI_OPEN8_1-Pad9)") (class "Default")
      (node (ref "SPI_OPEN8_1") (pin "9") (pinfunction "9_9") (pintype "passive"))
    )
    (net (code "311") (name "unconnected-(SPI_OPEN8_1-Pad10)") (class "Default")
      (node (ref "SPI_OPEN8_1") (pin "10") (pinfunction "10_10") (pintype "passive"))
    )
    (net (code "312") (name "unconnected-(SPI_OPEN8_2-Pad5)") (class "Default")
      (node (ref "SPI_OPEN8_2") (pin "5") (pinfunction "5_5") (pintype "passive"))
    )
    (net (code "313") (name "unconnected-(SPI_OPEN8_2-Pad6)") (class "Default")
      (node (ref "SPI_OPEN8_2") (pin "6") (pinfunction "6_6") (pintype "passive"))
    )
    (net (code "314") (name "unconnected-(SPI_OPEN8_2-Pad7)") (class "Default")
      (node (ref "SPI_OPEN8_2") (pin "7") (pinfunction "7_7") (pintype "passive"))
    )
    (net (code "315") (name "unconnected-(SPI_OPEN8_2-Pad8)") (class "Default")
      (node (ref "SPI_OPEN8_2") (pin "8") (pinfunction "8_8") (pintype "passive"))
    )
    (net (code "316") (name "unconnected-(SPI_OPEN8_2-Pad9)") (class "Default")
      (node (ref "SPI_OPEN8_2") (pin "9") (pinfunction "9_9") (pintype "passive"))
    )
    (net (code "317") (name "unconnected-(SPI_SERV_1-Pad1)") (class "Default")
      (node (ref "SPI_SERV_1") (pin "1") (pinfunction "1_1") (pintype "passive"))
    )
    (net (code "318") (name "unconnected-(SPI_SERV_1-Pad2)") (class "Default")
      (node (ref "SPI_SERV_1") (pin "2") (pinfunction "2_2") (pintype "passive"))
    )
    (net (code "319") (name "unconnected-(SPI_SERV_1-Pad3)") (class "Default")
      (node (ref "SPI_SERV_1") (pin "3") (pinfunction "3_3") (pintype "passive"))
    )
    (net (code "320") (name "unconnected-(SPI_SERV_1-Pad4)") (class "Default")
      (node (ref "SPI_SERV_1") (pin "4") (pinfunction "4_4") (pintype "passive"))
    )
    (net (code "321") (name "unconnected-(SPI_SERV_1-Pad5)") (class "Default")
      (node (ref "SPI_SERV_1") (pin "5") (pinfunction "5_5") (pintype "passive"))
    )
    (net (code "322") (name "unconnected-(SPI_SERV_1-Pad6)") (class "Default")
      (node (ref "SPI_SERV_1") (pin "6") (pinfunction "6_6") (pintype "passive"))
    )
    (net (code "323") (name "unconnected-(SPI_SERV_1-Pad7)") (class "Default")
      (node (ref "SPI_SERV_1") (pin "7") (pinfunction "7_7") (pintype "passive"))
    )
    (net (code "324") (name "unconnected-(SPI_SERV_1-Pad8)") (class "Default")
      (node (ref "SPI_SERV_1") (pin "8") (pinfunction "8_8") (pintype "passive"))
    )
    (net (code "325") (name "unconnected-(SPI_SERV_1-Pad9)") (class "Default")
      (node (ref "SPI_SERV_1") (pin "9") (pinfunction "9_9") (pintype "passive"))
    )
    (net (code "326") (name "unconnected-(SPI_SERV_1-Pad10)") (class "Default")
      (node (ref "SPI_SERV_1") (pin "10") (pinfunction "10_10") (pintype "passive"))
    )
    (net (code "327") (name "unconnected-(SPI_SERV_2-Pad5)") (class "Default")
      (node (ref "SPI_SERV_2") (pin "5") (pinfunction "5_5") (pintype "passive"))
    )
    (net (code "328") (name "unconnected-(SPI_SERV_2-Pad6)") (class "Default")
      (node (ref "SPI_SERV_2") (pin "6") (pinfunction "6_6") (pintype "passive"))
    )
    (net (code "329") (name "unconnected-(SPI_SERV_2-Pad7)") (class "Default")
      (node (ref "SPI_SERV_2") (pin "7") (pinfunction "7_7") (pintype "passive"))
    )
    (net (code "330") (name "unconnected-(SPI_SERV_2-Pad8)") (class "Default")
      (node (ref "SPI_SERV_2") (pin "8") (pinfunction "8_8") (pintype "passive"))
    )
    (net (code "331") (name "unconnected-(SPI_SERV_2-Pad9)") (class "Default")
      (node (ref "SPI_SERV_2") (pin "9") (pinfunction "9_9") (pintype "passive"))
    )
    (net (code "332") (name "unconnected-(U$1-Pad2)") (class "Default")
      (node (ref "U$1") (pin "2") (pinfunction "2_2") (pintype "bidirectional"))
    )
    (net (code "333") (name "unconnected-(U$1-Pad41)") (class "Default")
      (node (ref "U$1") (pin "41") (pinfunction "41_41") (pintype "bidirectional"))
    )
    (net (code "334") (name "unconnected-(U$2-Pad2)") (class "Default")
      (node (ref "U$2") (pin "2") (pinfunction "2_2") (pintype "bidirectional"))
    )
    (net (code "335") (name "unconnected-(U$2-Pad41)") (class "Default")
      (node (ref "U$2") (pin "41") (pinfunction "41_41") (pintype "bidirectional"))
    )
    (net (code "336") (name "unconnected-(U$3-Pad2)") (class "Default")
      (node (ref "U$3") (pin "2") (pinfunction "2_2") (pintype "bidirectional"))
    )
    (net (code "337") (name "unconnected-(U$3-Pad41)") (class "Default")
      (node (ref "U$3") (pin "41") (pinfunction "41_41") (pintype "bidirectional"))
    )
    (net (code "338") (name "unconnected-(U$4-Pad2)") (class "Default")
      (node (ref "U$4") (pin "2") (pinfunction "2_2") (pintype "bidirectional"))
    )
    (net (code "339") (name "unconnected-(U$4-Pad41)") (class "Default")
      (node (ref "U$4") (pin "41") (pinfunction "41_41") (pintype "bidirectional"))
    )
    (net (code "340") (name "unconnected-(USB-UART_OPEN8_2-Pad1)") (class "Default")
      (node (ref "USB-UART_OPEN8_2") (pin "1") (pinfunction "1_1") (pintype "passive"))
    )
    (net (code "341") (name "unconnected-(USB-UART_OPEN8_2-Pad3)") (class "Default")
      (node (ref "USB-UART_OPEN8_2") (pin "3") (pinfunction "3_3") (pintype "passive"))
    )
    (net (code "342") (name "unconnected-(USB-UART_OPEN8_2-Pad4)") (class "Default")
      (node (ref "USB-UART_OPEN8_2") (pin "4") (pinfunction "4_4") (pintype "passive"))
    )
    (net (code "343") (name "unconnected-(USB-UART_SERV_2-Pad1)") (class "Default")
      (node (ref "USB-UART_SERV_2") (pin "1") (pinfunction "1_1") (pintype "passive"))
    )
    (net (code "344") (name "unconnected-(USB-UART_SERV_2-Pad3)") (class "Default")
      (node (ref "USB-UART_SERV_2") (pin "3") (pinfunction "3_3") (pintype "passive"))
    )
    (net (code "345") (name "unconnected-(USB-UART_SERV_2-Pad4)") (class "Default")
      (node (ref "USB-UART_SERV_2") (pin "4") (pinfunction "4_4") (pintype "passive"))
    )
  )
)
